# 10m02.net
KiCad netlist of a schematic drawn in EAGLE
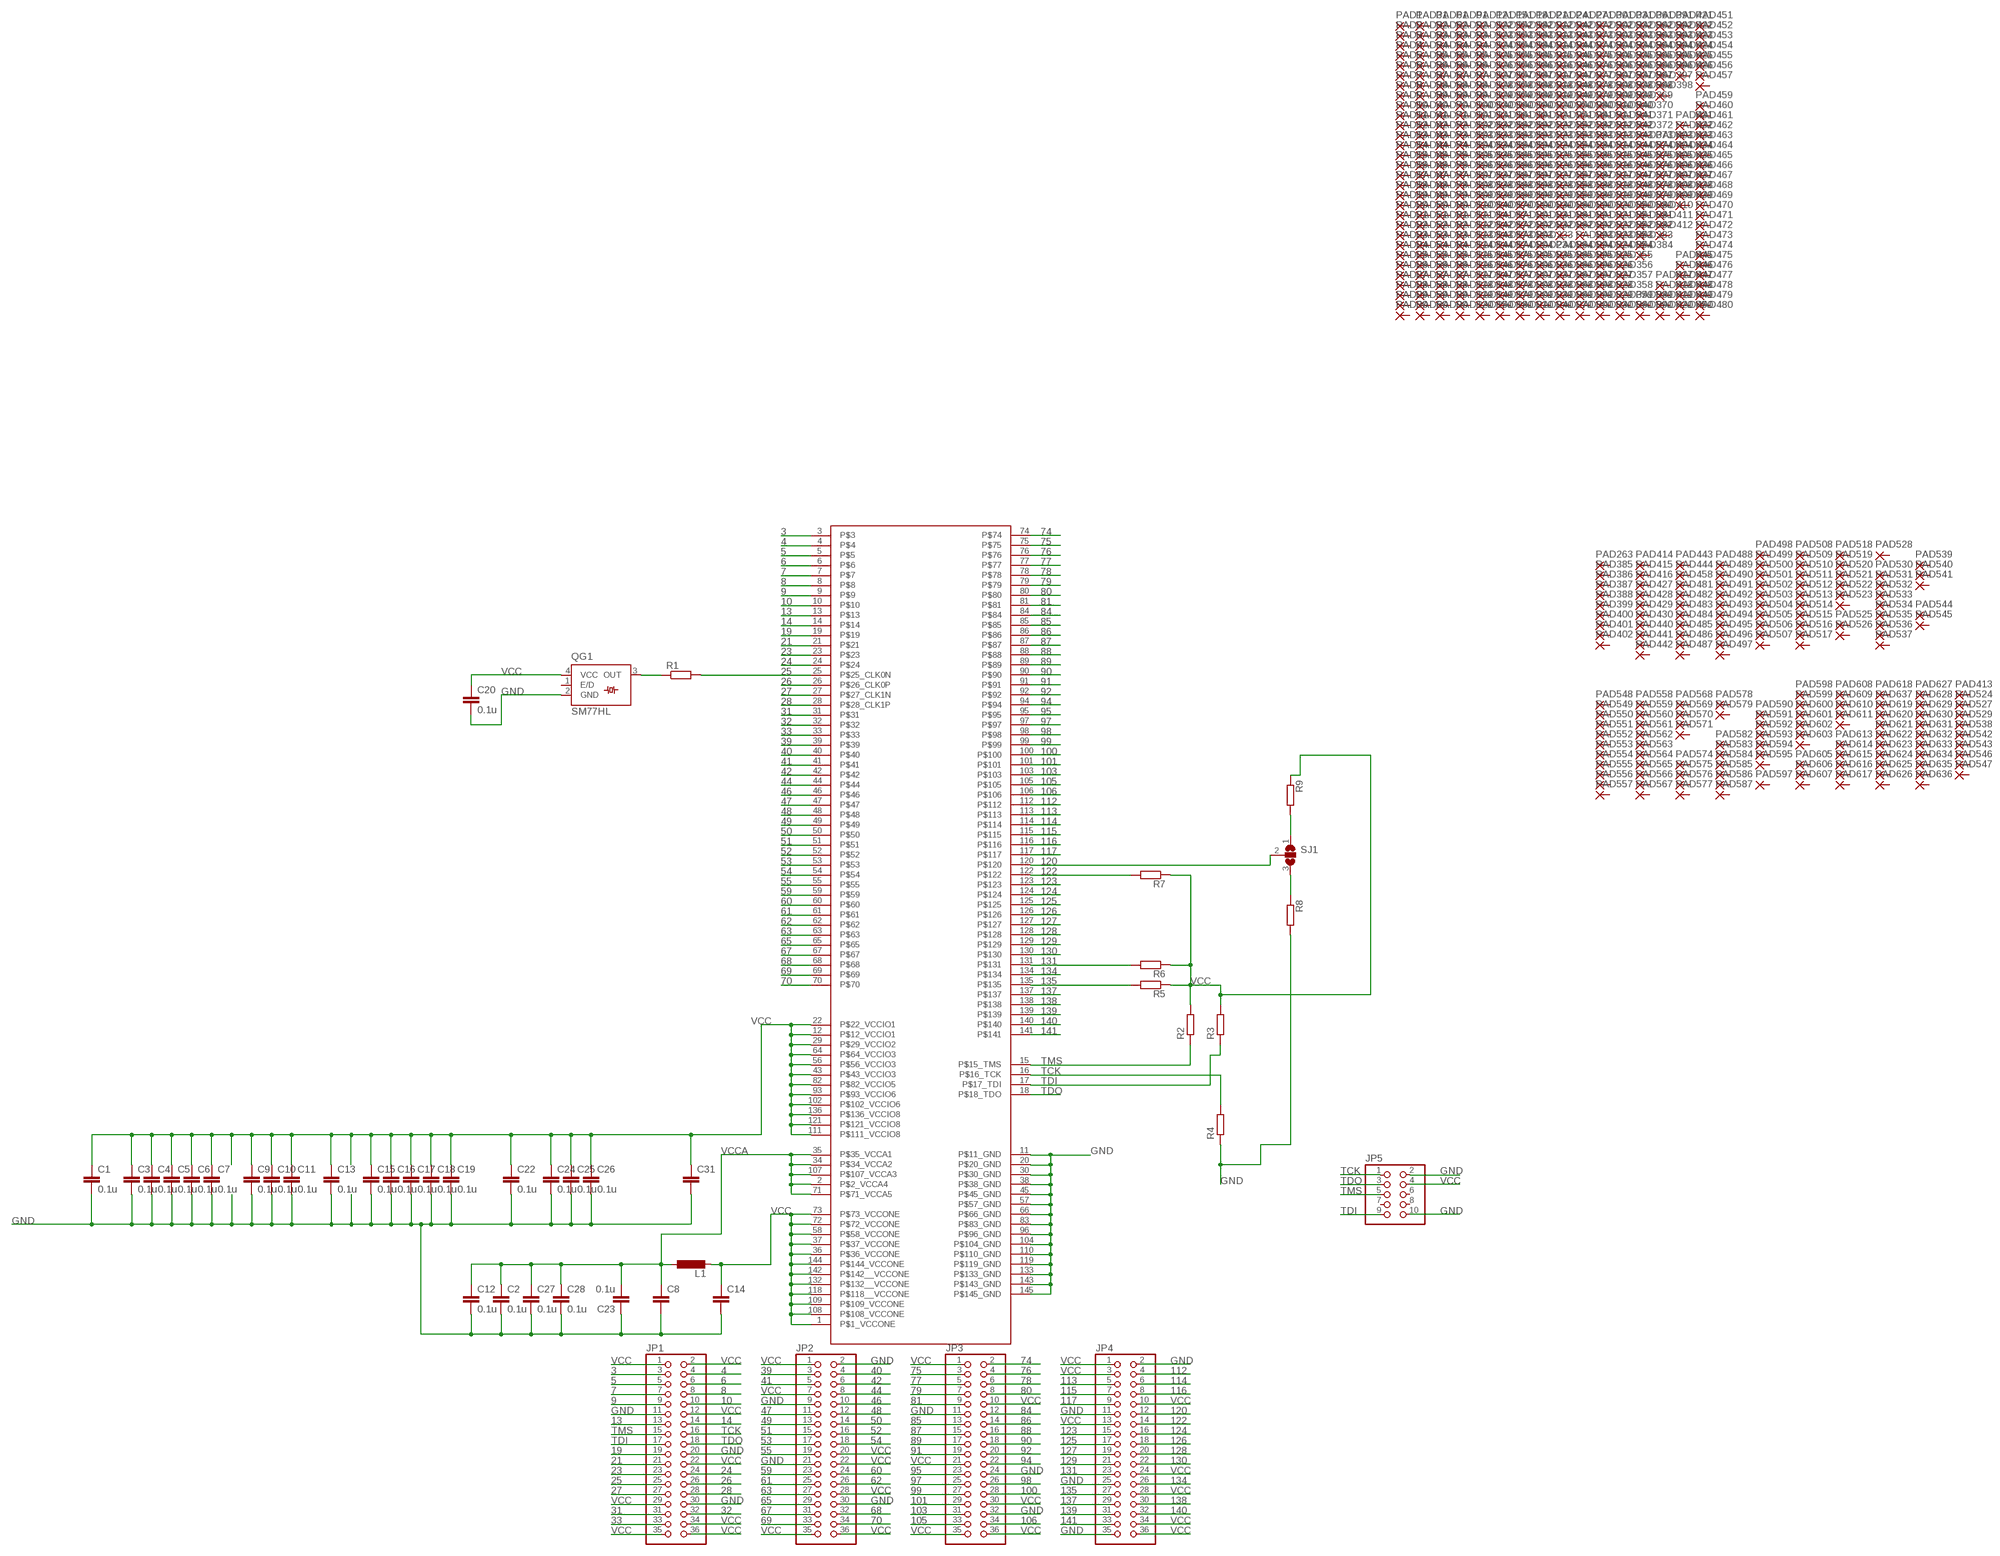
[diagram p0: schematic, sheet 1]

(export (version "E")
  (design (tool "Eeschema 10.0.6"))
  (components
    (comp (ref "C1")
      (value "0.1u")
      (footprint "eagle-import:C0603K")
      (libsource (lib "eagle-import") (part "C-EUC0603K"))
    )
    (comp (ref "C2")
      (value "0.1u")
      (footprint "eagle-import:C0603K")
      (libsource (lib "eagle-import") (part "C-EUC0603K"))
    )
    (comp (ref "C3")
      (value "0.1u")
      (footprint "eagle-import:C0603K")
      (libsource (lib "eagle-import") (part "C-EUC0603K"))
    )
    (comp (ref "C4")
      (value "0.1u")
      (footprint "eagle-import:C0603K")
      (libsource (lib "eagle-import") (part "C-EUC0603K"))
    )
    (comp (ref "C5")
      (value "0.1u")
      (footprint "eagle-import:C0603K")
      (libsource (lib "eagle-import") (part "C-EUC0603K"))
    )
    (comp (ref "C6")
      (value "0.1u")
      (footprint "eagle-import:C0603K")
      (libsource (lib "eagle-import") (part "C-EUC0603K"))
    )
    (comp (ref "C7")
      (value "0.1u")
      (footprint "eagle-import:C0603K")
      (libsource (lib "eagle-import") (part "C-EUC0603K"))
    )
    (comp (ref "C8")
      (value "C-EUC3216")
      (footprint "eagle-import:C3216")
      (libsource (lib "eagle-import") (part "C-EUC3216"))
    )
    (comp (ref "C9")
      (value "0.1u")
      (footprint "eagle-import:C0603K")
      (libsource (lib "eagle-import") (part "C-EUC0603K"))
    )
    (comp (ref "C10")
      (value "0.1u")
      (footprint "eagle-import:C0603K")
      (libsource (lib "eagle-import") (part "C-EUC0603K"))
    )
    (comp (ref "C11")
      (value "0.1u")
      (footprint "eagle-import:C0603K")
      (libsource (lib "eagle-import") (part "C-EUC0603K"))
    )
    (comp (ref "C12")
      (value "0.1u")
      (footprint "eagle-import:C0603K")
      (libsource (lib "eagle-import") (part "C-EUC0603K"))
    )
    (comp (ref "C13")
      (value "0.1u")
      (footprint "eagle-import:C0603K")
      (libsource (lib "eagle-import") (part "C-EUC0603K"))
    )
    (comp (ref "C14")
      (value "C-EUC3216")
      (footprint "eagle-import:C3216")
      (libsource (lib "eagle-import") (part "C-EUC3216"))
    )
    (comp (ref "C15")
      (value "0.1u")
      (footprint "eagle-import:C0603K")
      (libsource (lib "eagle-import") (part "C-EUC0603K"))
    )
    (comp (ref "C16")
      (value "0.1u")
      (footprint "eagle-import:C0603K")
      (libsource (lib "eagle-import") (part "C-EUC0603K"))
    )
    (comp (ref "C17")
      (value "0.1u")
      (footprint "eagle-import:C0603K")
      (libsource (lib "eagle-import") (part "C-EUC0603K"))
    )
    (comp (ref "C18")
      (value "0.1u")
      (footprint "eagle-import:C0603K")
      (libsource (lib "eagle-import") (part "C-EUC0603K"))
    )
    (comp (ref "C19")
      (value "0.1u")
      (footprint "eagle-import:C0603K")
      (libsource (lib "eagle-import") (part "C-EUC0603K"))
    )
    (comp (ref "C20")
      (value "0.1u")
      (footprint "eagle-import:C0603K")
      (libsource (lib "eagle-import") (part "C-EUC0603K"))
    )
    (comp (ref "C22")
      (value "0.1u")
      (footprint "eagle-import:C0603K")
      (libsource (lib "eagle-import") (part "C-EUC0603K"))
    )
    (comp (ref "C23")
      (value "0.1u")
      (footprint "eagle-import:C0603K")
      (libsource (lib "eagle-import") (part "C-EUC0603K"))
    )
    (comp (ref "C24")
      (value "0.1u")
      (footprint "eagle-import:C0603K")
      (libsource (lib "eagle-import") (part "C-EUC0603K"))
    )
    (comp (ref "C25")
      (value "0.1u")
      (footprint "eagle-import:C0603K")
      (libsource (lib "eagle-import") (part "C-EUC0603K"))
    )
    (comp (ref "C26")
      (value "0.1u")
      (footprint "eagle-import:C0603K")
      (libsource (lib "eagle-import") (part "C-EUC0603K"))
    )
    (comp (ref "C27")
      (value "0.1u")
      (footprint "eagle-import:C0603K")
      (libsource (lib "eagle-import") (part "C-EUC0603K"))
    )
    (comp (ref "C28")
      (value "0.1u")
      (footprint "eagle-import:C0603K")
      (libsource (lib "eagle-import") (part "C-EUC0603K"))
    )
    (comp (ref "C31")
      (value "C-EUC3225")
      (footprint "eagle-import:C3225")
      (libsource (lib "eagle-import") (part "C-EUC3225"))
    )
    (comp (ref "IC1")
      (value "10M02SC144")
      (footprint "eagle-import:TQFP144G")
      (libsource (lib "eagle-import") (part "10M02SC144"))
    )
    (comp (ref "JP1")
      (value "PINHD-2X18")
      (footprint "eagle-import:2X18")
      (libsource (lib "eagle-import") (part "PINHD-2X18"))
    )
    (comp (ref "JP2")
      (value "PINHD-2X18")
      (footprint "eagle-import:2X18")
      (libsource (lib "eagle-import") (part "PINHD-2X18"))
    )
    (comp (ref "JP3")
      (value "PINHD-2X18")
      (footprint "eagle-import:2X18")
      (libsource (lib "eagle-import") (part "PINHD-2X18"))
    )
    (comp (ref "JP4")
      (value "PINHD-2X18")
      (footprint "eagle-import:2X18")
      (libsource (lib "eagle-import") (part "PINHD-2X18"))
    )
    (comp (ref "JP5")
      (value "PINHD-2X5")
      (footprint "eagle-import:2X05")
      (libsource (lib "eagle-import") (part "PINHD-2X5"))
    )
    (comp (ref "L1")
      (value "L-EUL3216C")
      (footprint "eagle-import:L3216C")
      (libsource (lib "eagle-import") (part "L-EUL3216C"))
    )
    (comp (ref "PAD1")
      (value "1,6/0,9")
      (footprint "eagle-import:1,6_0,9")
      (libsource (lib "eagle-import") (part "1,6/0,9"))
    )
    (comp (ref "PAD2")
      (value "1,6/0,9")
      (footprint "eagle-import:1,6_0,9")
      (libsource (lib "eagle-import") (part "1,6/0,9"))
    )
    (comp (ref "PAD3")
      (value "1,6/0,9")
      (footprint "eagle-import:1,6_0,9")
      (libsource (lib "eagle-import") (part "1,6/0,9"))
    )
    (comp (ref "PAD4")
      (value "1,6/0,9")
      (footprint "eagle-import:1,6_0,9")
      (libsource (lib "eagle-import") (part "1,6/0,9"))
    )
    (comp (ref "PAD5")
      (value "1,6/0,9")
      (footprint "eagle-import:1,6_0,9")
      (libsource (lib "eagle-import") (part "1,6/0,9"))
    )
    (comp (ref "PAD6")
      (value "1,6/0,9")
      (footprint "eagle-import:1,6_0,9")
      (libsource (lib "eagle-import") (part "1,6/0,9"))
    )
    (comp (ref "PAD7")
      (value "1,6/0,9")
      (footprint "eagle-import:1,6_0,9")
      (libsource (lib "eagle-import") (part "1,6/0,9"))
    )
    (comp (ref "PAD8")
      (value "1,6/0,9")
      (footprint "eagle-import:1,6_0,9")
      (libsource (lib "eagle-import") (part "1,6/0,9"))
    )
    (comp (ref "PAD9")
      (value "1,6/0,9")
      (footprint "eagle-import:1,6_0,9")
      (libsource (lib "eagle-import") (part "1,6/0,9"))
    )
    (comp (ref "PAD10")
      (value "1,6/0,9")
      (footprint "eagle-import:1,6_0,9")
      (libsource (lib "eagle-import") (part "1,6/0,9"))
    )
    (comp (ref "PAD11")
      (value "1,6/0,9")
      (footprint "eagle-import:1,6_0,9")
      (libsource (lib "eagle-import") (part "1,6/0,9"))
    )
    (comp (ref "PAD12")
      (value "1,6/0,9")
      (footprint "eagle-import:1,6_0,9")
      (libsource (lib "eagle-import") (part "1,6/0,9"))
    )
    (comp (ref "PAD13")
      (value "1,6/0,9")
      (footprint "eagle-import:1,6_0,9")
      (libsource (lib "eagle-import") (part "1,6/0,9"))
    )
    (comp (ref "PAD14")
      (value "1,6/0,9")
      (footprint "eagle-import:1,6_0,9")
      (libsource (lib "eagle-import") (part "1,6/0,9"))
    )
    (comp (ref "PAD15")
      (value "1,6/0,9")
      (footprint "eagle-import:1,6_0,9")
      (libsource (lib "eagle-import") (part "1,6/0,9"))
    )
    (comp (ref "PAD16")
      (value "1,6/0,9")
      (footprint "eagle-import:1,6_0,9")
      (libsource (lib "eagle-import") (part "1,6/0,9"))
    )
    (comp (ref "PAD17")
      (value "1,6/0,9")
      (footprint "eagle-import:1,6_0,9")
      (libsource (lib "eagle-import") (part "1,6/0,9"))
    )
    (comp (ref "PAD18")
      (value "1,6/0,9")
      (footprint "eagle-import:1,6_0,9")
      (libsource (lib "eagle-import") (part "1,6/0,9"))
    )
    (comp (ref "PAD19")
      (value "1,6/0,9")
      (footprint "eagle-import:1,6_0,9")
      (libsource (lib "eagle-import") (part "1,6/0,9"))
    )
    (comp (ref "PAD20")
      (value "1,6/0,9")
      (footprint "eagle-import:1,6_0,9")
      (libsource (lib "eagle-import") (part "1,6/0,9"))
    )
    (comp (ref "PAD21")
      (value "1,6/0,9")
      (footprint "eagle-import:1,6_0,9")
      (libsource (lib "eagle-import") (part "1,6/0,9"))
    )
    (comp (ref "PAD22")
      (value "1,6/0,9")
      (footprint "eagle-import:1,6_0,9")
      (libsource (lib "eagle-import") (part "1,6/0,9"))
    )
    (comp (ref "PAD23")
      (value "1,6/0,9")
      (footprint "eagle-import:1,6_0,9")
      (libsource (lib "eagle-import") (part "1,6/0,9"))
    )
    (comp (ref "PAD24")
      (value "1,6/0,9")
      (footprint "eagle-import:1,6_0,9")
      (libsource (lib "eagle-import") (part "1,6/0,9"))
    )
    (comp (ref "PAD25")
      (value "1,6/0,9")
      (footprint "eagle-import:1,6_0,9")
      (libsource (lib "eagle-import") (part "1,6/0,9"))
    )
    (comp (ref "PAD26")
      (value "1,6/0,9")
      (footprint "eagle-import:1,6_0,9")
      (libsource (lib "eagle-import") (part "1,6/0,9"))
    )
    (comp (ref "PAD27")
      (value "1,6/0,9")
      (footprint "eagle-import:1,6_0,9")
      (libsource (lib "eagle-import") (part "1,6/0,9"))
    )
    (comp (ref "PAD28")
      (value "1,6/0,9")
      (footprint "eagle-import:1,6_0,9")
      (libsource (lib "eagle-import") (part "1,6/0,9"))
    )
    (comp (ref "PAD29")
      (value "1,6/0,9")
      (footprint "eagle-import:1,6_0,9")
      (libsource (lib "eagle-import") (part "1,6/0,9"))
    )
    (comp (ref "PAD30")
      (value "1,6/0,9")
      (footprint "eagle-import:1,6_0,9")
      (libsource (lib "eagle-import") (part "1,6/0,9"))
    )
    (comp (ref "PAD31")
      (value "1,6/0,9")
      (footprint "eagle-import:1,6_0,9")
      (libsource (lib "eagle-import") (part "1,6/0,9"))
    )
    (comp (ref "PAD32")
      (value "1,6/0,9")
      (footprint "eagle-import:1,6_0,9")
      (libsource (lib "eagle-import") (part "1,6/0,9"))
    )
    (comp (ref "PAD33")
      (value "1,6/0,9")
      (footprint "eagle-import:1,6_0,9")
      (libsource (lib "eagle-import") (part "1,6/0,9"))
    )
    (comp (ref "PAD34")
      (value "1,6/0,9")
      (footprint "eagle-import:1,6_0,9")
      (libsource (lib "eagle-import") (part "1,6/0,9"))
    )
    (comp (ref "PAD35")
      (value "1,6/0,9")
      (footprint "eagle-import:1,6_0,9")
      (libsource (lib "eagle-import") (part "1,6/0,9"))
    )
    (comp (ref "PAD36")
      (value "1,6/0,9")
      (footprint "eagle-import:1,6_0,9")
      (libsource (lib "eagle-import") (part "1,6/0,9"))
    )
    (comp (ref "PAD37")
      (value "1,6/0,9")
      (footprint "eagle-import:1,6_0,9")
      (libsource (lib "eagle-import") (part "1,6/0,9"))
    )
    (comp (ref "PAD38")
      (value "1,6/0,9")
      (footprint "eagle-import:1,6_0,9")
      (libsource (lib "eagle-import") (part "1,6/0,9"))
    )
    (comp (ref "PAD39")
      (value "1,6/0,9")
      (footprint "eagle-import:1,6_0,9")
      (libsource (lib "eagle-import") (part "1,6/0,9"))
    )
    (comp (ref "PAD40")
      (value "1,6/0,9")
      (footprint "eagle-import:1,6_0,9")
      (libsource (lib "eagle-import") (part "1,6/0,9"))
    )
    (comp (ref "PAD41")
      (value "1,6/0,9")
      (footprint "eagle-import:1,6_0,9")
      (libsource (lib "eagle-import") (part "1,6/0,9"))
    )
    (comp (ref "PAD42")
      (value "1,6/0,9")
      (footprint "eagle-import:1,6_0,9")
      (libsource (lib "eagle-import") (part "1,6/0,9"))
    )
    (comp (ref "PAD43")
      (value "1,6/0,9")
      (footprint "eagle-import:1,6_0,9")
      (libsource (lib "eagle-import") (part "1,6/0,9"))
    )
    (comp (ref "PAD44")
      (value "1,6/0,9")
      (footprint "eagle-import:1,6_0,9")
      (libsource (lib "eagle-import") (part "1,6/0,9"))
    )
    (comp (ref "PAD45")
      (value "1,6/0,9")
      (footprint "eagle-import:1,6_0,9")
      (libsource (lib "eagle-import") (part "1,6/0,9"))
    )
    (comp (ref "PAD46")
      (value "1,6/0,9")
      (footprint "eagle-import:1,6_0,9")
      (libsource (lib "eagle-import") (part "1,6/0,9"))
    )
    (comp (ref "PAD47")
      (value "1,6/0,9")
      (footprint "eagle-import:1,6_0,9")
      (libsource (lib "eagle-import") (part "1,6/0,9"))
    )
    (comp (ref "PAD48")
      (value "1,6/0,9")
      (footprint "eagle-import:1,6_0,9")
      (libsource (lib "eagle-import") (part "1,6/0,9"))
    )
    (comp (ref "PAD49")
      (value "1,6/0,9")
      (footprint "eagle-import:1,6_0,9")
      (libsource (lib "eagle-import") (part "1,6/0,9"))
    )
    (comp (ref "PAD50")
      (value "1,6/0,9")
      (footprint "eagle-import:1,6_0,9")
      (libsource (lib "eagle-import") (part "1,6/0,9"))
    )
    (comp (ref "PAD51")
      (value "1,6/0,9")
      (footprint "eagle-import:1,6_0,9")
      (libsource (lib "eagle-import") (part "1,6/0,9"))
    )
    (comp (ref "PAD52")
      (value "1,6/0,9")
      (footprint "eagle-import:1,6_0,9")
      (libsource (lib "eagle-import") (part "1,6/0,9"))
    )
    (comp (ref "PAD53")
      (value "1,6/0,9")
      (footprint "eagle-import:1,6_0,9")
      (libsource (lib "eagle-import") (part "1,6/0,9"))
    )
    (comp (ref "PAD54")
      (value "1,6/0,9")
      (footprint "eagle-import:1,6_0,9")
      (libsource (lib "eagle-import") (part "1,6/0,9"))
    )
    (comp (ref "PAD55")
      (value "1,6/0,9")
      (footprint "eagle-import:1,6_0,9")
      (libsource (lib "eagle-import") (part "1,6/0,9"))
    )
    (comp (ref "PAD56")
      (value "1,6/0,9")
      (footprint "eagle-import:1,6_0,9")
      (libsource (lib "eagle-import") (part "1,6/0,9"))
    )
    (comp (ref "PAD57")
      (value "1,6/0,9")
      (footprint "eagle-import:1,6_0,9")
      (libsource (lib "eagle-import") (part "1,6/0,9"))
    )
    (comp (ref "PAD58")
      (value "1,6/0,9")
      (footprint "eagle-import:1,6_0,9")
      (libsource (lib "eagle-import") (part "1,6/0,9"))
    )
    (comp (ref "PAD59")
      (value "1,6/0,9")
      (footprint "eagle-import:1,6_0,9")
      (libsource (lib "eagle-import") (part "1,6/0,9"))
    )
    (comp (ref "PAD60")
      (value "1,6/0,9")
      (footprint "eagle-import:1,6_0,9")
      (libsource (lib "eagle-import") (part "1,6/0,9"))
    )
    (comp (ref "PAD61")
      (value "1,6/0,9")
      (footprint "eagle-import:1,6_0,9")
      (libsource (lib "eagle-import") (part "1,6/0,9"))
    )
    (comp (ref "PAD62")
      (value "1,6/0,9")
      (footprint "eagle-import:1,6_0,9")
      (libsource (lib "eagle-import") (part "1,6/0,9"))
    )
    (comp (ref "PAD63")
      (value "1,6/0,9")
      (footprint "eagle-import:1,6_0,9")
      (libsource (lib "eagle-import") (part "1,6/0,9"))
    )
    (comp (ref "PAD64")
      (value "1,6/0,9")
      (footprint "eagle-import:1,6_0,9")
      (libsource (lib "eagle-import") (part "1,6/0,9"))
    )
    (comp (ref "PAD65")
      (value "1,6/0,9")
      (footprint "eagle-import:1,6_0,9")
      (libsource (lib "eagle-import") (part "1,6/0,9"))
    )
    (comp (ref "PAD66")
      (value "1,6/0,9")
      (footprint "eagle-import:1,6_0,9")
      (libsource (lib "eagle-import") (part "1,6/0,9"))
    )
    (comp (ref "PAD67")
      (value "1,6/0,9")
      (footprint "eagle-import:1,6_0,9")
      (libsource (lib "eagle-import") (part "1,6/0,9"))
    )
    (comp (ref "PAD68")
      (value "1,6/0,9")
      (footprint "eagle-import:1,6_0,9")
      (libsource (lib "eagle-import") (part "1,6/0,9"))
    )
    (comp (ref "PAD69")
      (value "1,6/0,9")
      (footprint "eagle-import:1,6_0,9")
      (libsource (lib "eagle-import") (part "1,6/0,9"))
    )
    (comp (ref "PAD70")
      (value "1,6/0,9")
      (footprint "eagle-import:1,6_0,9")
      (libsource (lib "eagle-import") (part "1,6/0,9"))
    )
    (comp (ref "PAD71")
      (value "1,6/0,9")
      (footprint "eagle-import:1,6_0,9")
      (libsource (lib "eagle-import") (part "1,6/0,9"))
    )
    (comp (ref "PAD72")
      (value "1,6/0,9")
      (footprint "eagle-import:1,6_0,9")
      (libsource (lib "eagle-import") (part "1,6/0,9"))
    )
    (comp (ref "PAD73")
      (value "1,6/0,9")
      (footprint "eagle-import:1,6_0,9")
      (libsource (lib "eagle-import") (part "1,6/0,9"))
    )
    (comp (ref "PAD74")
      (value "1,6/0,9")
      (footprint "eagle-import:1,6_0,9")
      (libsource (lib "eagle-import") (part "1,6/0,9"))
    )
    (comp (ref "PAD75")
      (value "1,6/0,9")
      (footprint "eagle-import:1,6_0,9")
      (libsource (lib "eagle-import") (part "1,6/0,9"))
    )
    (comp (ref "PAD76")
      (value "1,6/0,9")
      (footprint "eagle-import:1,6_0,9")
      (libsource (lib "eagle-import") (part "1,6/0,9"))
    )
    (comp (ref "PAD77")
      (value "1,6/0,9")
      (footprint "eagle-import:1,6_0,9")
      (libsource (lib "eagle-import") (part "1,6/0,9"))
    )
    (comp (ref "PAD78")
      (value "1,6/0,9")
      (footprint "eagle-import:1,6_0,9")
      (libsource (lib "eagle-import") (part "1,6/0,9"))
    )
    (comp (ref "PAD79")
      (value "1,6/0,9")
      (footprint "eagle-import:1,6_0,9")
      (libsource (lib "eagle-import") (part "1,6/0,9"))
    )
    (comp (ref "PAD80")
      (value "1,6/0,9")
      (footprint "eagle-import:1,6_0,9")
      (libsource (lib "eagle-import") (part "1,6/0,9"))
    )
    (comp (ref "PAD81")
      (value "1,6/0,9")
      (footprint "eagle-import:1,6_0,9")
      (libsource (lib "eagle-import") (part "1,6/0,9"))
    )
    (comp (ref "PAD82")
      (value "1,6/0,9")
      (footprint "eagle-import:1,6_0,9")
      (libsource (lib "eagle-import") (part "1,6/0,9"))
    )
    (comp (ref "PAD83")
      (value "1,6/0,9")
      (footprint "eagle-import:1,6_0,9")
      (libsource (lib "eagle-import") (part "1,6/0,9"))
    )
    (comp (ref "PAD84")
      (value "1,6/0,9")
      (footprint "eagle-import:1,6_0,9")
      (libsource (lib "eagle-import") (part "1,6/0,9"))
    )
    (comp (ref "PAD85")
      (value "1,6/0,9")
      (footprint "eagle-import:1,6_0,9")
      (libsource (lib "eagle-import") (part "1,6/0,9"))
    )
    (comp (ref "PAD86")
      (value "1,6/0,9")
      (footprint "eagle-import:1,6_0,9")
      (libsource (lib "eagle-import") (part "1,6/0,9"))
    )
    (comp (ref "PAD87")
      (value "1,6/0,9")
      (footprint "eagle-import:1,6_0,9")
      (libsource (lib "eagle-import") (part "1,6/0,9"))
    )
    (comp (ref "PAD88")
      (value "1,6/0,9")
      (footprint "eagle-import:1,6_0,9")
      (libsource (lib "eagle-import") (part "1,6/0,9"))
    )
    (comp (ref "PAD89")
      (value "1,6/0,9")
      (footprint "eagle-import:1,6_0,9")
      (libsource (lib "eagle-import") (part "1,6/0,9"))
    )
    (comp (ref "PAD90")
      (value "1,6/0,9")
      (footprint "eagle-import:1,6_0,9")
      (libsource (lib "eagle-import") (part "1,6/0,9"))
    )
    (comp (ref "PAD91")
      (value "1,6/0,9")
      (footprint "eagle-import:1,6_0,9")
      (libsource (lib "eagle-import") (part "1,6/0,9"))
    )
    (comp (ref "PAD92")
      (value "1,6/0,9")
      (footprint "eagle-import:1,6_0,9")
      (libsource (lib "eagle-import") (part "1,6/0,9"))
    )
    (comp (ref "PAD93")
      (value "1,6/0,9")
      (footprint "eagle-import:1,6_0,9")
      (libsource (lib "eagle-import") (part "1,6/0,9"))
    )
    (comp (ref "PAD94")
      (value "1,6/0,9")
      (footprint "eagle-import:1,6_0,9")
      (libsource (lib "eagle-import") (part "1,6/0,9"))
    )
    (comp (ref "PAD95")
      (value "1,6/0,9")
      (footprint "eagle-import:1,6_0,9")
      (libsource (lib "eagle-import") (part "1,6/0,9"))
    )
    (comp (ref "PAD96")
      (value "1,6/0,9")
      (footprint "eagle-import:1,6_0,9")
      (libsource (lib "eagle-import") (part "1,6/0,9"))
    )
    (comp (ref "PAD97")
      (value "1,6/0,9")
      (footprint "eagle-import:1,6_0,9")
      (libsource (lib "eagle-import") (part "1,6/0,9"))
    )
    (comp (ref "PAD98")
      (value "1,6/0,9")
      (footprint "eagle-import:1,6_0,9")
      (libsource (lib "eagle-import") (part "1,6/0,9"))
    )
    (comp (ref "PAD99")
      (value "1,6/0,9")
      (footprint "eagle-import:1,6_0,9")
      (libsource (lib "eagle-import") (part "1,6/0,9"))
    )
    (comp (ref "PAD100")
      (value "1,6/0,9")
      (footprint "eagle-import:1,6_0,9")
      (libsource (lib "eagle-import") (part "1,6/0,9"))
    )
    (comp (ref "PAD101")
      (value "1,6/0,9")
      (footprint "eagle-import:1,6_0,9")
      (libsource (lib "eagle-import") (part "1,6/0,9"))
    )
    (comp (ref "PAD102")
      (value "1,6/0,9")
      (footprint "eagle-import:1,6_0,9")
      (libsource (lib "eagle-import") (part "1,6/0,9"))
    )
    (comp (ref "PAD103")
      (value "1,6/0,9")
      (footprint "eagle-import:1,6_0,9")
      (libsource (lib "eagle-import") (part "1,6/0,9"))
    )
    (comp (ref "PAD104")
      (value "1,6/0,9")
      (footprint "eagle-import:1,6_0,9")
      (libsource (lib "eagle-import") (part "1,6/0,9"))
    )
    (comp (ref "PAD105")
      (value "1,6/0,9")
      (footprint "eagle-import:1,6_0,9")
      (libsource (lib "eagle-import") (part "1,6/0,9"))
    )
    (comp (ref "PAD106")
      (value "1,6/0,9")
      (footprint "eagle-import:1,6_0,9")
      (libsource (lib "eagle-import") (part "1,6/0,9"))
    )
    (comp (ref "PAD107")
      (value "1,6/0,9")
      (footprint "eagle-import:1,6_0,9")
      (libsource (lib "eagle-import") (part "1,6/0,9"))
    )
    (comp (ref "PAD108")
      (value "1,6/0,9")
      (footprint "eagle-import:1,6_0,9")
      (libsource (lib "eagle-import") (part "1,6/0,9"))
    )
    (comp (ref "PAD109")
      (value "1,6/0,9")
      (footprint "eagle-import:1,6_0,9")
      (libsource (lib "eagle-import") (part "1,6/0,9"))
    )
    (comp (ref "PAD110")
      (value "1,6/0,9")
      (footprint "eagle-import:1,6_0,9")
      (libsource (lib "eagle-import") (part "1,6/0,9"))
    )
    (comp (ref "PAD111")
      (value "1,6/0,9")
      (footprint "eagle-import:1,6_0,9")
      (libsource (lib "eagle-import") (part "1,6/0,9"))
    )
    (comp (ref "PAD112")
      (value "1,6/0,9")
      (footprint "eagle-import:1,6_0,9")
      (libsource (lib "eagle-import") (part "1,6/0,9"))
    )
    (comp (ref "PAD113")
      (value "1,6/0,9")
      (footprint "eagle-import:1,6_0,9")
      (libsource (lib "eagle-import") (part "1,6/0,9"))
    )
    (comp (ref "PAD114")
      (value "1,6/0,9")
      (footprint "eagle-import:1,6_0,9")
      (libsource (lib "eagle-import") (part "1,6/0,9"))
    )
    (comp (ref "PAD115")
      (value "1,6/0,9")
      (footprint "eagle-import:1,6_0,9")
      (libsource (lib "eagle-import") (part "1,6/0,9"))
    )
    (comp (ref "PAD116")
      (value "1,6/0,9")
      (footprint "eagle-import:1,6_0,9")
      (libsource (lib "eagle-import") (part "1,6/0,9"))
    )
    (comp (ref "PAD117")
      (value "1,6/0,9")
      (footprint "eagle-import:1,6_0,9")
      (libsource (lib "eagle-import") (part "1,6/0,9"))
    )
    (comp (ref "PAD118")
      (value "1,6/0,9")
      (footprint "eagle-import:1,6_0,9")
      (libsource (lib "eagle-import") (part "1,6/0,9"))
    )
    (comp (ref "PAD119")
      (value "1,6/0,9")
      (footprint "eagle-import:1,6_0,9")
      (libsource (lib "eagle-import") (part "1,6/0,9"))
    )
    (comp (ref "PAD120")
      (value "1,6/0,9")
      (footprint "eagle-import:1,6_0,9")
      (libsource (lib "eagle-import") (part "1,6/0,9"))
    )
    (comp (ref "PAD121")
      (value "1,6/0,9")
      (footprint "eagle-import:1,6_0,9")
      (libsource (lib "eagle-import") (part "1,6/0,9"))
    )
    (comp (ref "PAD122")
      (value "1,6/0,9")
      (footprint "eagle-import:1,6_0,9")
      (libsource (lib "eagle-import") (part "1,6/0,9"))
    )
    (comp (ref "PAD123")
      (value "1,6/0,9")
      (footprint "eagle-import:1,6_0,9")
      (libsource (lib "eagle-import") (part "1,6/0,9"))
    )
    (comp (ref "PAD124")
      (value "1,6/0,9")
      (footprint "eagle-import:1,6_0,9")
      (libsource (lib "eagle-import") (part "1,6/0,9"))
    )
    (comp (ref "PAD125")
      (value "1,6/0,9")
      (footprint "eagle-import:1,6_0,9")
      (libsource (lib "eagle-import") (part "1,6/0,9"))
    )
    (comp (ref "PAD126")
      (value "1,6/0,9")
      (footprint "eagle-import:1,6_0,9")
      (libsource (lib "eagle-import") (part "1,6/0,9"))
    )
    (comp (ref "PAD127")
      (value "1,6/0,9")
      (footprint "eagle-import:1,6_0,9")
      (libsource (lib "eagle-import") (part "1,6/0,9"))
    )
    (comp (ref "PAD128")
      (value "1,6/0,9")
      (footprint "eagle-import:1,6_0,9")
      (libsource (lib "eagle-import") (part "1,6/0,9"))
    )
    (comp (ref "PAD129")
      (value "1,6/0,9")
      (footprint "eagle-import:1,6_0,9")
      (libsource (lib "eagle-import") (part "1,6/0,9"))
    )
    (comp (ref "PAD130")
      (value "1,6/0,9")
      (footprint "eagle-import:1,6_0,9")
      (libsource (lib "eagle-import") (part "1,6/0,9"))
    )
    (comp (ref "PAD131")
      (value "1,6/0,9")
      (footprint "eagle-import:1,6_0,9")
      (libsource (lib "eagle-import") (part "1,6/0,9"))
    )
    (comp (ref "PAD132")
      (value "1,6/0,9")
      (footprint "eagle-import:1,6_0,9")
      (libsource (lib "eagle-import") (part "1,6/0,9"))
    )
    (comp (ref "PAD133")
      (value "1,6/0,9")
      (footprint "eagle-import:1,6_0,9")
      (libsource (lib "eagle-import") (part "1,6/0,9"))
    )
    (comp (ref "PAD134")
      (value "1,6/0,9")
      (footprint "eagle-import:1,6_0,9")
      (libsource (lib "eagle-import") (part "1,6/0,9"))
    )
    (comp (ref "PAD135")
      (value "1,6/0,9")
      (footprint "eagle-import:1,6_0,9")
      (libsource (lib "eagle-import") (part "1,6/0,9"))
    )
    (comp (ref "PAD136")
      (value "1,6/0,9")
      (footprint "eagle-import:1,6_0,9")
      (libsource (lib "eagle-import") (part "1,6/0,9"))
    )
    (comp (ref "PAD137")
      (value "1,6/0,9")
      (footprint "eagle-import:1,6_0,9")
      (libsource (lib "eagle-import") (part "1,6/0,9"))
    )
    (comp (ref "PAD138")
      (value "1,6/0,9")
      (footprint "eagle-import:1,6_0,9")
      (libsource (lib "eagle-import") (part "1,6/0,9"))
    )
    (comp (ref "PAD139")
      (value "1,6/0,9")
      (footprint "eagle-import:1,6_0,9")
      (libsource (lib "eagle-import") (part "1,6/0,9"))
    )
    (comp (ref "PAD140")
      (value "1,6/0,9")
      (footprint "eagle-import:1,6_0,9")
      (libsource (lib "eagle-import") (part "1,6/0,9"))
    )
    (comp (ref "PAD141")
      (value "1,6/0,9")
      (footprint "eagle-import:1,6_0,9")
      (libsource (lib "eagle-import") (part "1,6/0,9"))
    )
    (comp (ref "PAD142")
      (value "1,6/0,9")
      (footprint "eagle-import:1,6_0,9")
      (libsource (lib "eagle-import") (part "1,6/0,9"))
    )
    (comp (ref "PAD143")
      (value "1,6/0,9")
      (footprint "eagle-import:1,6_0,9")
      (libsource (lib "eagle-import") (part "1,6/0,9"))
    )
    (comp (ref "PAD144")
      (value "1,6/0,9")
      (footprint "eagle-import:1,6_0,9")
      (libsource (lib "eagle-import") (part "1,6/0,9"))
    )
    (comp (ref "PAD145")
      (value "1,6/0,9")
      (footprint "eagle-import:1,6_0,9")
      (libsource (lib "eagle-import") (part "1,6/0,9"))
    )
    (comp (ref "PAD146")
      (value "1,6/0,9")
      (footprint "eagle-import:1,6_0,9")
      (libsource (lib "eagle-import") (part "1,6/0,9"))
    )
    (comp (ref "PAD147")
      (value "1,6/0,9")
      (footprint "eagle-import:1,6_0,9")
      (libsource (lib "eagle-import") (part "1,6/0,9"))
    )
    (comp (ref "PAD148")
      (value "1,6/0,9")
      (footprint "eagle-import:1,6_0,9")
      (libsource (lib "eagle-import") (part "1,6/0,9"))
    )
    (comp (ref "PAD149")
      (value "1,6/0,9")
      (footprint "eagle-import:1,6_0,9")
      (libsource (lib "eagle-import") (part "1,6/0,9"))
    )
    (comp (ref "PAD150")
      (value "1,6/0,9")
      (footprint "eagle-import:1,6_0,9")
      (libsource (lib "eagle-import") (part "1,6/0,9"))
    )
    (comp (ref "PAD151")
      (value "1,6/0,9")
      (footprint "eagle-import:1,6_0,9")
      (libsource (lib "eagle-import") (part "1,6/0,9"))
    )
    (comp (ref "PAD152")
      (value "1,6/0,9")
      (footprint "eagle-import:1,6_0,9")
      (libsource (lib "eagle-import") (part "1,6/0,9"))
    )
    (comp (ref "PAD153")
      (value "1,6/0,9")
      (footprint "eagle-import:1,6_0,9")
      (libsource (lib "eagle-import") (part "1,6/0,9"))
    )
    (comp (ref "PAD154")
      (value "1,6/0,9")
      (footprint "eagle-import:1,6_0,9")
      (libsource (lib "eagle-import") (part "1,6/0,9"))
    )
    (comp (ref "PAD155")
      (value "1,6/0,9")
      (footprint "eagle-import:1,6_0,9")
      (libsource (lib "eagle-import") (part "1,6/0,9"))
    )
    (comp (ref "PAD156")
      (value "1,6/0,9")
      (footprint "eagle-import:1,6_0,9")
      (libsource (lib "eagle-import") (part "1,6/0,9"))
    )
    (comp (ref "PAD157")
      (value "1,6/0,9")
      (footprint "eagle-import:1,6_0,9")
      (libsource (lib "eagle-import") (part "1,6/0,9"))
    )
    (comp (ref "PAD158")
      (value "1,6/0,9")
      (footprint "eagle-import:1,6_0,9")
      (libsource (lib "eagle-import") (part "1,6/0,9"))
    )
    (comp (ref "PAD159")
      (value "1,6/0,9")
      (footprint "eagle-import:1,6_0,9")
      (libsource (lib "eagle-import") (part "1,6/0,9"))
    )
    (comp (ref "PAD160")
      (value "1,6/0,9")
      (footprint "eagle-import:1,6_0,9")
      (libsource (lib "eagle-import") (part "1,6/0,9"))
    )
    (comp (ref "PAD161")
      (value "1,6/0,9")
      (footprint "eagle-import:1,6_0,9")
      (libsource (lib "eagle-import") (part "1,6/0,9"))
    )
    (comp (ref "PAD162")
      (value "1,6/0,9")
      (footprint "eagle-import:1,6_0,9")
      (libsource (lib "eagle-import") (part "1,6/0,9"))
    )
    (comp (ref "PAD163")
      (value "1,6/0,9")
      (footprint "eagle-import:1,6_0,9")
      (libsource (lib "eagle-import") (part "1,6/0,9"))
    )
    (comp (ref "PAD164")
      (value "1,6/0,9")
      (footprint "eagle-import:1,6_0,9")
      (libsource (lib "eagle-import") (part "1,6/0,9"))
    )
    (comp (ref "PAD165")
      (value "1,6/0,9")
      (footprint "eagle-import:1,6_0,9")
      (libsource (lib "eagle-import") (part "1,6/0,9"))
    )
    (comp (ref "PAD166")
      (value "1,6/0,9")
      (footprint "eagle-import:1,6_0,9")
      (libsource (lib "eagle-import") (part "1,6/0,9"))
    )
    (comp (ref "PAD167")
      (value "1,6/0,9")
      (footprint "eagle-import:1,6_0,9")
      (libsource (lib "eagle-import") (part "1,6/0,9"))
    )
    (comp (ref "PAD168")
      (value "1,6/0,9")
      (footprint "eagle-import:1,6_0,9")
      (libsource (lib "eagle-import") (part "1,6/0,9"))
    )
    (comp (ref "PAD169")
      (value "1,6/0,9")
      (footprint "eagle-import:1,6_0,9")
      (libsource (lib "eagle-import") (part "1,6/0,9"))
    )
    (comp (ref "PAD170")
      (value "1,6/0,9")
      (footprint "eagle-import:1,6_0,9")
      (libsource (lib "eagle-import") (part "1,6/0,9"))
    )
    (comp (ref "PAD171")
      (value "1,6/0,9")
      (footprint "eagle-import:1,6_0,9")
      (libsource (lib "eagle-import") (part "1,6/0,9"))
    )
    (comp (ref "PAD172")
      (value "1,6/0,9")
      (footprint "eagle-import:1,6_0,9")
      (libsource (lib "eagle-import") (part "1,6/0,9"))
    )
    (comp (ref "PAD173")
      (value "1,6/0,9")
      (footprint "eagle-import:1,6_0,9")
      (libsource (lib "eagle-import") (part "1,6/0,9"))
    )
    (comp (ref "PAD174")
      (value "1,6/0,9")
      (footprint "eagle-import:1,6_0,9")
      (libsource (lib "eagle-import") (part "1,6/0,9"))
    )
    (comp (ref "PAD175")
      (value "1,6/0,9")
      (footprint "eagle-import:1,6_0,9")
      (libsource (lib "eagle-import") (part "1,6/0,9"))
    )
    (comp (ref "PAD176")
      (value "1,6/0,9")
      (footprint "eagle-import:1,6_0,9")
      (libsource (lib "eagle-import") (part "1,6/0,9"))
    )
    (comp (ref "PAD177")
      (value "1,6/0,9")
      (footprint "eagle-import:1,6_0,9")
      (libsource (lib "eagle-import") (part "1,6/0,9"))
    )
    (comp (ref "PAD178")
      (value "1,6/0,9")
      (footprint "eagle-import:1,6_0,9")
      (libsource (lib "eagle-import") (part "1,6/0,9"))
    )
    (comp (ref "PAD179")
      (value "1,6/0,9")
      (footprint "eagle-import:1,6_0,9")
      (libsource (lib "eagle-import") (part "1,6/0,9"))
    )
    (comp (ref "PAD180")
      (value "1,6/0,9")
      (footprint "eagle-import:1,6_0,9")
      (libsource (lib "eagle-import") (part "1,6/0,9"))
    )
    (comp (ref "PAD181")
      (value "1,6/0,9")
      (footprint "eagle-import:1,6_0,9")
      (libsource (lib "eagle-import") (part "1,6/0,9"))
    )
    (comp (ref "PAD182")
      (value "1,6/0,9")
      (footprint "eagle-import:1,6_0,9")
      (libsource (lib "eagle-import") (part "1,6/0,9"))
    )
    (comp (ref "PAD183")
      (value "1,6/0,9")
      (footprint "eagle-import:1,6_0,9")
      (libsource (lib "eagle-import") (part "1,6/0,9"))
    )
    (comp (ref "PAD184")
      (value "1,6/0,9")
      (footprint "eagle-import:1,6_0,9")
      (libsource (lib "eagle-import") (part "1,6/0,9"))
    )
    (comp (ref "PAD185")
      (value "1,6/0,9")
      (footprint "eagle-import:1,6_0,9")
      (libsource (lib "eagle-import") (part "1,6/0,9"))
    )
    (comp (ref "PAD186")
      (value "1,6/0,9")
      (footprint "eagle-import:1,6_0,9")
      (libsource (lib "eagle-import") (part "1,6/0,9"))
    )
    (comp (ref "PAD187")
      (value "1,6/0,9")
      (footprint "eagle-import:1,6_0,9")
      (libsource (lib "eagle-import") (part "1,6/0,9"))
    )
    (comp (ref "PAD188")
      (value "1,6/0,9")
      (footprint "eagle-import:1,6_0,9")
      (libsource (lib "eagle-import") (part "1,6/0,9"))
    )
    (comp (ref "PAD189")
      (value "1,6/0,9")
      (footprint "eagle-import:1,6_0,9")
      (libsource (lib "eagle-import") (part "1,6/0,9"))
    )
    (comp (ref "PAD190")
      (value "1,6/0,9")
      (footprint "eagle-import:1,6_0,9")
      (libsource (lib "eagle-import") (part "1,6/0,9"))
    )
    (comp (ref "PAD191")
      (value "1,6/0,9")
      (footprint "eagle-import:1,6_0,9")
      (libsource (lib "eagle-import") (part "1,6/0,9"))
    )
    (comp (ref "PAD192")
      (value "1,6/0,9")
      (footprint "eagle-import:1,6_0,9")
      (libsource (lib "eagle-import") (part "1,6/0,9"))
    )
    (comp (ref "PAD193")
      (value "1,6/0,9")
      (footprint "eagle-import:1,6_0,9")
      (libsource (lib "eagle-import") (part "1,6/0,9"))
    )
    (comp (ref "PAD194")
      (value "1,6/0,9")
      (footprint "eagle-import:1,6_0,9")
      (libsource (lib "eagle-import") (part "1,6/0,9"))
    )
    (comp (ref "PAD195")
      (value "1,6/0,9")
      (footprint "eagle-import:1,6_0,9")
      (libsource (lib "eagle-import") (part "1,6/0,9"))
    )
    (comp (ref "PAD196")
      (value "1,6/0,9")
      (footprint "eagle-import:1,6_0,9")
      (libsource (lib "eagle-import") (part "1,6/0,9"))
    )
    (comp (ref "PAD197")
      (value "1,6/0,9")
      (footprint "eagle-import:1,6_0,9")
      (libsource (lib "eagle-import") (part "1,6/0,9"))
    )
    (comp (ref "PAD198")
      (value "1,6/0,9")
      (footprint "eagle-import:1,6_0,9")
      (libsource (lib "eagle-import") (part "1,6/0,9"))
    )
    (comp (ref "PAD199")
      (value "1,6/0,9")
      (footprint "eagle-import:1,6_0,9")
      (libsource (lib "eagle-import") (part "1,6/0,9"))
    )
    (comp (ref "PAD200")
      (value "1,6/0,9")
      (footprint "eagle-import:1,6_0,9")
      (libsource (lib "eagle-import") (part "1,6/0,9"))
    )
    (comp (ref "PAD201")
      (value "1,6/0,9")
      (footprint "eagle-import:1,6_0,9")
      (libsource (lib "eagle-import") (part "1,6/0,9"))
    )
    (comp (ref "PAD202")
      (value "1,6/0,9")
      (footprint "eagle-import:1,6_0,9")
      (libsource (lib "eagle-import") (part "1,6/0,9"))
    )
    (comp (ref "PAD203")
      (value "1,6/0,9")
      (footprint "eagle-import:1,6_0,9")
      (libsource (lib "eagle-import") (part "1,6/0,9"))
    )
    (comp (ref "PAD204")
      (value "1,6/0,9")
      (footprint "eagle-import:1,6_0,9")
      (libsource (lib "eagle-import") (part "1,6/0,9"))
    )
    (comp (ref "PAD205")
      (value "1,6/0,9")
      (footprint "eagle-import:1,6_0,9")
      (libsource (lib "eagle-import") (part "1,6/0,9"))
    )
    (comp (ref "PAD206")
      (value "1,6/0,9")
      (footprint "eagle-import:1,6_0,9")
      (libsource (lib "eagle-import") (part "1,6/0,9"))
    )
    (comp (ref "PAD207")
      (value "1,6/0,9")
      (footprint "eagle-import:1,6_0,9")
      (libsource (lib "eagle-import") (part "1,6/0,9"))
    )
    (comp (ref "PAD208")
      (value "1,6/0,9")
      (footprint "eagle-import:1,6_0,9")
      (libsource (lib "eagle-import") (part "1,6/0,9"))
    )
    (comp (ref "PAD209")
      (value "1,6/0,9")
      (footprint "eagle-import:1,6_0,9")
      (libsource (lib "eagle-import") (part "1,6/0,9"))
    )
    (comp (ref "PAD210")
      (value "1,6/0,9")
      (footprint "eagle-import:1,6_0,9")
      (libsource (lib "eagle-import") (part "1,6/0,9"))
    )
    (comp (ref "PAD211")
      (value "1,6/0,9")
      (footprint "eagle-import:1,6_0,9")
      (libsource (lib "eagle-import") (part "1,6/0,9"))
    )
    (comp (ref "PAD212")
      (value "1,6/0,9")
      (footprint "eagle-import:1,6_0,9")
      (libsource (lib "eagle-import") (part "1,6/0,9"))
    )
    (comp (ref "PAD213")
      (value "1,6/0,9")
      (footprint "eagle-import:1,6_0,9")
      (libsource (lib "eagle-import") (part "1,6/0,9"))
    )
    (comp (ref "PAD214")
      (value "1,6/0,9")
      (footprint "eagle-import:1,6_0,9")
      (libsource (lib "eagle-import") (part "1,6/0,9"))
    )
    (comp (ref "PAD215")
      (value "1,6/0,9")
      (footprint "eagle-import:1,6_0,9")
      (libsource (lib "eagle-import") (part "1,6/0,9"))
    )
    (comp (ref "PAD216")
      (value "1,6/0,9")
      (footprint "eagle-import:1,6_0,9")
      (libsource (lib "eagle-import") (part "1,6/0,9"))
    )
    (comp (ref "PAD217")
      (value "1,6/0,9")
      (footprint "eagle-import:1,6_0,9")
      (libsource (lib "eagle-import") (part "1,6/0,9"))
    )
    (comp (ref "PAD218")
      (value "1,6/0,9")
      (footprint "eagle-import:1,6_0,9")
      (libsource (lib "eagle-import") (part "1,6/0,9"))
    )
    (comp (ref "PAD219")
      (value "1,6/0,9")
      (footprint "eagle-import:1,6_0,9")
      (libsource (lib "eagle-import") (part "1,6/0,9"))
    )
    (comp (ref "PAD220")
      (value "1,6/0,9")
      (footprint "eagle-import:1,6_0,9")
      (libsource (lib "eagle-import") (part "1,6/0,9"))
    )
    (comp (ref "PAD221")
      (value "1,6/0,9")
      (footprint "eagle-import:1,6_0,9")
      (libsource (lib "eagle-import") (part "1,6/0,9"))
    )
    (comp (ref "PAD222")
      (value "1,6/0,9")
      (footprint "eagle-import:1,6_0,9")
      (libsource (lib "eagle-import") (part "1,6/0,9"))
    )
    (comp (ref "PAD223")
      (value "1,6/0,9")
      (footprint "eagle-import:1,6_0,9")
      (libsource (lib "eagle-import") (part "1,6/0,9"))
    )
    (comp (ref "PAD224")
      (value "1,6/0,9")
      (footprint "eagle-import:1,6_0,9")
      (libsource (lib "eagle-import") (part "1,6/0,9"))
    )
    (comp (ref "PAD225")
      (value "1,6/0,9")
      (footprint "eagle-import:1,6_0,9")
      (libsource (lib "eagle-import") (part "1,6/0,9"))
    )
    (comp (ref "PAD226")
      (value "1,6/0,9")
      (footprint "eagle-import:1,6_0,9")
      (libsource (lib "eagle-import") (part "1,6/0,9"))
    )
    (comp (ref "PAD227")
      (value "1,6/0,9")
      (footprint "eagle-import:1,6_0,9")
      (libsource (lib "eagle-import") (part "1,6/0,9"))
    )
    (comp (ref "PAD228")
      (value "1,6/0,9")
      (footprint "eagle-import:1,6_0,9")
      (libsource (lib "eagle-import") (part "1,6/0,9"))
    )
    (comp (ref "PAD229")
      (value "1,6/0,9")
      (footprint "eagle-import:1,6_0,9")
      (libsource (lib "eagle-import") (part "1,6/0,9"))
    )
    (comp (ref "PAD230")
      (value "1,6/0,9")
      (footprint "eagle-import:1,6_0,9")
      (libsource (lib "eagle-import") (part "1,6/0,9"))
    )
    (comp (ref "PAD231")
      (value "1,6/0,9")
      (footprint "eagle-import:1,6_0,9")
      (libsource (lib "eagle-import") (part "1,6/0,9"))
    )
    (comp (ref "PAD232")
      (value "1,6/0,9")
      (footprint "eagle-import:1,6_0,9")
      (libsource (lib "eagle-import") (part "1,6/0,9"))
    )
    (comp (ref "PAD233")
      (value "1,6/0,9")
      (footprint "eagle-import:1,6_0,9")
      (libsource (lib "eagle-import") (part "1,6/0,9"))
    )
    (comp (ref "PAD234")
      (value "1,6/0,9")
      (footprint "eagle-import:1,6_0,9")
      (libsource (lib "eagle-import") (part "1,6/0,9"))
    )
    (comp (ref "PAD235")
      (value "1,6/0,9")
      (footprint "eagle-import:1,6_0,9")
      (libsource (lib "eagle-import") (part "1,6/0,9"))
    )
    (comp (ref "PAD236")
      (value "1,6/0,9")
      (footprint "eagle-import:1,6_0,9")
      (libsource (lib "eagle-import") (part "1,6/0,9"))
    )
    (comp (ref "PAD237")
      (value "1,6/0,9")
      (footprint "eagle-import:1,6_0,9")
      (libsource (lib "eagle-import") (part "1,6/0,9"))
    )
    (comp (ref "PAD238")
      (value "1,6/0,9")
      (footprint "eagle-import:1,6_0,9")
      (libsource (lib "eagle-import") (part "1,6/0,9"))
    )
    (comp (ref "PAD239")
      (value "1,6/0,9")
      (footprint "eagle-import:1,6_0,9")
      (libsource (lib "eagle-import") (part "1,6/0,9"))
    )
    (comp (ref "PAD240")
      (value "1,6/0,9")
      (footprint "eagle-import:1,6_0,9")
      (libsource (lib "eagle-import") (part "1,6/0,9"))
    )
    (comp (ref "PAD241")
      (value "1,6/0,9")
      (footprint "eagle-import:1,6_0,9")
      (libsource (lib "eagle-import") (part "1,6/0,9"))
    )
    (comp (ref "PAD242")
      (value "1,6/0,9")
      (footprint "eagle-import:1,6_0,9")
      (libsource (lib "eagle-import") (part "1,6/0,9"))
    )
    (comp (ref "PAD243")
      (value "1,6/0,9")
      (footprint "eagle-import:1,6_0,9")
      (libsource (lib "eagle-import") (part "1,6/0,9"))
    )
    (comp (ref "PAD244")
      (value "1,6/0,9")
      (footprint "eagle-import:1,6_0,9")
      (libsource (lib "eagle-import") (part "1,6/0,9"))
    )
    (comp (ref "PAD245")
      (value "1,6/0,9")
      (footprint "eagle-import:1,6_0,9")
      (libsource (lib "eagle-import") (part "1,6/0,9"))
    )
    (comp (ref "PAD246")
      (value "1,6/0,9")
      (footprint "eagle-import:1,6_0,9")
      (libsource (lib "eagle-import") (part "1,6/0,9"))
    )
    (comp (ref "PAD247")
      (value "1,6/0,9")
      (footprint "eagle-import:1,6_0,9")
      (libsource (lib "eagle-import") (part "1,6/0,9"))
    )
    (comp (ref "PAD248")
      (value "1,6/0,9")
      (footprint "eagle-import:1,6_0,9")
      (libsource (lib "eagle-import") (part "1,6/0,9"))
    )
    (comp (ref "PAD249")
      (value "1,6/0,9")
      (footprint "eagle-import:1,6_0,9")
      (libsource (lib "eagle-import") (part "1,6/0,9"))
    )
    (comp (ref "PAD250")
      (value "1,6/0,9")
      (footprint "eagle-import:1,6_0,9")
      (libsource (lib "eagle-import") (part "1,6/0,9"))
    )
    (comp (ref "PAD251")
      (value "1,6/0,9")
      (footprint "eagle-import:1,6_0,9")
      (libsource (lib "eagle-import") (part "1,6/0,9"))
    )
    (comp (ref "PAD252")
      (value "1,6/0,9")
      (footprint "eagle-import:1,6_0,9")
      (libsource (lib "eagle-import") (part "1,6/0,9"))
    )
    (comp (ref "PAD253")
      (value "1,6/0,9")
      (footprint "eagle-import:1,6_0,9")
      (libsource (lib "eagle-import") (part "1,6/0,9"))
    )
    (comp (ref "PAD254")
      (value "1,6/0,9")
      (footprint "eagle-import:1,6_0,9")
      (libsource (lib "eagle-import") (part "1,6/0,9"))
    )
    (comp (ref "PAD255")
      (value "1,6/0,9")
      (footprint "eagle-import:1,6_0,9")
      (libsource (lib "eagle-import") (part "1,6/0,9"))
    )
    (comp (ref "PAD256")
      (value "1,6/0,9")
      (footprint "eagle-import:1,6_0,9")
      (libsource (lib "eagle-import") (part "1,6/0,9"))
    )
    (comp (ref "PAD257")
      (value "1,6/0,9")
      (footprint "eagle-import:1,6_0,9")
      (libsource (lib "eagle-import") (part "1,6/0,9"))
    )
    (comp (ref "PAD258")
      (value "1,6/0,9")
      (footprint "eagle-import:1,6_0,9")
      (libsource (lib "eagle-import") (part "1,6/0,9"))
    )
    (comp (ref "PAD259")
      (value "1,6/0,9")
      (footprint "eagle-import:1,6_0,9")
      (libsource (lib "eagle-import") (part "1,6/0,9"))
    )
    (comp (ref "PAD260")
      (value "1,6/0,9")
      (footprint "eagle-import:1,6_0,9")
      (libsource (lib "eagle-import") (part "1,6/0,9"))
    )
    (comp (ref "PAD261")
      (value "1,6/0,9")
      (footprint "eagle-import:1,6_0,9")
      (libsource (lib "eagle-import") (part "1,6/0,9"))
    )
    (comp (ref "PAD262")
      (value "1,6/0,9")
      (footprint "eagle-import:1,6_0,9")
      (libsource (lib "eagle-import") (part "1,6/0,9"))
    )
    (comp (ref "PAD263")
      (value "SMD2")
      (footprint "eagle-import:SMD1,27-2,54")
      (libsource (lib "eagle-import") (part "SMD2"))
    )
    (comp (ref "PAD264")
      (value "1,6/0,9")
      (footprint "eagle-import:1,6_0,9")
      (libsource (lib "eagle-import") (part "1,6/0,9"))
    )
    (comp (ref "PAD265")
      (value "1,6/0,9")
      (footprint "eagle-import:1,6_0,9")
      (libsource (lib "eagle-import") (part "1,6/0,9"))
    )
    (comp (ref "PAD266")
      (value "1,6/0,9")
      (footprint "eagle-import:1,6_0,9")
      (libsource (lib "eagle-import") (part "1,6/0,9"))
    )
    (comp (ref "PAD267")
      (value "1,6/0,9")
      (footprint "eagle-import:1,6_0,9")
      (libsource (lib "eagle-import") (part "1,6/0,9"))
    )
    (comp (ref "PAD268")
      (value "1,6/0,9")
      (footprint "eagle-import:1,6_0,9")
      (libsource (lib "eagle-import") (part "1,6/0,9"))
    )
    (comp (ref "PAD269")
      (value "1,6/0,9")
      (footprint "eagle-import:1,6_0,9")
      (libsource (lib "eagle-import") (part "1,6/0,9"))
    )
    (comp (ref "PAD270")
      (value "1,6/0,9")
      (footprint "eagle-import:1,6_0,9")
      (libsource (lib "eagle-import") (part "1,6/0,9"))
    )
    (comp (ref "PAD271")
      (value "1,6/0,9")
      (footprint "eagle-import:1,6_0,9")
      (libsource (lib "eagle-import") (part "1,6/0,9"))
    )
    (comp (ref "PAD272")
      (value "1,6/0,9")
      (footprint "eagle-import:1,6_0,9")
      (libsource (lib "eagle-import") (part "1,6/0,9"))
    )
    (comp (ref "PAD273")
      (value "1,6/0,9")
      (footprint "eagle-import:1,6_0,9")
      (libsource (lib "eagle-import") (part "1,6/0,9"))
    )
    (comp (ref "PAD274")
      (value "1,6/0,9")
      (footprint "eagle-import:1,6_0,9")
      (libsource (lib "eagle-import") (part "1,6/0,9"))
    )
    (comp (ref "PAD275")
      (value "1,6/0,9")
      (footprint "eagle-import:1,6_0,9")
      (libsource (lib "eagle-import") (part "1,6/0,9"))
    )
    (comp (ref "PAD276")
      (value "1,6/0,9")
      (footprint "eagle-import:1,6_0,9")
      (libsource (lib "eagle-import") (part "1,6/0,9"))
    )
    (comp (ref "PAD277")
      (value "1,6/0,9")
      (footprint "eagle-import:1,6_0,9")
      (libsource (lib "eagle-import") (part "1,6/0,9"))
    )
    (comp (ref "PAD278")
      (value "1,6/0,9")
      (footprint "eagle-import:1,6_0,9")
      (libsource (lib "eagle-import") (part "1,6/0,9"))
    )
    (comp (ref "PAD279")
      (value "1,6/0,9")
      (footprint "eagle-import:1,6_0,9")
      (libsource (lib "eagle-import") (part "1,6/0,9"))
    )
    (comp (ref "PAD280")
      (value "1,6/0,9")
      (footprint "eagle-import:1,6_0,9")
      (libsource (lib "eagle-import") (part "1,6/0,9"))
    )
    (comp (ref "PAD281")
      (value "1,6/0,9")
      (footprint "eagle-import:1,6_0,9")
      (libsource (lib "eagle-import") (part "1,6/0,9"))
    )
    (comp (ref "PAD282")
      (value "1,6/0,9")
      (footprint "eagle-import:1,6_0,9")
      (libsource (lib "eagle-import") (part "1,6/0,9"))
    )
    (comp (ref "PAD283")
      (value "1,6/0,9")
      (footprint "eagle-import:1,6_0,9")
      (libsource (lib "eagle-import") (part "1,6/0,9"))
    )
    (comp (ref "PAD284")
      (value "1,6/0,9")
      (footprint "eagle-import:1,6_0,9")
      (libsource (lib "eagle-import") (part "1,6/0,9"))
    )
    (comp (ref "PAD285")
      (value "1,6/0,9")
      (footprint "eagle-import:1,6_0,9")
      (libsource (lib "eagle-import") (part "1,6/0,9"))
    )
    (comp (ref "PAD286")
      (value "1,6/0,9")
      (footprint "eagle-import:1,6_0,9")
      (libsource (lib "eagle-import") (part "1,6/0,9"))
    )
    (comp (ref "PAD287")
      (value "1,6/0,9")
      (footprint "eagle-import:1,6_0,9")
      (libsource (lib "eagle-import") (part "1,6/0,9"))
    )
    (comp (ref "PAD288")
      (value "1,6/0,9")
      (footprint "eagle-import:1,6_0,9")
      (libsource (lib "eagle-import") (part "1,6/0,9"))
    )
    (comp (ref "PAD289")
      (value "1,6/0,9")
      (footprint "eagle-import:1,6_0,9")
      (libsource (lib "eagle-import") (part "1,6/0,9"))
    )
    (comp (ref "PAD290")
      (value "1,6/0,9")
      (footprint "eagle-import:1,6_0,9")
      (libsource (lib "eagle-import") (part "1,6/0,9"))
    )
    (comp (ref "PAD291")
      (value "1,6/0,9")
      (footprint "eagle-import:1,6_0,9")
      (libsource (lib "eagle-import") (part "1,6/0,9"))
    )
    (comp (ref "PAD292")
      (value "1,6/0,9")
      (footprint "eagle-import:1,6_0,9")
      (libsource (lib "eagle-import") (part "1,6/0,9"))
    )
    (comp (ref "PAD293")
      (value "1,6/0,9")
      (footprint "eagle-import:1,6_0,9")
      (libsource (lib "eagle-import") (part "1,6/0,9"))
    )
    (comp (ref "PAD294")
      (value "1,6/0,9")
      (footprint "eagle-import:1,6_0,9")
      (libsource (lib "eagle-import") (part "1,6/0,9"))
    )
    (comp (ref "PAD295")
      (value "1,6/0,9")
      (footprint "eagle-import:1,6_0,9")
      (libsource (lib "eagle-import") (part "1,6/0,9"))
    )
    (comp (ref "PAD296")
      (value "1,6/0,9")
      (footprint "eagle-import:1,6_0,9")
      (libsource (lib "eagle-import") (part "1,6/0,9"))
    )
    (comp (ref "PAD297")
      (value "1,6/0,9")
      (footprint "eagle-import:1,6_0,9")
      (libsource (lib "eagle-import") (part "1,6/0,9"))
    )
    (comp (ref "PAD298")
      (value "1,6/0,9")
      (footprint "eagle-import:1,6_0,9")
      (libsource (lib "eagle-import") (part "1,6/0,9"))
    )
    (comp (ref "PAD299")
      (value "1,6/0,9")
      (footprint "eagle-import:1,6_0,9")
      (libsource (lib "eagle-import") (part "1,6/0,9"))
    )
    (comp (ref "PAD300")
      (value "1,6/0,9")
      (footprint "eagle-import:1,6_0,9")
      (libsource (lib "eagle-import") (part "1,6/0,9"))
    )
    (comp (ref "PAD301")
      (value "1,6/0,9")
      (footprint "eagle-import:1,6_0,9")
      (libsource (lib "eagle-import") (part "1,6/0,9"))
    )
    (comp (ref "PAD302")
      (value "1,6/0,9")
      (footprint "eagle-import:1,6_0,9")
      (libsource (lib "eagle-import") (part "1,6/0,9"))
    )
    (comp (ref "PAD303")
      (value "1,6/0,9")
      (footprint "eagle-import:1,6_0,9")
      (libsource (lib "eagle-import") (part "1,6/0,9"))
    )
    (comp (ref "PAD304")
      (value "1,6/0,9")
      (footprint "eagle-import:1,6_0,9")
      (libsource (lib "eagle-import") (part "1,6/0,9"))
    )
    (comp (ref "PAD305")
      (value "1,6/0,9")
      (footprint "eagle-import:1,6_0,9")
      (libsource (lib "eagle-import") (part "1,6/0,9"))
    )
    (comp (ref "PAD306")
      (value "1,6/0,9")
      (footprint "eagle-import:1,6_0,9")
      (libsource (lib "eagle-import") (part "1,6/0,9"))
    )
    (comp (ref "PAD307")
      (value "1,6/0,9")
      (footprint "eagle-import:1,6_0,9")
      (libsource (lib "eagle-import") (part "1,6/0,9"))
    )
    (comp (ref "PAD308")
      (value "1,6/0,9")
      (footprint "eagle-import:1,6_0,9")
      (libsource (lib "eagle-import") (part "1,6/0,9"))
    )
    (comp (ref "PAD309")
      (value "1,6/0,9")
      (footprint "eagle-import:1,6_0,9")
      (libsource (lib "eagle-import") (part "1,6/0,9"))
    )
    (comp (ref "PAD310")
      (value "1,6/0,9")
      (footprint "eagle-import:1,6_0,9")
      (libsource (lib "eagle-import") (part "1,6/0,9"))
    )
    (comp (ref "PAD311")
      (value "1,6/0,9")
      (footprint "eagle-import:1,6_0,9")
      (libsource (lib "eagle-import") (part "1,6/0,9"))
    )
    (comp (ref "PAD312")
      (value "1,6/0,9")
      (footprint "eagle-import:1,6_0,9")
      (libsource (lib "eagle-import") (part "1,6/0,9"))
    )
    (comp (ref "PAD313")
      (value "1,6/0,9")
      (footprint "eagle-import:1,6_0,9")
      (libsource (lib "eagle-import") (part "1,6/0,9"))
    )
    (comp (ref "PAD314")
      (value "1,6/0,9")
      (footprint "eagle-import:1,6_0,9")
      (libsource (lib "eagle-import") (part "1,6/0,9"))
    )
    (comp (ref "PAD315")
      (value "1,6/0,9")
      (footprint "eagle-import:1,6_0,9")
      (libsource (lib "eagle-import") (part "1,6/0,9"))
    )
    (comp (ref "PAD316")
      (value "1,6/0,9")
      (footprint "eagle-import:1,6_0,9")
      (libsource (lib "eagle-import") (part "1,6/0,9"))
    )
    (comp (ref "PAD317")
      (value "1,6/0,9")
      (footprint "eagle-import:1,6_0,9")
      (libsource (lib "eagle-import") (part "1,6/0,9"))
    )
    (comp (ref "PAD318")
      (value "1,6/0,9")
      (footprint "eagle-import:1,6_0,9")
      (libsource (lib "eagle-import") (part "1,6/0,9"))
    )
    (comp (ref "PAD319")
      (value "1,6/0,9")
      (footprint "eagle-import:1,6_0,9")
      (libsource (lib "eagle-import") (part "1,6/0,9"))
    )
    (comp (ref "PAD320")
      (value "1,6/0,9")
      (footprint "eagle-import:1,6_0,9")
      (libsource (lib "eagle-import") (part "1,6/0,9"))
    )
    (comp (ref "PAD321")
      (value "1,6/0,9")
      (footprint "eagle-import:1,6_0,9")
      (libsource (lib "eagle-import") (part "1,6/0,9"))
    )
    (comp (ref "PAD322")
      (value "1,6/0,9")
      (footprint "eagle-import:1,6_0,9")
      (libsource (lib "eagle-import") (part "1,6/0,9"))
    )
    (comp (ref "PAD323")
      (value "1,6/0,9")
      (footprint "eagle-import:1,6_0,9")
      (libsource (lib "eagle-import") (part "1,6/0,9"))
    )
    (comp (ref "PAD324")
      (value "1,6/0,9")
      (footprint "eagle-import:1,6_0,9")
      (libsource (lib "eagle-import") (part "1,6/0,9"))
    )
    (comp (ref "PAD325")
      (value "1,6/0,9")
      (footprint "eagle-import:1,6_0,9")
      (libsource (lib "eagle-import") (part "1,6/0,9"))
    )
    (comp (ref "PAD326")
      (value "1,6/0,9")
      (footprint "eagle-import:1,6_0,9")
      (libsource (lib "eagle-import") (part "1,6/0,9"))
    )
    (comp (ref "PAD327")
      (value "1,6/0,9")
      (footprint "eagle-import:1,6_0,9")
      (libsource (lib "eagle-import") (part "1,6/0,9"))
    )
    (comp (ref "PAD328")
      (value "1,6/0,9")
      (footprint "eagle-import:1,6_0,9")
      (libsource (lib "eagle-import") (part "1,6/0,9"))
    )
    (comp (ref "PAD329")
      (value "1,6/0,9")
      (footprint "eagle-import:1,6_0,9")
      (libsource (lib "eagle-import") (part "1,6/0,9"))
    )
    (comp (ref "PAD330")
      (value "1,6/0,9")
      (footprint "eagle-import:1,6_0,9")
      (libsource (lib "eagle-import") (part "1,6/0,9"))
    )
    (comp (ref "PAD331")
      (value "1,6/0,9")
      (footprint "eagle-import:1,6_0,9")
      (libsource (lib "eagle-import") (part "1,6/0,9"))
    )
    (comp (ref "PAD332")
      (value "1,6/0,9")
      (footprint "eagle-import:1,6_0,9")
      (libsource (lib "eagle-import") (part "1,6/0,9"))
    )
    (comp (ref "PAD333")
      (value "1,6/0,9")
      (footprint "eagle-import:1,6_0,9")
      (libsource (lib "eagle-import") (part "1,6/0,9"))
    )
    (comp (ref "PAD334")
      (value "1,6/0,9")
      (footprint "eagle-import:1,6_0,9")
      (libsource (lib "eagle-import") (part "1,6/0,9"))
    )
    (comp (ref "PAD335")
      (value "1,6/0,9")
      (footprint "eagle-import:1,6_0,9")
      (libsource (lib "eagle-import") (part "1,6/0,9"))
    )
    (comp (ref "PAD336")
      (value "1,6/0,9")
      (footprint "eagle-import:1,6_0,9")
      (libsource (lib "eagle-import") (part "1,6/0,9"))
    )
    (comp (ref "PAD337")
      (value "1,6/0,9")
      (footprint "eagle-import:1,6_0,9")
      (libsource (lib "eagle-import") (part "1,6/0,9"))
    )
    (comp (ref "PAD338")
      (value "1,6/0,9")
      (footprint "eagle-import:1,6_0,9")
      (libsource (lib "eagle-import") (part "1,6/0,9"))
    )
    (comp (ref "PAD339")
      (value "1,6/0,9")
      (footprint "eagle-import:1,6_0,9")
      (libsource (lib "eagle-import") (part "1,6/0,9"))
    )
    (comp (ref "PAD340")
      (value "1,6/0,9")
      (footprint "eagle-import:1,6_0,9")
      (libsource (lib "eagle-import") (part "1,6/0,9"))
    )
    (comp (ref "PAD341")
      (value "1,6/0,9")
      (footprint "eagle-import:1,6_0,9")
      (libsource (lib "eagle-import") (part "1,6/0,9"))
    )
    (comp (ref "PAD342")
      (value "1,6/0,9")
      (footprint "eagle-import:1,6_0,9")
      (libsource (lib "eagle-import") (part "1,6/0,9"))
    )
    (comp (ref "PAD343")
      (value "1,6/0,9")
      (footprint "eagle-import:1,6_0,9")
      (libsource (lib "eagle-import") (part "1,6/0,9"))
    )
    (comp (ref "PAD344")
      (value "1,6/0,9")
      (footprint "eagle-import:1,6_0,9")
      (libsource (lib "eagle-import") (part "1,6/0,9"))
    )
    (comp (ref "PAD345")
      (value "1,6/0,9")
      (footprint "eagle-import:1,6_0,9")
      (libsource (lib "eagle-import") (part "1,6/0,9"))
    )
    (comp (ref "PAD346")
      (value "1,6/0,9")
      (footprint "eagle-import:1,6_0,9")
      (libsource (lib "eagle-import") (part "1,6/0,9"))
    )
    (comp (ref "PAD347")
      (value "1,6/0,9")
      (footprint "eagle-import:1,6_0,9")
      (libsource (lib "eagle-import") (part "1,6/0,9"))
    )
    (comp (ref "PAD348")
      (value "1,6/0,9")
      (footprint "eagle-import:1,6_0,9")
      (libsource (lib "eagle-import") (part "1,6/0,9"))
    )
    (comp (ref "PAD349")
      (value "1,6/0,9")
      (footprint "eagle-import:1,6_0,9")
      (libsource (lib "eagle-import") (part "1,6/0,9"))
    )
    (comp (ref "PAD350")
      (value "1,6/0,9")
      (footprint "eagle-import:1,6_0,9")
      (libsource (lib "eagle-import") (part "1,6/0,9"))
    )
    (comp (ref "PAD351")
      (value "1,6/0,9")
      (footprint "eagle-import:1,6_0,9")
      (libsource (lib "eagle-import") (part "1,6/0,9"))
    )
    (comp (ref "PAD352")
      (value "1,6/0,9")
      (footprint "eagle-import:1,6_0,9")
      (libsource (lib "eagle-import") (part "1,6/0,9"))
    )
    (comp (ref "PAD353")
      (value "1,6/0,9")
      (footprint "eagle-import:1,6_0,9")
      (libsource (lib "eagle-import") (part "1,6/0,9"))
    )
    (comp (ref "PAD354")
      (value "1,6/0,9")
      (footprint "eagle-import:1,6_0,9")
      (libsource (lib "eagle-import") (part "1,6/0,9"))
    )
    (comp (ref "PAD355")
      (value "1,6/0,9")
      (footprint "eagle-import:1,6_0,9")
      (libsource (lib "eagle-import") (part "1,6/0,9"))
    )
    (comp (ref "PAD356")
      (value "1,6/0,9")
      (footprint "eagle-import:1,6_0,9")
      (libsource (lib "eagle-import") (part "1,6/0,9"))
    )
    (comp (ref "PAD357")
      (value "1,6/0,9")
      (footprint "eagle-import:1,6_0,9")
      (libsource (lib "eagle-import") (part "1,6/0,9"))
    )
    (comp (ref "PAD358")
      (value "1,6/0,9")
      (footprint "eagle-import:1,6_0,9")
      (libsource (lib "eagle-import") (part "1,6/0,9"))
    )
    (comp (ref "PAD359")
      (value "1,6/0,9")
      (footprint "eagle-import:1,6_0,9")
      (libsource (lib "eagle-import") (part "1,6/0,9"))
    )
    (comp (ref "PAD360")
      (value "1,6/0,9")
      (footprint "eagle-import:1,6_0,9")
      (libsource (lib "eagle-import") (part "1,6/0,9"))
    )
    (comp (ref "PAD361")
      (value "1,6/0,9")
      (footprint "eagle-import:1,6_0,9")
      (libsource (lib "eagle-import") (part "1,6/0,9"))
    )
    (comp (ref "PAD362")
      (value "1,6/0,9")
      (footprint "eagle-import:1,6_0,9")
      (libsource (lib "eagle-import") (part "1,6/0,9"))
    )
    (comp (ref "PAD363")
      (value "1,6/0,9")
      (footprint "eagle-import:1,6_0,9")
      (libsource (lib "eagle-import") (part "1,6/0,9"))
    )
    (comp (ref "PAD364")
      (value "1,6/0,9")
      (footprint "eagle-import:1,6_0,9")
      (libsource (lib "eagle-import") (part "1,6/0,9"))
    )
    (comp (ref "PAD365")
      (value "1,6/0,9")
      (footprint "eagle-import:1,6_0,9")
      (libsource (lib "eagle-import") (part "1,6/0,9"))
    )
    (comp (ref "PAD366")
      (value "1,6/0,9")
      (footprint "eagle-import:1,6_0,9")
      (libsource (lib "eagle-import") (part "1,6/0,9"))
    )
    (comp (ref "PAD367")
      (value "1,6/0,9")
      (footprint "eagle-import:1,6_0,9")
      (libsource (lib "eagle-import") (part "1,6/0,9"))
    )
    (comp (ref "PAD368")
      (value "1,6/0,9")
      (footprint "eagle-import:1,6_0,9")
      (libsource (lib "eagle-import") (part "1,6/0,9"))
    )
    (comp (ref "PAD369")
      (value "1,6/0,9")
      (footprint "eagle-import:1,6_0,9")
      (libsource (lib "eagle-import") (part "1,6/0,9"))
    )
    (comp (ref "PAD370")
      (value "1,6/0,9")
      (footprint "eagle-import:1,6_0,9")
      (libsource (lib "eagle-import") (part "1,6/0,9"))
    )
    (comp (ref "PAD371")
      (value "1,6/0,9")
      (footprint "eagle-import:1,6_0,9")
      (libsource (lib "eagle-import") (part "1,6/0,9"))
    )
    (comp (ref "PAD372")
      (value "1,6/0,9")
      (footprint "eagle-import:1,6_0,9")
      (libsource (lib "eagle-import") (part "1,6/0,9"))
    )
    (comp (ref "PAD373")
      (value "1,6/0,9")
      (footprint "eagle-import:1,6_0,9")
      (libsource (lib "eagle-import") (part "1,6/0,9"))
    )
    (comp (ref "PAD374")
      (value "1,6/0,9")
      (footprint "eagle-import:1,6_0,9")
      (libsource (lib "eagle-import") (part "1,6/0,9"))
    )
    (comp (ref "PAD375")
      (value "1,6/0,9")
      (footprint "eagle-import:1,6_0,9")
      (libsource (lib "eagle-import") (part "1,6/0,9"))
    )
    (comp (ref "PAD376")
      (value "1,6/0,9")
      (footprint "eagle-import:1,6_0,9")
      (libsource (lib "eagle-import") (part "1,6/0,9"))
    )
    (comp (ref "PAD377")
      (value "1,6/0,9")
      (footprint "eagle-import:1,6_0,9")
      (libsource (lib "eagle-import") (part "1,6/0,9"))
    )
    (comp (ref "PAD378")
      (value "1,6/0,9")
      (footprint "eagle-import:1,6_0,9")
      (libsource (lib "eagle-import") (part "1,6/0,9"))
    )
    (comp (ref "PAD379")
      (value "1,6/0,9")
      (footprint "eagle-import:1,6_0,9")
      (libsource (lib "eagle-import") (part "1,6/0,9"))
    )
    (comp (ref "PAD380")
      (value "1,6/0,9")
      (footprint "eagle-import:1,6_0,9")
      (libsource (lib "eagle-import") (part "1,6/0,9"))
    )
    (comp (ref "PAD381")
      (value "1,6/0,9")
      (footprint "eagle-import:1,6_0,9")
      (libsource (lib "eagle-import") (part "1,6/0,9"))
    )
    (comp (ref "PAD382")
      (value "1,6/0,9")
      (footprint "eagle-import:1,6_0,9")
      (libsource (lib "eagle-import") (part "1,6/0,9"))
    )
    (comp (ref "PAD383")
      (value "1,6/0,9")
      (footprint "eagle-import:1,6_0,9")
      (libsource (lib "eagle-import") (part "1,6/0,9"))
    )
    (comp (ref "PAD384")
      (value "1,6/0,9")
      (footprint "eagle-import:1,6_0,9")
      (libsource (lib "eagle-import") (part "1,6/0,9"))
    )
    (comp (ref "PAD385")
      (value "SMD2")
      (footprint "eagle-import:SMD1,27-2,54")
      (libsource (lib "eagle-import") (part "SMD2"))
    )
    (comp (ref "PAD386")
      (value "SMD2")
      (footprint "eagle-import:SMD1,27-2,54")
      (libsource (lib "eagle-import") (part "SMD2"))
    )
    (comp (ref "PAD387")
      (value "SMD2")
      (footprint "eagle-import:SMD1,27-2,54")
      (libsource (lib "eagle-import") (part "SMD2"))
    )
    (comp (ref "PAD388")
      (value "SMD2")
      (footprint "eagle-import:SMD1,27-2,54")
      (libsource (lib "eagle-import") (part "SMD2"))
    )
    (comp (ref "PAD389")
      (value "1,6/0,9")
      (footprint "eagle-import:1,6_0,9")
      (libsource (lib "eagle-import") (part "1,6/0,9"))
    )
    (comp (ref "PAD390")
      (value "1,6/0,9")
      (footprint "eagle-import:1,6_0,9")
      (libsource (lib "eagle-import") (part "1,6/0,9"))
    )
    (comp (ref "PAD391")
      (value "1,6/0,9")
      (footprint "eagle-import:1,6_0,9")
      (libsource (lib "eagle-import") (part "1,6/0,9"))
    )
    (comp (ref "PAD392")
      (value "1,6/0,9")
      (footprint "eagle-import:1,6_0,9")
      (libsource (lib "eagle-import") (part "1,6/0,9"))
    )
    (comp (ref "PAD393")
      (value "1,6/0,9")
      (footprint "eagle-import:1,6_0,9")
      (libsource (lib "eagle-import") (part "1,6/0,9"))
    )
    (comp (ref "PAD394")
      (value "1,6/0,9")
      (footprint "eagle-import:1,6_0,9")
      (libsource (lib "eagle-import") (part "1,6/0,9"))
    )
    (comp (ref "PAD395")
      (value "1,6/0,9")
      (footprint "eagle-import:1,6_0,9")
      (libsource (lib "eagle-import") (part "1,6/0,9"))
    )
    (comp (ref "PAD396")
      (value "1,6/0,9")
      (footprint "eagle-import:1,6_0,9")
      (libsource (lib "eagle-import") (part "1,6/0,9"))
    )
    (comp (ref "PAD397")
      (value "1,6/0,9")
      (footprint "eagle-import:1,6_0,9")
      (libsource (lib "eagle-import") (part "1,6/0,9"))
    )
    (comp (ref "PAD398")
      (value "1,6/0,9")
      (footprint "eagle-import:1,6_0,9")
      (libsource (lib "eagle-import") (part "1,6/0,9"))
    )
    (comp (ref "PAD399")
      (value "SMD2")
      (footprint "eagle-import:SMD1,27-2,54")
      (libsource (lib "eagle-import") (part "SMD2"))
    )
    (comp (ref "PAD400")
      (value "SMD2")
      (footprint "eagle-import:SMD1,27-2,54")
      (libsource (lib "eagle-import") (part "SMD2"))
    )
    (comp (ref "PAD401")
      (value "SMD2")
      (footprint "eagle-import:SMD1,27-2,54")
      (libsource (lib "eagle-import") (part "SMD2"))
    )
    (comp (ref "PAD402")
      (value "SMD2")
      (footprint "eagle-import:SMD1,27-2,54")
      (libsource (lib "eagle-import") (part "SMD2"))
    )
    (comp (ref "PAD403")
      (value "1,6/0,9")
      (footprint "eagle-import:1,6_0,9")
      (libsource (lib "eagle-import") (part "1,6/0,9"))
    )
    (comp (ref "PAD404")
      (value "1,6/0,9")
      (footprint "eagle-import:1,6_0,9")
      (libsource (lib "eagle-import") (part "1,6/0,9"))
    )
    (comp (ref "PAD405")
      (value "1,6/0,9")
      (footprint "eagle-import:1,6_0,9")
      (libsource (lib "eagle-import") (part "1,6/0,9"))
    )
    (comp (ref "PAD406")
      (value "1,6/0,9")
      (footprint "eagle-import:1,6_0,9")
      (libsource (lib "eagle-import") (part "1,6/0,9"))
    )
    (comp (ref "PAD407")
      (value "1,6/0,9")
      (footprint "eagle-import:1,6_0,9")
      (libsource (lib "eagle-import") (part "1,6/0,9"))
    )
    (comp (ref "PAD408")
      (value "1,6/0,9")
      (footprint "eagle-import:1,6_0,9")
      (libsource (lib "eagle-import") (part "1,6/0,9"))
    )
    (comp (ref "PAD409")
      (value "1,6/0,9")
      (footprint "eagle-import:1,6_0,9")
      (libsource (lib "eagle-import") (part "1,6/0,9"))
    )
    (comp (ref "PAD410")
      (value "1,6/0,9")
      (footprint "eagle-import:1,6_0,9")
      (libsource (lib "eagle-import") (part "1,6/0,9"))
    )
    (comp (ref "PAD411")
      (value "1,6/0,9")
      (footprint "eagle-import:1,6_0,9")
      (libsource (lib "eagle-import") (part "1,6/0,9"))
    )
    (comp (ref "PAD412")
      (value "1,6/0,9")
      (footprint "eagle-import:1,6_0,9")
      (libsource (lib "eagle-import") (part "1,6/0,9"))
    )
    (comp (ref "PAD413")
      (value "SMD2")
      (footprint "eagle-import:SMD1,27-2,54")
      (libsource (lib "eagle-import") (part "SMD2"))
    )
    (comp (ref "PAD414")
      (value "SMD2")
      (footprint "eagle-import:SMD1,27-2,54")
      (libsource (lib "eagle-import") (part "SMD2"))
    )
    (comp (ref "PAD415")
      (value "SMD2")
      (footprint "eagle-import:SMD1,27-2,54")
      (libsource (lib "eagle-import") (part "SMD2"))
    )
    (comp (ref "PAD416")
      (value "SMD2")
      (footprint "eagle-import:SMD1,27-2,54")
      (libsource (lib "eagle-import") (part "SMD2"))
    )
    (comp (ref "PAD417")
      (value "1,6/0,9")
      (footprint "eagle-import:1,6_0,9")
      (libsource (lib "eagle-import") (part "1,6/0,9"))
    )
    (comp (ref "PAD418")
      (value "1,6/0,9")
      (footprint "eagle-import:1,6_0,9")
      (libsource (lib "eagle-import") (part "1,6/0,9"))
    )
    (comp (ref "PAD419")
      (value "1,6/0,9")
      (footprint "eagle-import:1,6_0,9")
      (libsource (lib "eagle-import") (part "1,6/0,9"))
    )
    (comp (ref "PAD420")
      (value "1,6/0,9")
      (footprint "eagle-import:1,6_0,9")
      (libsource (lib "eagle-import") (part "1,6/0,9"))
    )
    (comp (ref "PAD421")
      (value "1,6/0,9")
      (footprint "eagle-import:1,6_0,9")
      (libsource (lib "eagle-import") (part "1,6/0,9"))
    )
    (comp (ref "PAD422")
      (value "1,6/0,9")
      (footprint "eagle-import:1,6_0,9")
      (libsource (lib "eagle-import") (part "1,6/0,9"))
    )
    (comp (ref "PAD423")
      (value "1,6/0,9")
      (footprint "eagle-import:1,6_0,9")
      (libsource (lib "eagle-import") (part "1,6/0,9"))
    )
    (comp (ref "PAD424")
      (value "1,6/0,9")
      (footprint "eagle-import:1,6_0,9")
      (libsource (lib "eagle-import") (part "1,6/0,9"))
    )
    (comp (ref "PAD425")
      (value "1,6/0,9")
      (footprint "eagle-import:1,6_0,9")
      (libsource (lib "eagle-import") (part "1,6/0,9"))
    )
    (comp (ref "PAD426")
      (value "1,6/0,9")
      (footprint "eagle-import:1,6_0,9")
      (libsource (lib "eagle-import") (part "1,6/0,9"))
    )
    (comp (ref "PAD427")
      (value "SMD2")
      (footprint "eagle-import:SMD1,27-2,54")
      (libsource (lib "eagle-import") (part "SMD2"))
    )
    (comp (ref "PAD428")
      (value "SMD2")
      (footprint "eagle-import:SMD1,27-2,54")
      (libsource (lib "eagle-import") (part "SMD2"))
    )
    (comp (ref "PAD429")
      (value "SMD2")
      (footprint "eagle-import:SMD1,27-2,54")
      (libsource (lib "eagle-import") (part "SMD2"))
    )
    (comp (ref "PAD430")
      (value "SMD2")
      (footprint "eagle-import:SMD1,27-2,54")
      (libsource (lib "eagle-import") (part "SMD2"))
    )
    (comp (ref "PAD431")
      (value "1,6/0,9")
      (footprint "eagle-import:1,6_0,9")
      (libsource (lib "eagle-import") (part "1,6/0,9"))
    )
    (comp (ref "PAD432")
      (value "1,6/0,9")
      (footprint "eagle-import:1,6_0,9")
      (libsource (lib "eagle-import") (part "1,6/0,9"))
    )
    (comp (ref "PAD433")
      (value "1,6/0,9")
      (footprint "eagle-import:1,6_0,9")
      (libsource (lib "eagle-import") (part "1,6/0,9"))
    )
    (comp (ref "PAD434")
      (value "1,6/0,9")
      (footprint "eagle-import:1,6_0,9")
      (libsource (lib "eagle-import") (part "1,6/0,9"))
    )
    (comp (ref "PAD435")
      (value "1,6/0,9")
      (footprint "eagle-import:1,6_0,9")
      (libsource (lib "eagle-import") (part "1,6/0,9"))
    )
    (comp (ref "PAD436")
      (value "1,6/0,9")
      (footprint "eagle-import:1,6_0,9")
      (libsource (lib "eagle-import") (part "1,6/0,9"))
    )
    (comp (ref "PAD437")
      (value "1,6/0,9")
      (footprint "eagle-import:1,6_0,9")
      (libsource (lib "eagle-import") (part "1,6/0,9"))
    )
    (comp (ref "PAD438")
      (value "1,6/0,9")
      (footprint "eagle-import:1,6_0,9")
      (libsource (lib "eagle-import") (part "1,6/0,9"))
    )
    (comp (ref "PAD439")
      (value "1,6/0,9")
      (footprint "eagle-import:1,6_0,9")
      (libsource (lib "eagle-import") (part "1,6/0,9"))
    )
    (comp (ref "PAD440")
      (value "SMD2")
      (footprint "eagle-import:SMD1,27-2,54")
      (libsource (lib "eagle-import") (part "SMD2"))
    )
    (comp (ref "PAD441")
      (value "SMD2")
      (footprint "eagle-import:SMD1,27-2,54")
      (libsource (lib "eagle-import") (part "SMD2"))
    )
    (comp (ref "PAD442")
      (value "SMD2")
      (footprint "eagle-import:SMD1,27-2,54")
      (libsource (lib "eagle-import") (part "SMD2"))
    )
    (comp (ref "PAD443")
      (value "SMD2")
      (footprint "eagle-import:SMD1,27-2,54")
      (libsource (lib "eagle-import") (part "SMD2"))
    )
    (comp (ref "PAD444")
      (value "SMD2")
      (footprint "eagle-import:SMD1,27-2,54")
      (libsource (lib "eagle-import") (part "SMD2"))
    )
    (comp (ref "PAD445")
      (value "1,6/0,9")
      (footprint "eagle-import:1,6_0,9")
      (libsource (lib "eagle-import") (part "1,6/0,9"))
    )
    (comp (ref "PAD446")
      (value "1,6/0,9")
      (footprint "eagle-import:1,6_0,9")
      (libsource (lib "eagle-import") (part "1,6/0,9"))
    )
    (comp (ref "PAD447")
      (value "1,6/0,9")
      (footprint "eagle-import:1,6_0,9")
      (libsource (lib "eagle-import") (part "1,6/0,9"))
    )
    (comp (ref "PAD448")
      (value "1,6/0,9")
      (footprint "eagle-import:1,6_0,9")
      (libsource (lib "eagle-import") (part "1,6/0,9"))
    )
    (comp (ref "PAD449")
      (value "1,6/0,9")
      (footprint "eagle-import:1,6_0,9")
      (libsource (lib "eagle-import") (part "1,6/0,9"))
    )
    (comp (ref "PAD450")
      (value "1,6/0,9")
      (footprint "eagle-import:1,6_0,9")
      (libsource (lib "eagle-import") (part "1,6/0,9"))
    )
    (comp (ref "PAD451")
      (value "1,6/0,9")
      (footprint "eagle-import:1,6_0,9")
      (libsource (lib "eagle-import") (part "1,6/0,9"))
    )
    (comp (ref "PAD452")
      (value "1,6/0,9")
      (footprint "eagle-import:1,6_0,9")
      (libsource (lib "eagle-import") (part "1,6/0,9"))
    )
    (comp (ref "PAD453")
      (value "1,6/0,9")
      (footprint "eagle-import:1,6_0,9")
      (libsource (lib "eagle-import") (part "1,6/0,9"))
    )
    (comp (ref "PAD454")
      (value "1,6/0,9")
      (footprint "eagle-import:1,6_0,9")
      (libsource (lib "eagle-import") (part "1,6/0,9"))
    )
    (comp (ref "PAD455")
      (value "1,6/0,9")
      (footprint "eagle-import:1,6_0,9")
      (libsource (lib "eagle-import") (part "1,6/0,9"))
    )
    (comp (ref "PAD456")
      (value "1,6/0,9")
      (footprint "eagle-import:1,6_0,9")
      (libsource (lib "eagle-import") (part "1,6/0,9"))
    )
    (comp (ref "PAD457")
      (value "1,6/0,9")
      (footprint "eagle-import:1,6_0,9")
      (libsource (lib "eagle-import") (part "1,6/0,9"))
    )
    (comp (ref "PAD458")
      (value "SMD2")
      (footprint "eagle-import:SMD1,27-2,54")
      (libsource (lib "eagle-import") (part "SMD2"))
    )
    (comp (ref "PAD459")
      (value "1,6/0,9")
      (footprint "eagle-import:1,6_0,9")
      (libsource (lib "eagle-import") (part "1,6/0,9"))
    )
    (comp (ref "PAD460")
      (value "1,6/0,9")
      (footprint "eagle-import:1,6_0,9")
      (libsource (lib "eagle-import") (part "1,6/0,9"))
    )
    (comp (ref "PAD461")
      (value "1,6/0,9")
      (footprint "eagle-import:1,6_0,9")
      (libsource (lib "eagle-import") (part "1,6/0,9"))
    )
    (comp (ref "PAD462")
      (value "1,6/0,9")
      (footprint "eagle-import:1,6_0,9")
      (libsource (lib "eagle-import") (part "1,6/0,9"))
    )
    (comp (ref "PAD463")
      (value "1,6/0,9")
      (footprint "eagle-import:1,6_0,9")
      (libsource (lib "eagle-import") (part "1,6/0,9"))
    )
    (comp (ref "PAD464")
      (value "1,6/0,9")
      (footprint "eagle-import:1,6_0,9")
      (libsource (lib "eagle-import") (part "1,6/0,9"))
    )
    (comp (ref "PAD465")
      (value "1,6/0,9")
      (footprint "eagle-import:1,6_0,9")
      (libsource (lib "eagle-import") (part "1,6/0,9"))
    )
    (comp (ref "PAD466")
      (value "1,6/0,9")
      (footprint "eagle-import:1,6_0,9")
      (libsource (lib "eagle-import") (part "1,6/0,9"))
    )
    (comp (ref "PAD467")
      (value "1,6/0,9")
      (footprint "eagle-import:1,6_0,9")
      (libsource (lib "eagle-import") (part "1,6/0,9"))
    )
    (comp (ref "PAD468")
      (value "1,6/0,9")
      (footprint "eagle-import:1,6_0,9")
      (libsource (lib "eagle-import") (part "1,6/0,9"))
    )
    (comp (ref "PAD469")
      (value "1,6/0,9")
      (footprint "eagle-import:1,6_0,9")
      (libsource (lib "eagle-import") (part "1,6/0,9"))
    )
    (comp (ref "PAD470")
      (value "1,6/0,9")
      (footprint "eagle-import:1,6_0,9")
      (libsource (lib "eagle-import") (part "1,6/0,9"))
    )
    (comp (ref "PAD471")
      (value "1,6/0,9")
      (footprint "eagle-import:1,6_0,9")
      (libsource (lib "eagle-import") (part "1,6/0,9"))
    )
    (comp (ref "PAD472")
      (value "1,6/0,9")
      (footprint "eagle-import:1,6_0,9")
      (libsource (lib "eagle-import") (part "1,6/0,9"))
    )
    (comp (ref "PAD473")
      (value "1,6/0,9")
      (footprint "eagle-import:1,6_0,9")
      (libsource (lib "eagle-import") (part "1,6/0,9"))
    )
    (comp (ref "PAD474")
      (value "1,6/0,9")
      (footprint "eagle-import:1,6_0,9")
      (libsource (lib "eagle-import") (part "1,6/0,9"))
    )
    (comp (ref "PAD475")
      (value "1,6/0,9")
      (footprint "eagle-import:1,6_0,9")
      (libsource (lib "eagle-import") (part "1,6/0,9"))
    )
    (comp (ref "PAD476")
      (value "1,6/0,9")
      (footprint "eagle-import:1,6_0,9")
      (libsource (lib "eagle-import") (part "1,6/0,9"))
    )
    (comp (ref "PAD477")
      (value "1,6/0,9")
      (footprint "eagle-import:1,6_0,9")
      (libsource (lib "eagle-import") (part "1,6/0,9"))
    )
    (comp (ref "PAD478")
      (value "1,6/0,9")
      (footprint "eagle-import:1,6_0,9")
      (libsource (lib "eagle-import") (part "1,6/0,9"))
    )
    (comp (ref "PAD479")
      (value "1,6/0,9")
      (footprint "eagle-import:1,6_0,9")
      (libsource (lib "eagle-import") (part "1,6/0,9"))
    )
    (comp (ref "PAD480")
      (value "1,6/0,9")
      (footprint "eagle-import:1,6_0,9")
      (libsource (lib "eagle-import") (part "1,6/0,9"))
    )
    (comp (ref "PAD481")
      (value "SMD2")
      (footprint "eagle-import:SMD1,27-2,54")
      (libsource (lib "eagle-import") (part "SMD2"))
    )
    (comp (ref "PAD482")
      (value "SMD2")
      (footprint "eagle-import:SMD1,27-2,54")
      (libsource (lib "eagle-import") (part "SMD2"))
    )
    (comp (ref "PAD483")
      (value "SMD2")
      (footprint "eagle-import:SMD1,27-2,54")
      (libsource (lib "eagle-import") (part "SMD2"))
    )
    (comp (ref "PAD484")
      (value "SMD2")
      (footprint "eagle-import:SMD1,27-2,54")
      (libsource (lib "eagle-import") (part "SMD2"))
    )
    (comp (ref "PAD485")
      (value "SMD2")
      (footprint "eagle-import:SMD1,27-2,54")
      (libsource (lib "eagle-import") (part "SMD2"))
    )
    (comp (ref "PAD486")
      (value "SMD2")
      (footprint "eagle-import:SMD1,27-2,54")
      (libsource (lib "eagle-import") (part "SMD2"))
    )
    (comp (ref "PAD487")
      (value "SMD2")
      (footprint "eagle-import:SMD1,27-2,54")
      (libsource (lib "eagle-import") (part "SMD2"))
    )
    (comp (ref "PAD488")
      (value "SMD2")
      (footprint "eagle-import:SMD1,27-2,54")
      (libsource (lib "eagle-import") (part "SMD2"))
    )
    (comp (ref "PAD489")
      (value "SMD2")
      (footprint "eagle-import:SMD1,27-2,54")
      (libsource (lib "eagle-import") (part "SMD2"))
    )
    (comp (ref "PAD490")
      (value "SMD2")
      (footprint "eagle-import:SMD1,27-2,54")
      (libsource (lib "eagle-import") (part "SMD2"))
    )
    (comp (ref "PAD491")
      (value "SMD2")
      (footprint "eagle-import:SMD1,27-2,54")
      (libsource (lib "eagle-import") (part "SMD2"))
    )
    (comp (ref "PAD492")
      (value "SMD2")
      (footprint "eagle-import:SMD1,27-2,54")
      (libsource (lib "eagle-import") (part "SMD2"))
    )
    (comp (ref "PAD493")
      (value "SMD2")
      (footprint "eagle-import:SMD1,27-2,54")
      (libsource (lib "eagle-import") (part "SMD2"))
    )
    (comp (ref "PAD494")
      (value "SMD2")
      (footprint "eagle-import:SMD1,27-2,54")
      (libsource (lib "eagle-import") (part "SMD2"))
    )
    (comp (ref "PAD495")
      (value "SMD2")
      (footprint "eagle-import:SMD1,27-2,54")
      (libsource (lib "eagle-import") (part "SMD2"))
    )
    (comp (ref "PAD496")
      (value "SMD2")
      (footprint "eagle-import:SMD1,27-2,54")
      (libsource (lib "eagle-import") (part "SMD2"))
    )
    (comp (ref "PAD497")
      (value "SMD2")
      (footprint "eagle-import:SMD1,27-2,54")
      (libsource (lib "eagle-import") (part "SMD2"))
    )
    (comp (ref "PAD498")
      (value "SMD2")
      (footprint "eagle-import:SMD1,27-2,54")
      (libsource (lib "eagle-import") (part "SMD2"))
    )
    (comp (ref "PAD499")
      (value "SMD2")
      (footprint "eagle-import:SMD1,27-2,54")
      (libsource (lib "eagle-import") (part "SMD2"))
    )
    (comp (ref "PAD500")
      (value "SMD2")
      (footprint "eagle-import:SMD1,27-2,54")
      (libsource (lib "eagle-import") (part "SMD2"))
    )
    (comp (ref "PAD501")
      (value "SMD2")
      (footprint "eagle-import:SMD1,27-2,54")
      (libsource (lib "eagle-import") (part "SMD2"))
    )
    (comp (ref "PAD502")
      (value "SMD2")
      (footprint "eagle-import:SMD1,27-2,54")
      (libsource (lib "eagle-import") (part "SMD2"))
    )
    (comp (ref "PAD503")
      (value "SMD2")
      (footprint "eagle-import:SMD1,27-2,54")
      (libsource (lib "eagle-import") (part "SMD2"))
    )
    (comp (ref "PAD504")
      (value "SMD2")
      (footprint "eagle-import:SMD1,27-2,54")
      (libsource (lib "eagle-import") (part "SMD2"))
    )
    (comp (ref "PAD505")
      (value "SMD2")
      (footprint "eagle-import:SMD1,27-2,54")
      (libsource (lib "eagle-import") (part "SMD2"))
    )
    (comp (ref "PAD506")
      (value "SMD2")
      (footprint "eagle-import:SMD1,27-2,54")
      (libsource (lib "eagle-import") (part "SMD2"))
    )
    (comp (ref "PAD507")
      (value "SMD2")
      (footprint "eagle-import:SMD1,27-2,54")
      (libsource (lib "eagle-import") (part "SMD2"))
    )
    (comp (ref "PAD508")
      (value "SMD2")
      (footprint "eagle-import:SMD1,27-2,54")
      (libsource (lib "eagle-import") (part "SMD2"))
    )
    (comp (ref "PAD509")
      (value "SMD2")
      (footprint "eagle-import:SMD1,27-2,54")
      (libsource (lib "eagle-import") (part "SMD2"))
    )
    (comp (ref "PAD510")
      (value "SMD2")
      (footprint "eagle-import:SMD1,27-2,54")
      (libsource (lib "eagle-import") (part "SMD2"))
    )
    (comp (ref "PAD511")
      (value "SMD2")
      (footprint "eagle-import:SMD1,27-2,54")
      (libsource (lib "eagle-import") (part "SMD2"))
    )
    (comp (ref "PAD512")
      (value "SMD2")
      (footprint "eagle-import:SMD1,27-2,54")
      (libsource (lib "eagle-import") (part "SMD2"))
    )
    (comp (ref "PAD513")
      (value "SMD2")
      (footprint "eagle-import:SMD1,27-2,54")
      (libsource (lib "eagle-import") (part "SMD2"))
    )
    (comp (ref "PAD514")
      (value "SMD2")
      (footprint "eagle-import:SMD1,27-2,54")
      (libsource (lib "eagle-import") (part "SMD2"))
    )
    (comp (ref "PAD515")
      (value "SMD2")
      (footprint "eagle-import:SMD1,27-2,54")
      (libsource (lib "eagle-import") (part "SMD2"))
    )
    (comp (ref "PAD516")
      (value "SMD2")
      (footprint "eagle-import:SMD1,27-2,54")
      (libsource (lib "eagle-import") (part "SMD2"))
    )
    (comp (ref "PAD517")
      (value "SMD2")
      (footprint "eagle-import:SMD1,27-2,54")
      (libsource (lib "eagle-import") (part "SMD2"))
    )
    (comp (ref "PAD518")
      (value "SMD2")
      (footprint "eagle-import:SMD1,27-2,54")
      (libsource (lib "eagle-import") (part "SMD2"))
    )
    (comp (ref "PAD519")
      (value "SMD2")
      (footprint "eagle-import:SMD1,27-2,54")
      (libsource (lib "eagle-import") (part "SMD2"))
    )
    (comp (ref "PAD520")
      (value "SMD2")
      (footprint "eagle-import:SMD1,27-2,54")
      (libsource (lib "eagle-import") (part "SMD2"))
    )
    (comp (ref "PAD521")
      (value "SMD2")
      (footprint "eagle-import:SMD1,27-2,54")
      (libsource (lib "eagle-import") (part "SMD2"))
    )
    (comp (ref "PAD522")
      (value "SMD2")
      (footprint "eagle-import:SMD1,27-2,54")
      (libsource (lib "eagle-import") (part "SMD2"))
    )
    (comp (ref "PAD523")
      (value "SMD2")
      (footprint "eagle-import:SMD1,27-2,54")
      (libsource (lib "eagle-import") (part "SMD2"))
    )
    (comp (ref "PAD524")
      (value "SMD2")
      (footprint "eagle-import:SMD1,27-2,54")
      (libsource (lib "eagle-import") (part "SMD2"))
    )
    (comp (ref "PAD525")
      (value "SMD2")
      (footprint "eagle-import:SMD1,27-2,54")
      (libsource (lib "eagle-import") (part "SMD2"))
    )
    (comp (ref "PAD526")
      (value "SMD2")
      (footprint "eagle-import:SMD1,27-2,54")
      (libsource (lib "eagle-import") (part "SMD2"))
    )
    (comp (ref "PAD527")
      (value "SMD2")
      (footprint "eagle-import:SMD1,27-2,54")
      (libsource (lib "eagle-import") (part "SMD2"))
    )
    (comp (ref "PAD528")
      (value "SMD2")
      (footprint "eagle-import:SMD1,27-2,54")
      (libsource (lib "eagle-import") (part "SMD2"))
    )
    (comp (ref "PAD529")
      (value "SMD2")
      (footprint "eagle-import:SMD1,27-2,54")
      (libsource (lib "eagle-import") (part "SMD2"))
    )
    (comp (ref "PAD530")
      (value "SMD2")
      (footprint "eagle-import:SMD1,27-2,54")
      (libsource (lib "eagle-import") (part "SMD2"))
    )
    (comp (ref "PAD531")
      (value "SMD2")
      (footprint "eagle-import:SMD1,27-2,54")
      (libsource (lib "eagle-import") (part "SMD2"))
    )
    (comp (ref "PAD532")
      (value "SMD2")
      (footprint "eagle-import:SMD1,27-2,54")
      (libsource (lib "eagle-import") (part "SMD2"))
    )
    (comp (ref "PAD533")
      (value "SMD2")
      (footprint "eagle-import:SMD1,27-2,54")
      (libsource (lib "eagle-import") (part "SMD2"))
    )
    (comp (ref "PAD534")
      (value "SMD2")
      (footprint "eagle-import:SMD1,27-2,54")
      (libsource (lib "eagle-import") (part "SMD2"))
    )
    (comp (ref "PAD535")
      (value "SMD2")
      (footprint "eagle-import:SMD1,27-2,54")
      (libsource (lib "eagle-import") (part "SMD2"))
    )
    (comp (ref "PAD536")
      (value "SMD2")
      (footprint "eagle-import:SMD1,27-2,54")
      (libsource (lib "eagle-import") (part "SMD2"))
    )
    (comp (ref "PAD537")
      (value "SMD2")
      (footprint "eagle-import:SMD1,27-2,54")
      (libsource (lib "eagle-import") (part "SMD2"))
    )
    (comp (ref "PAD538")
      (value "SMD2")
      (footprint "eagle-import:SMD1,27-2,54")
      (libsource (lib "eagle-import") (part "SMD2"))
    )
    (comp (ref "PAD539")
      (value "SMD2")
      (footprint "eagle-import:SMD1,27-2,54")
      (libsource (lib "eagle-import") (part "SMD2"))
    )
    (comp (ref "PAD540")
      (value "SMD2")
      (footprint "eagle-import:SMD1,27-2,54")
      (libsource (lib "eagle-import") (part "SMD2"))
    )
    (comp (ref "PAD541")
      (value "SMD2")
      (footprint "eagle-import:SMD1,27-2,54")
      (libsource (lib "eagle-import") (part "SMD2"))
    )
    (comp (ref "PAD542")
      (value "SMD2")
      (footprint "eagle-import:SMD1,27-2,54")
      (libsource (lib "eagle-import") (part "SMD2"))
    )
    (comp (ref "PAD543")
      (value "SMD2")
      (footprint "eagle-import:SMD1,27-2,54")
      (libsource (lib "eagle-import") (part "SMD2"))
    )
    (comp (ref "PAD544")
      (value "SMD2")
      (footprint "eagle-import:SMD1,27-2,54")
      (libsource (lib "eagle-import") (part "SMD2"))
    )
    (comp (ref "PAD545")
      (value "SMD2")
      (footprint "eagle-import:SMD1,27-2,54")
      (libsource (lib "eagle-import") (part "SMD2"))
    )
    (comp (ref "PAD546")
      (value "SMD2")
      (footprint "eagle-import:SMD1,27-2,54")
      (libsource (lib "eagle-import") (part "SMD2"))
    )
    (comp (ref "PAD547")
      (value "SMD2")
      (footprint "eagle-import:SMD1,27-2,54")
      (libsource (lib "eagle-import") (part "SMD2"))
    )
    (comp (ref "PAD548")
      (value "SMD2")
      (footprint "eagle-import:SMD1,27-2,54")
      (libsource (lib "eagle-import") (part "SMD2"))
    )
    (comp (ref "PAD549")
      (value "SMD2")
      (footprint "eagle-import:SMD1,27-2,54")
      (libsource (lib "eagle-import") (part "SMD2"))
    )
    (comp (ref "PAD550")
      (value "SMD2")
      (footprint "eagle-import:SMD1,27-2,54")
      (libsource (lib "eagle-import") (part "SMD2"))
    )
    (comp (ref "PAD551")
      (value "SMD2")
      (footprint "eagle-import:SMD1,27-2,54")
      (libsource (lib "eagle-import") (part "SMD2"))
    )
    (comp (ref "PAD552")
      (value "SMD2")
      (footprint "eagle-import:SMD1,27-2,54")
      (libsource (lib "eagle-import") (part "SMD2"))
    )
    (comp (ref "PAD553")
      (value "SMD2")
      (footprint "eagle-import:SMD1,27-2,54")
      (libsource (lib "eagle-import") (part "SMD2"))
    )
    (comp (ref "PAD554")
      (value "SMD2")
      (footprint "eagle-import:SMD1,27-2,54")
      (libsource (lib "eagle-import") (part "SMD2"))
    )
    (comp (ref "PAD555")
      (value "SMD2")
      (footprint "eagle-import:SMD1,27-2,54")
      (libsource (lib "eagle-import") (part "SMD2"))
    )
    (comp (ref "PAD556")
      (value "SMD2")
      (footprint "eagle-import:SMD1,27-2,54")
      (libsource (lib "eagle-import") (part "SMD2"))
    )
    (comp (ref "PAD557")
      (value "SMD2")
      (footprint "eagle-import:SMD1,27-2,54")
      (libsource (lib "eagle-import") (part "SMD2"))
    )
    (comp (ref "PAD558")
      (value "SMD2")
      (footprint "eagle-import:SMD1,27-2,54")
      (libsource (lib "eagle-import") (part "SMD2"))
    )
    (comp (ref "PAD559")
      (value "SMD2")
      (footprint "eagle-import:SMD1,27-2,54")
      (libsource (lib "eagle-import") (part "SMD2"))
    )
    (comp (ref "PAD560")
      (value "SMD2")
      (footprint "eagle-import:SMD1,27-2,54")
      (libsource (lib "eagle-import") (part "SMD2"))
    )
    (comp (ref "PAD561")
      (value "SMD2")
      (footprint "eagle-import:SMD1,27-2,54")
      (libsource (lib "eagle-import") (part "SMD2"))
    )
    (comp (ref "PAD562")
      (value "SMD2")
      (footprint "eagle-import:SMD1,27-2,54")
      (libsource (lib "eagle-import") (part "SMD2"))
    )
    (comp (ref "PAD563")
      (value "SMD2")
      (footprint "eagle-import:SMD1,27-2,54")
      (libsource (lib "eagle-import") (part "SMD2"))
    )
    (comp (ref "PAD564")
      (value "SMD2")
      (footprint "eagle-import:SMD1,27-2,54")
      (libsource (lib "eagle-import") (part "SMD2"))
    )
    (comp (ref "PAD565")
      (value "SMD2")
      (footprint "eagle-import:SMD1,27-2,54")
      (libsource (lib "eagle-import") (part "SMD2"))
    )
    (comp (ref "PAD566")
      (value "SMD2")
      (footprint "eagle-import:SMD1,27-2,54")
      (libsource (lib "eagle-import") (part "SMD2"))
    )
    (comp (ref "PAD567")
      (value "SMD2")
      (footprint "eagle-import:SMD1,27-2,54")
      (libsource (lib "eagle-import") (part "SMD2"))
    )
    (comp (ref "PAD568")
      (value "SMD2")
      (footprint "eagle-import:SMD1,27-2,54")
      (libsource (lib "eagle-import") (part "SMD2"))
    )
    (comp (ref "PAD569")
      (value "SMD2")
      (footprint "eagle-import:SMD1,27-2,54")
      (libsource (lib "eagle-import") (part "SMD2"))
    )
    (comp (ref "PAD570")
      (value "SMD2")
      (footprint "eagle-import:SMD1,27-2,54")
      (libsource (lib "eagle-import") (part "SMD2"))
    )
    (comp (ref "PAD571")
      (value "SMD2")
      (footprint "eagle-import:SMD1,27-2,54")
      (libsource (lib "eagle-import") (part "SMD2"))
    )
    (comp (ref "PAD574")
      (value "SMD2")
      (footprint "eagle-import:SMD1,27-2,54")
      (libsource (lib "eagle-import") (part "SMD2"))
    )
    (comp (ref "PAD575")
      (value "SMD2")
      (footprint "eagle-import:SMD1,27-2,54")
      (libsource (lib "eagle-import") (part "SMD2"))
    )
    (comp (ref "PAD576")
      (value "SMD2")
      (footprint "eagle-import:SMD1,27-2,54")
      (libsource (lib "eagle-import") (part "SMD2"))
    )
    (comp (ref "PAD577")
      (value "SMD2")
      (footprint "eagle-import:SMD1,27-2,54")
      (libsource (lib "eagle-import") (part "SMD2"))
    )
    (comp (ref "PAD578")
      (value "SMD2")
      (footprint "eagle-import:SMD1,27-2,54")
      (libsource (lib "eagle-import") (part "SMD2"))
    )
    (comp (ref "PAD579")
      (value "SMD2")
      (footprint "eagle-import:SMD1,27-2,54")
      (libsource (lib "eagle-import") (part "SMD2"))
    )
    (comp (ref "PAD582")
      (value "SMD2")
      (footprint "eagle-import:SMD1,27-2,54")
      (libsource (lib "eagle-import") (part "SMD2"))
    )
    (comp (ref "PAD583")
      (value "SMD2")
      (footprint "eagle-import:SMD1,27-2,54")
      (libsource (lib "eagle-import") (part "SMD2"))
    )
    (comp (ref "PAD584")
      (value "SMD2")
      (footprint "eagle-import:SMD1,27-2,54")
      (libsource (lib "eagle-import") (part "SMD2"))
    )
    (comp (ref "PAD585")
      (value "SMD2")
      (footprint "eagle-import:SMD1,27-2,54")
      (libsource (lib "eagle-import") (part "SMD2"))
    )
    (comp (ref "PAD586")
      (value "SMD2")
      (footprint "eagle-import:SMD1,27-2,54")
      (libsource (lib "eagle-import") (part "SMD2"))
    )
    (comp (ref "PAD587")
      (value "SMD2")
      (footprint "eagle-import:SMD1,27-2,54")
      (libsource (lib "eagle-import") (part "SMD2"))
    )
    (comp (ref "PAD590")
      (value "SMD2")
      (footprint "eagle-import:SMD1,27-2,54")
      (libsource (lib "eagle-import") (part "SMD2"))
    )
    (comp (ref "PAD591")
      (value "SMD2")
      (footprint "eagle-import:SMD1,27-2,54")
      (libsource (lib "eagle-import") (part "SMD2"))
    )
    (comp (ref "PAD592")
      (value "SMD2")
      (footprint "eagle-import:SMD1,27-2,54")
      (libsource (lib "eagle-import") (part "SMD2"))
    )
    (comp (ref "PAD593")
      (value "SMD2")
      (footprint "eagle-import:SMD1,27-2,54")
      (libsource (lib "eagle-import") (part "SMD2"))
    )
    (comp (ref "PAD594")
      (value "SMD2")
      (footprint "eagle-import:SMD1,27-2,54")
      (libsource (lib "eagle-import") (part "SMD2"))
    )
    (comp (ref "PAD595")
      (value "SMD2")
      (footprint "eagle-import:SMD1,27-2,54")
      (libsource (lib "eagle-import") (part "SMD2"))
    )
    (comp (ref "PAD597")
      (value "SMD2")
      (footprint "eagle-import:SMD1,27-2,54")
      (libsource (lib "eagle-import") (part "SMD2"))
    )
    (comp (ref "PAD598")
      (value "SMD2")
      (footprint "eagle-import:SMD1,27-2,54")
      (libsource (lib "eagle-import") (part "SMD2"))
    )
    (comp (ref "PAD599")
      (value "SMD2")
      (footprint "eagle-import:SMD1,27-2,54")
      (libsource (lib "eagle-import") (part "SMD2"))
    )
    (comp (ref "PAD600")
      (value "SMD2")
      (footprint "eagle-import:SMD1,27-2,54")
      (libsource (lib "eagle-import") (part "SMD2"))
    )
    (comp (ref "PAD601")
      (value "SMD2")
      (footprint "eagle-import:SMD1,27-2,54")
      (libsource (lib "eagle-import") (part "SMD2"))
    )
    (comp (ref "PAD602")
      (value "SMD2")
      (footprint "eagle-import:SMD1,27-2,54")
      (libsource (lib "eagle-import") (part "SMD2"))
    )
    (comp (ref "PAD603")
      (value "SMD2")
      (footprint "eagle-import:SMD1,27-2,54")
      (libsource (lib "eagle-import") (part "SMD2"))
    )
    (comp (ref "PAD605")
      (value "SMD2")
      (footprint "eagle-import:SMD1,27-2,54")
      (libsource (lib "eagle-import") (part "SMD2"))
    )
    (comp (ref "PAD606")
      (value "SMD2")
      (footprint "eagle-import:SMD1,27-2,54")
      (libsource (lib "eagle-import") (part "SMD2"))
    )
    (comp (ref "PAD607")
      (value "SMD2")
      (footprint "eagle-import:SMD1,27-2,54")
      (libsource (lib "eagle-import") (part "SMD2"))
    )
    (comp (ref "PAD608")
      (value "SMD2")
      (footprint "eagle-import:SMD1,27-2,54")
      (libsource (lib "eagle-import") (part "SMD2"))
    )
    (comp (ref "PAD609")
      (value "SMD2")
      (footprint "eagle-import:SMD1,27-2,54")
      (libsource (lib "eagle-import") (part "SMD2"))
    )
    (comp (ref "PAD610")
      (value "SMD2")
      (footprint "eagle-import:SMD1,27-2,54")
      (libsource (lib "eagle-import") (part "SMD2"))
    )
    (comp (ref "PAD611")
      (value "SMD2")
      (footprint "eagle-import:SMD1,27-2,54")
      (libsource (lib "eagle-import") (part "SMD2"))
    )
    (comp (ref "PAD613")
      (value "SMD2")
      (footprint "eagle-import:SMD1,27-2,54")
      (libsource (lib "eagle-import") (part "SMD2"))
    )
    (comp (ref "PAD614")
      (value "SMD2")
      (footprint "eagle-import:SMD1,27-2,54")
      (libsource (lib "eagle-import") (part "SMD2"))
    )
    (comp (ref "PAD615")
      (value "SMD2")
      (footprint "eagle-import:SMD1,27-2,54")
      (libsource (lib "eagle-import") (part "SMD2"))
    )
    (comp (ref "PAD616")
      (value "SMD2")
      (footprint "eagle-import:SMD1,27-2,54")
      (libsource (lib "eagle-import") (part "SMD2"))
    )
    (comp (ref "PAD617")
      (value "SMD2")
      (footprint "eagle-import:SMD1,27-2,54")
      (libsource (lib "eagle-import") (part "SMD2"))
    )
    (comp (ref "PAD618")
      (value "SMD2")
      (footprint "eagle-import:SMD1,27-2,54")
      (libsource (lib "eagle-import") (part "SMD2"))
    )
    (comp (ref "PAD619")
      (value "SMD2")
      (footprint "eagle-import:SMD1,27-2,54")
      (libsource (lib "eagle-import") (part "SMD2"))
    )
    (comp (ref "PAD620")
      (value "SMD2")
      (footprint "eagle-import:SMD1,27-2,54")
      (libsource (lib "eagle-import") (part "SMD2"))
    )
    (comp (ref "PAD621")
      (value "SMD2")
      (footprint "eagle-import:SMD1,27-2,54")
      (libsource (lib "eagle-import") (part "SMD2"))
    )
    (comp (ref "PAD622")
      (value "SMD2")
      (footprint "eagle-import:SMD1,27-2,54")
      (libsource (lib "eagle-import") (part "SMD2"))
    )
    (comp (ref "PAD623")
      (value "SMD2")
      (footprint "eagle-import:SMD1,27-2,54")
      (libsource (lib "eagle-import") (part "SMD2"))
    )
    (comp (ref "PAD624")
      (value "SMD2")
      (footprint "eagle-import:SMD1,27-2,54")
      (libsource (lib "eagle-import") (part "SMD2"))
    )
    (comp (ref "PAD625")
      (value "SMD2")
      (footprint "eagle-import:SMD1,27-2,54")
      (libsource (lib "eagle-import") (part "SMD2"))
    )
    (comp (ref "PAD626")
      (value "SMD2")
      (footprint "eagle-import:SMD1,27-2,54")
      (libsource (lib "eagle-import") (part "SMD2"))
    )
    (comp (ref "PAD627")
      (value "SMD2")
      (footprint "eagle-import:SMD1,27-2,54")
      (libsource (lib "eagle-import") (part "SMD2"))
    )
    (comp (ref "PAD628")
      (value "SMD2")
      (footprint "eagle-import:SMD1,27-2,54")
      (libsource (lib "eagle-import") (part "SMD2"))
    )
    (comp (ref "PAD629")
      (value "SMD2")
      (footprint "eagle-import:SMD1,27-2,54")
      (libsource (lib "eagle-import") (part "SMD2"))
    )
    (comp (ref "PAD630")
      (value "SMD2")
      (footprint "eagle-import:SMD1,27-2,54")
      (libsource (lib "eagle-import") (part "SMD2"))
    )
    (comp (ref "PAD631")
      (value "SMD2")
      (footprint "eagle-import:SMD1,27-2,54")
      (libsource (lib "eagle-import") (part "SMD2"))
    )
    (comp (ref "PAD632")
      (value "SMD2")
      (footprint "eagle-import:SMD1,27-2,54")
      (libsource (lib "eagle-import") (part "SMD2"))
    )
    (comp (ref "PAD633")
      (value "SMD2")
      (footprint "eagle-import:SMD1,27-2,54")
      (libsource (lib "eagle-import") (part "SMD2"))
    )
    (comp (ref "PAD634")
      (value "SMD2")
      (footprint "eagle-import:SMD1,27-2,54")
      (libsource (lib "eagle-import") (part "SMD2"))
    )
    (comp (ref "PAD635")
      (value "SMD2")
      (footprint "eagle-import:SMD1,27-2,54")
      (libsource (lib "eagle-import") (part "SMD2"))
    )
    (comp (ref "PAD636")
      (value "SMD2")
      (footprint "eagle-import:SMD1,27-2,54")
      (libsource (lib "eagle-import") (part "SMD2"))
    )
    (comp (ref "PAD637")
      (value "SMD2")
      (footprint "eagle-import:SMD1,27-2,54")
      (libsource (lib "eagle-import") (part "SMD2"))
    )
    (comp (ref "QG1")
      (value "SM77HL")
      (footprint "eagle-import:SM77HL")
      (libsource (lib "eagle-import") (part "SM77HL"))
    )
    (comp (ref "R1")
      (value "R-EU_R2012W")
      (footprint "eagle-import:R2012W")
      (libsource (lib "eagle-import") (part "R-EU_R2012W"))
    )
    (comp (ref "R2")
      (value "R-EU_R2012")
      (footprint "eagle-import:R2012")
      (libsource (lib "eagle-import") (part "R-EU_R2012"))
    )
    (comp (ref "R3")
      (value "R-EU_R2012")
      (footprint "eagle-import:R2012")
      (libsource (lib "eagle-import") (part "R-EU_R2012"))
    )
    (comp (ref "R4")
      (value "R-EU_R2012")
      (footprint "eagle-import:R2012")
      (libsource (lib "eagle-import") (part "R-EU_R2012"))
    )
    (comp (ref "R5")
      (value "R-EU_R2012")
      (footprint "eagle-import:R2012")
      (libsource (lib "eagle-import") (part "R-EU_R2012"))
    )
    (comp (ref "R6")
      (value "R-EU_R2012")
      (footprint "eagle-import:R2012")
      (libsource (lib "eagle-import") (part "R-EU_R2012"))
    )
    (comp (ref "R7")
      (value "R-EU_R2012")
      (footprint "eagle-import:R2012")
      (libsource (lib "eagle-import") (part "R-EU_R2012"))
    )
    (comp (ref "R8")
      (value "R-EU_R2012")
      (footprint "eagle-import:R2012")
      (libsource (lib "eagle-import") (part "R-EU_R2012"))
    )
    (comp (ref "R9")
      (value "R-EU_R2012")
      (footprint "eagle-import:R2012")
      (libsource (lib "eagle-import") (part "R-EU_R2012"))
    )
    (comp (ref "SJ1")
      (value "SJ2W")
      (footprint "eagle-import:SJ_2")
      (libsource (lib "eagle-import") (part "SJ2W"))
    )
  )
  (nets
    (net (code "1") (name "/3") (class "Default")
      (node (ref "IC1") (pin "3") (pinfunction "P$3_3") (pintype "bidirectional"))
      (node (ref "JP1") (pin "3") (pinfunction "3_3") (pintype "passive"))
    )
    (net (code "2") (name "/4") (class "Default")
      (node (ref "IC1") (pin "4") (pinfunction "P$4_4") (pintype "bidirectional"))
      (node (ref "JP1") (pin "4") (pinfunction "4_4") (pintype "passive"))
    )
    (net (code "3") (name "/5") (class "Default")
      (node (ref "IC1") (pin "5") (pinfunction "P$5_5") (pintype "bidirectional"))
      (node (ref "JP1") (pin "5") (pinfunction "5_5") (pintype "passive"))
    )
    (net (code "4") (name "/6") (class "Default")
      (node (ref "IC1") (pin "6") (pinfunction "P$6_6") (pintype "bidirectional"))
      (node (ref "JP1") (pin "6") (pinfunction "6_6") (pintype "passive"))
    )
    (net (code "5") (name "/7") (class "Default")
      (node (ref "IC1") (pin "7") (pinfunction "P$7_7") (pintype "bidirectional"))
      (node (ref "JP1") (pin "7") (pinfunction "7_7") (pintype "passive"))
    )
    (net (code "6") (name "/8") (class "Default")
      (node (ref "IC1") (pin "8") (pinfunction "P$8_8") (pintype "bidirectional"))
      (node (ref "JP1") (pin "8") (pinfunction "8_8") (pintype "passive"))
    )
    (net (code "7") (name "/9") (class "Default")
      (node (ref "IC1") (pin "9") (pinfunction "P$9_9") (pintype "bidirectional"))
      (node (ref "JP1") (pin "9") (pinfunction "9_9") (pintype "passive"))
    )
    (net (code "8") (name "/10") (class "Default")
      (node (ref "IC1") (pin "10") (pinfunction "P$10_10") (pintype "bidirectional"))
      (node (ref "JP1") (pin "10") (pinfunction "10_10") (pintype "passive"))
    )
    (net (code "9") (name "/13") (class "Default")
      (node (ref "IC1") (pin "13") (pinfunction "P$13_13") (pintype "bidirectional"))
      (node (ref "JP1") (pin "13") (pinfunction "13_13") (pintype "passive"))
    )
    (net (code "10") (name "/14") (class "Default")
      (node (ref "IC1") (pin "14") (pinfunction "P$14_14") (pintype "bidirectional"))
      (node (ref "JP1") (pin "14") (pinfunction "14_14") (pintype "passive"))
    )
    (net (code "11") (name "/19") (class "Default")
      (node (ref "IC1") (pin "19") (pinfunction "P$19_19") (pintype "bidirectional"))
      (node (ref "JP1") (pin "19") (pinfunction "19_19") (pintype "passive"))
    )
    (net (code "12") (name "/21") (class "Default")
      (node (ref "IC1") (pin "21") (pinfunction "P$21_21") (pintype "bidirectional"))
      (node (ref "JP1") (pin "21") (pinfunction "21_21") (pintype "passive"))
    )
    (net (code "13") (name "/23") (class "Default")
      (node (ref "IC1") (pin "23") (pinfunction "P$23_23") (pintype "bidirectional"))
      (node (ref "JP1") (pin "23") (pinfunction "23_23") (pintype "passive"))
    )
    (net (code "14") (name "/24") (class "Default")
      (node (ref "IC1") (pin "24") (pinfunction "P$24_24") (pintype "bidirectional"))
      (node (ref "JP1") (pin "24") (pinfunction "24_24") (pintype "passive"))
    )
    (net (code "15") (name "/25") (class "Default")
      (node (ref "IC1") (pin "25") (pinfunction "P$25_CLK0N_25") (pintype "bidirectional"))
      (node (ref "JP1") (pin "25") (pinfunction "25_25") (pintype "passive"))
      (node (ref "R1") (pin "2") (pinfunction "2_2") (pintype "passive"))
    )
    (net (code "16") (name "/26") (class "Default")
      (node (ref "IC1") (pin "26") (pinfunction "P$26_CLK0P_26") (pintype "bidirectional"))
      (node (ref "JP1") (pin "26") (pinfunction "26_26") (pintype "passive"))
    )
    (net (code "17") (name "/27") (class "Default")
      (node (ref "IC1") (pin "27") (pinfunction "P$27_CLK1N_27") (pintype "bidirectional"))
      (node (ref "JP1") (pin "27") (pinfunction "27_27") (pintype "passive"))
    )
    (net (code "18") (name "/28") (class "Default")
      (node (ref "IC1") (pin "28") (pinfunction "P$28_CLK1P_28") (pintype "bidirectional"))
      (node (ref "JP1") (pin "28") (pinfunction "28_28") (pintype "passive"))
    )
    (net (code "19") (name "/31") (class "Default")
      (node (ref "IC1") (pin "31") (pinfunction "P$31_31") (pintype "bidirectional"))
      (node (ref "JP1") (pin "31") (pinfunction "31_31") (pintype "passive"))
    )
    (net (code "20") (name "/32") (class "Default")
      (node (ref "IC1") (pin "32") (pinfunction "P$32_32") (pintype "bidirectional"))
      (node (ref "JP1") (pin "32") (pinfunction "32_32") (pintype "passive"))
    )
    (net (code "21") (name "/33") (class "Default")
      (node (ref "IC1") (pin "33") (pinfunction "P$33_33") (pintype "bidirectional"))
      (node (ref "JP1") (pin "33") (pinfunction "33_33") (pintype "passive"))
    )
    (net (code "22") (name "/39") (class "Default")
      (node (ref "IC1") (pin "39") (pinfunction "P$39_39") (pintype "bidirectional"))
      (node (ref "JP2") (pin "3") (pinfunction "3_3") (pintype "passive"))
    )
    (net (code "23") (name "/40") (class "Default")
      (node (ref "IC1") (pin "40") (pinfunction "P$40_40") (pintype "bidirectional"))
      (node (ref "JP2") (pin "4") (pinfunction "4_4") (pintype "passive"))
    )
    (net (code "24") (name "/41") (class "Default")
      (node (ref "IC1") (pin "41") (pinfunction "P$41_41") (pintype "bidirectional"))
      (node (ref "JP2") (pin "5") (pinfunction "5_5") (pintype "passive"))
    )
    (net (code "25") (name "/42") (class "Default")
      (node (ref "IC1") (pin "42") (pinfunction "P$42_42") (pintype "bidirectional"))
      (node (ref "JP2") (pin "6") (pinfunction "6_6") (pintype "passive"))
    )
    (net (code "26") (name "/44") (class "Default")
      (node (ref "IC1") (pin "44") (pinfunction "P$44_44") (pintype "bidirectional"))
      (node (ref "JP2") (pin "8") (pinfunction "8_8") (pintype "passive"))
    )
    (net (code "27") (name "/46") (class "Default")
      (node (ref "IC1") (pin "46") (pinfunction "P$46_46") (pintype "bidirectional"))
      (node (ref "JP2") (pin "10") (pinfunction "10_10") (pintype "passive"))
    )
    (net (code "28") (name "/47") (class "Default")
      (node (ref "IC1") (pin "47") (pinfunction "P$47_47") (pintype "bidirectional"))
      (node (ref "JP2") (pin "11") (pinfunction "11_11") (pintype "passive"))
    )
    (net (code "29") (name "/48") (class "Default")
      (node (ref "IC1") (pin "48") (pinfunction "P$48_48") (pintype "bidirectional"))
      (node (ref "JP2") (pin "12") (pinfunction "12_12") (pintype "passive"))
    )
    (net (code "30") (name "/49") (class "Default")
      (node (ref "IC1") (pin "49") (pinfunction "P$49_49") (pintype "bidirectional"))
      (node (ref "JP2") (pin "13") (pinfunction "13_13") (pintype "passive"))
    )
    (net (code "31") (name "/50") (class "Default")
      (node (ref "IC1") (pin "50") (pinfunction "P$50_50") (pintype "bidirectional"))
      (node (ref "JP2") (pin "14") (pinfunction "14_14") (pintype "passive"))
    )
    (net (code "32") (name "/51") (class "Default")
      (node (ref "IC1") (pin "51") (pinfunction "P$51_51") (pintype "bidirectional"))
      (node (ref "JP2") (pin "15") (pinfunction "15_15") (pintype "passive"))
    )
    (net (code "33") (name "/52") (class "Default")
      (node (ref "IC1") (pin "52") (pinfunction "P$52_52") (pintype "bidirectional"))
      (node (ref "JP2") (pin "16") (pinfunction "16_16") (pintype "passive"))
    )
    (net (code "34") (name "/53") (class "Default")
      (node (ref "IC1") (pin "53") (pinfunction "P$53_53") (pintype "bidirectional"))
      (node (ref "JP2") (pin "17") (pinfunction "17_17") (pintype "passive"))
    )
    (net (code "35") (name "/54") (class "Default")
      (node (ref "IC1") (pin "54") (pinfunction "P$54_54") (pintype "bidirectional"))
      (node (ref "JP2") (pin "18") (pinfunction "18_18") (pintype "passive"))
    )
    (net (code "36") (name "/55") (class "Default")
      (node (ref "IC1") (pin "55") (pinfunction "P$55_55") (pintype "bidirectional"))
      (node (ref "JP2") (pin "19") (pinfunction "19_19") (pintype "passive"))
    )
    (net (code "37") (name "/59") (class "Default")
      (node (ref "IC1") (pin "59") (pinfunction "P$59_59") (pintype "bidirectional"))
      (node (ref "JP2") (pin "23") (pinfunction "23_23") (pintype "passive"))
    )
    (net (code "38") (name "/60") (class "Default")
      (node (ref "IC1") (pin "60") (pinfunction "P$60_60") (pintype "bidirectional"))
      (node (ref "JP2") (pin "24") (pinfunction "24_24") (pintype "passive"))
    )
    (net (code "39") (name "/61") (class "Default")
      (node (ref "IC1") (pin "61") (pinfunction "P$61_61") (pintype "bidirectional"))
      (node (ref "JP2") (pin "25") (pinfunction "25_25") (pintype "passive"))
    )
    (net (code "40") (name "/62") (class "Default")
      (node (ref "IC1") (pin "62") (pinfunction "P$62_62") (pintype "bidirectional"))
      (node (ref "JP2") (pin "26") (pinfunction "26_26") (pintype "passive"))
    )
    (net (code "41") (name "/63") (class "Default")
      (node (ref "IC1") (pin "63") (pinfunction "P$63_63") (pintype "bidirectional"))
      (node (ref "JP2") (pin "27") (pinfunction "27_27") (pintype "passive"))
    )
    (net (code "42") (name "/65") (class "Default")
      (node (ref "IC1") (pin "65") (pinfunction "P$65_65") (pintype "bidirectional"))
      (node (ref "JP2") (pin "29") (pinfunction "29_29") (pintype "passive"))
    )
    (net (code "43") (name "/67") (class "Default")
      (node (ref "IC1") (pin "67") (pinfunction "P$67_67") (pintype "bidirectional"))
      (node (ref "JP2") (pin "31") (pinfunction "31_31") (pintype "passive"))
    )
    (net (code "44") (name "/68") (class "Default")
      (node (ref "IC1") (pin "68") (pinfunction "P$68_68") (pintype "bidirectional"))
      (node (ref "JP2") (pin "32") (pinfunction "32_32") (pintype "passive"))
    )
    (net (code "45") (name "/69") (class "Default")
      (node (ref "IC1") (pin "69") (pinfunction "P$69_69") (pintype "bidirectional"))
      (node (ref "JP2") (pin "33") (pinfunction "33_33") (pintype "passive"))
    )
    (net (code "46") (name "/70") (class "Default")
      (node (ref "IC1") (pin "70") (pinfunction "P$70_70") (pintype "bidirectional"))
      (node (ref "JP2") (pin "34") (pinfunction "34_34") (pintype "passive"))
    )
    (net (code "47") (name "/74") (class "Default")
      (node (ref "IC1") (pin "74") (pinfunction "P$74_74") (pintype "bidirectional"))
      (node (ref "JP3") (pin "2") (pinfunction "2_2") (pintype "passive"))
    )
    (net (code "48") (name "/75") (class "Default")
      (node (ref "IC1") (pin "75") (pinfunction "P$75_75") (pintype "bidirectional"))
      (node (ref "JP3") (pin "3") (pinfunction "3_3") (pintype "passive"))
    )
    (net (code "49") (name "/76") (class "Default")
      (node (ref "IC1") (pin "76") (pinfunction "P$76_76") (pintype "bidirectional"))
      (node (ref "JP3") (pin "4") (pinfunction "4_4") (pintype "passive"))
    )
    (net (code "50") (name "/77") (class "Default")
      (node (ref "IC1") (pin "77") (pinfunction "P$77_77") (pintype "bidirectional"))
      (node (ref "JP3") (pin "5") (pinfunction "5_5") (pintype "passive"))
    )
    (net (code "51") (name "/78") (class "Default")
      (node (ref "IC1") (pin "78") (pinfunction "P$78_78") (pintype "bidirectional"))
      (node (ref "JP3") (pin "6") (pinfunction "6_6") (pintype "passive"))
    )
    (net (code "52") (name "/79") (class "Default")
      (node (ref "IC1") (pin "79") (pinfunction "P$79_79") (pintype "bidirectional"))
      (node (ref "JP3") (pin "7") (pinfunction "7_7") (pintype "passive"))
    )
    (net (code "53") (name "/80") (class "Default")
      (node (ref "IC1") (pin "80") (pinfunction "P$80_80") (pintype "bidirectional"))
      (node (ref "JP3") (pin "8") (pinfunction "8_8") (pintype "passive"))
    )
    (net (code "54") (name "/81") (class "Default")
      (node (ref "IC1") (pin "81") (pinfunction "P$81_81") (pintype "bidirectional"))
      (node (ref "JP3") (pin "9") (pinfunction "9_9") (pintype "passive"))
    )
    (net (code "55") (name "/84") (class "Default")
      (node (ref "IC1") (pin "84") (pinfunction "P$84_84") (pintype "bidirectional"))
      (node (ref "JP3") (pin "12") (pinfunction "12_12") (pintype "passive"))
    )
    (net (code "56") (name "/85") (class "Default")
      (node (ref "IC1") (pin "85") (pinfunction "P$85_85") (pintype "bidirectional"))
      (node (ref "JP3") (pin "13") (pinfunction "13_13") (pintype "passive"))
    )
    (net (code "57") (name "/86") (class "Default")
      (node (ref "IC1") (pin "86") (pinfunction "P$86_86") (pintype "bidirectional"))
      (node (ref "JP3") (pin "14") (pinfunction "14_14") (pintype "passive"))
    )
    (net (code "58") (name "/87") (class "Default")
      (node (ref "IC1") (pin "87") (pinfunction "P$87_87") (pintype "bidirectional"))
      (node (ref "JP3") (pin "15") (pinfunction "15_15") (pintype "passive"))
    )
    (net (code "59") (name "/88") (class "Default")
      (node (ref "IC1") (pin "88") (pinfunction "P$88_88") (pintype "bidirectional"))
      (node (ref "JP3") (pin "16") (pinfunction "16_16") (pintype "passive"))
    )
    (net (code "60") (name "/89") (class "Default")
      (node (ref "IC1") (pin "89") (pinfunction "P$89_89") (pintype "bidirectional"))
      (node (ref "JP3") (pin "17") (pinfunction "17_17") (pintype "passive"))
    )
    (net (code "61") (name "/90") (class "Default")
      (node (ref "IC1") (pin "90") (pinfunction "P$90_90") (pintype "bidirectional"))
      (node (ref "JP3") (pin "18") (pinfunction "18_18") (pintype "passive"))
    )
    (net (code "62") (name "/91") (class "Default")
      (node (ref "IC1") (pin "91") (pinfunction "P$91_91") (pintype "bidirectional"))
      (node (ref "JP3") (pin "19") (pinfunction "19_19") (pintype "passive"))
    )
    (net (code "63") (name "/92") (class "Default")
      (node (ref "IC1") (pin "92") (pinfunction "P$92_92") (pintype "bidirectional"))
      (node (ref "JP3") (pin "20") (pinfunction "20_20") (pintype "passive"))
    )
    (net (code "64") (name "/94") (class "Default")
      (node (ref "IC1") (pin "94") (pinfunction "P$94_94") (pintype "bidirectional"))
      (node (ref "JP3") (pin "22") (pinfunction "22_22") (pintype "passive"))
    )
    (net (code "65") (name "/95") (class "Default")
      (node (ref "IC1") (pin "95") (pinfunction "P$95_95") (pintype "bidirectional"))
      (node (ref "JP3") (pin "23") (pinfunction "23_23") (pintype "passive"))
    )
    (net (code "66") (name "/97") (class "Default")
      (node (ref "IC1") (pin "97") (pinfunction "P$97_97") (pintype "bidirectional"))
      (node (ref "JP3") (pin "25") (pinfunction "25_25") (pintype "passive"))
    )
    (net (code "67") (name "/98") (class "Default")
      (node (ref "IC1") (pin "98") (pinfunction "P$98_98") (pintype "bidirectional"))
      (node (ref "JP3") (pin "26") (pinfunction "26_26") (pintype "passive"))
    )
    (net (code "68") (name "/99") (class "Default")
      (node (ref "IC1") (pin "99") (pinfunction "P$99_99") (pintype "bidirectional"))
      (node (ref "JP3") (pin "27") (pinfunction "27_27") (pintype "passive"))
    )
    (net (code "69") (name "/100") (class "Default")
      (node (ref "IC1") (pin "100") (pinfunction "P$100_100") (pintype "bidirectional"))
      (node (ref "JP3") (pin "28") (pinfunction "28_28") (pintype "passive"))
    )
    (net (code "70") (name "/101") (class "Default")
      (node (ref "IC1") (pin "101") (pinfunction "P$101_101") (pintype "bidirectional"))
      (node (ref "JP3") (pin "29") (pinfunction "29_29") (pintype "passive"))
    )
    (net (code "71") (name "/103") (class "Default")
      (node (ref "IC1") (pin "103") (pinfunction "P$103_103") (pintype "bidirectional"))
      (node (ref "JP3") (pin "31") (pinfunction "31_31") (pintype "passive"))
    )
    (net (code "72") (name "/105") (class "Default")
      (node (ref "IC1") (pin "105") (pinfunction "P$105_105") (pintype "bidirectional"))
      (node (ref "JP3") (pin "33") (pinfunction "33_33") (pintype "passive"))
    )
    (net (code "73") (name "/106") (class "Default")
      (node (ref "IC1") (pin "106") (pinfunction "P$106_106") (pintype "bidirectional"))
      (node (ref "JP3") (pin "34") (pinfunction "34_34") (pintype "passive"))
    )
    (net (code "74") (name "/112") (class "Default")
      (node (ref "IC1") (pin "112") (pinfunction "P$112_112") (pintype "bidirectional"))
      (node (ref "JP4") (pin "4") (pinfunction "4_4") (pintype "passive"))
    )
    (net (code "75") (name "/113") (class "Default")
      (node (ref "IC1") (pin "113") (pinfunction "P$113_113") (pintype "bidirectional"))
      (node (ref "JP4") (pin "5") (pinfunction "5_5") (pintype "passive"))
    )
    (net (code "76") (name "/114") (class "Default")
      (node (ref "IC1") (pin "114") (pinfunction "P$114_114") (pintype "bidirectional"))
      (node (ref "JP4") (pin "6") (pinfunction "6_6") (pintype "passive"))
    )
    (net (code "77") (name "/115") (class "Default")
      (node (ref "IC1") (pin "115") (pinfunction "P$115_115") (pintype "bidirectional"))
      (node (ref "JP4") (pin "7") (pinfunction "7_7") (pintype "passive"))
    )
    (net (code "78") (name "/116") (class "Default")
      (node (ref "IC1") (pin "116") (pinfunction "P$116_116") (pintype "bidirectional"))
      (node (ref "JP4") (pin "8") (pinfunction "8_8") (pintype "passive"))
    )
    (net (code "79") (name "/117") (class "Default")
      (node (ref "IC1") (pin "117") (pinfunction "P$117_117") (pintype "bidirectional"))
      (node (ref "JP4") (pin "9") (pinfunction "9_9") (pintype "passive"))
    )
    (net (code "80") (name "/120") (class "Default")
      (node (ref "IC1") (pin "120") (pinfunction "P$120_120") (pintype "bidirectional"))
      (node (ref "JP4") (pin "12") (pinfunction "12_12") (pintype "passive"))
      (node (ref "SJ1") (pin "2") (pinfunction "2_2") (pintype "passive"))
    )
    (net (code "81") (name "/122") (class "Default")
      (node (ref "IC1") (pin "122") (pinfunction "P$122_122") (pintype "bidirectional"))
      (node (ref "JP4") (pin "14") (pinfunction "14_14") (pintype "passive"))
      (node (ref "R7") (pin "2") (pinfunction "2_2") (pintype "passive"))
    )
    (net (code "82") (name "/123") (class "Default")
      (node (ref "IC1") (pin "123") (pinfunction "P$123_123") (pintype "bidirectional"))
      (node (ref "JP4") (pin "15") (pinfunction "15_15") (pintype "passive"))
    )
    (net (code "83") (name "/124") (class "Default")
      (node (ref "IC1") (pin "124") (pinfunction "P$124_124") (pintype "bidirectional"))
      (node (ref "JP4") (pin "16") (pinfunction "16_16") (pintype "passive"))
    )
    (net (code "84") (name "/125") (class "Default")
      (node (ref "IC1") (pin "125") (pinfunction "P$125_125") (pintype "bidirectional"))
      (node (ref "JP4") (pin "17") (pinfunction "17_17") (pintype "passive"))
    )
    (net (code "85") (name "/126") (class "Default")
      (node (ref "IC1") (pin "126") (pinfunction "P$126_126") (pintype "bidirectional"))
      (node (ref "JP4") (pin "18") (pinfunction "18_18") (pintype "passive"))
    )
    (net (code "86") (name "/127") (class "Default")
      (node (ref "IC1") (pin "127") (pinfunction "P$127_127") (pintype "bidirectional"))
      (node (ref "JP4") (pin "19") (pinfunction "19_19") (pintype "passive"))
    )
    (net (code "87") (name "/128") (class "Default")
      (node (ref "IC1") (pin "128") (pinfunction "P$128_128") (pintype "bidirectional"))
      (node (ref "JP4") (pin "20") (pinfunction "20_20") (pintype "passive"))
    )
    (net (code "88") (name "/129") (class "Default")
      (node (ref "IC1") (pin "129") (pinfunction "P$129_129") (pintype "bidirectional"))
      (node (ref "JP4") (pin "21") (pinfunction "21_21") (pintype "passive"))
    )
    (net (code "89") (name "/130") (class "Default")
      (node (ref "IC1") (pin "130") (pinfunction "P$130_130") (pintype "bidirectional"))
      (node (ref "JP4") (pin "22") (pinfunction "22_22") (pintype "passive"))
    )
    (net (code "90") (name "/131") (class "Default")
      (node (ref "IC1") (pin "131") (pinfunction "P$131_131") (pintype "bidirectional"))
      (node (ref "JP4") (pin "23") (pinfunction "23_23") (pintype "passive"))
      (node (ref "R6") (pin "2") (pinfunction "2_2") (pintype "passive"))
    )
    (net (code "91") (name "/134") (class "Default")
      (node (ref "IC1") (pin "134") (pinfunction "P$134_134") (pintype "bidirectional"))
      (node (ref "JP4") (pin "26") (pinfunction "26_26") (pintype "passive"))
    )
    (net (code "92") (name "/135") (class "Default")
      (node (ref "IC1") (pin "135") (pinfunction "P$135_135") (pintype "bidirectional"))
      (node (ref "JP4") (pin "27") (pinfunction "27_27") (pintype "passive"))
      (node (ref "R5") (pin "2") (pinfunction "2_2") (pintype "passive"))
    )
    (net (code "93") (name "/137") (class "Default")
      (node (ref "IC1") (pin "137") (pinfunction "P$137_137") (pintype "bidirectional"))
      (node (ref "JP4") (pin "29") (pinfunction "29_29") (pintype "passive"))
    )
    (net (code "94") (name "/138") (class "Default")
      (node (ref "IC1") (pin "138") (pinfunction "P$138_138") (pintype "bidirectional"))
      (node (ref "JP4") (pin "30") (pinfunction "30_30") (pintype "passive"))
    )
    (net (code "95") (name "/139") (class "Default")
      (node (ref "IC1") (pin "139") (pinfunction "P$139_139") (pintype "bidirectional"))
      (node (ref "JP4") (pin "31") (pinfunction "31_31") (pintype "passive"))
    )
    (net (code "96") (name "/140") (class "Default")
      (node (ref "IC1") (pin "140") (pinfunction "P$140_140") (pintype "bidirectional"))
      (node (ref "JP4") (pin "32") (pinfunction "32_32") (pintype "passive"))
    )
    (net (code "97") (name "/141") (class "Default")
      (node (ref "IC1") (pin "141") (pinfunction "P$141_141") (pintype "bidirectional"))
      (node (ref "JP4") (pin "33") (pinfunction "33_33") (pintype "passive"))
    )
    (net (code "98") (name "/GND") (class "Default")
      (node (ref "C1") (pin "2") (pinfunction "2_2") (pintype "passive"))
      (node (ref "C10") (pin "2") (pinfunction "2_2") (pintype "passive"))
      (node (ref "C11") (pin "2") (pinfunction "2_2") (pintype "passive"))
      (node (ref "C12") (pin "2") (pinfunction "2_2") (pintype "passive"))
      (node (ref "C13") (pin "2") (pinfunction "2_2") (pintype "passive"))
      (node (ref "C14") (pin "2") (pinfunction "2_2") (pintype "passive"))
      (node (ref "C15") (pin "2") (pinfunction "2_2") (pintype "passive"))
      (node (ref "C16") (pin "2") (pinfunction "2_2") (pintype "passive"))
      (node (ref "C17") (pin "2") (pinfunction "2_2") (pintype "passive"))
      (node (ref "C18") (pin "2") (pinfunction "2_2") (pintype "passive"))
      (node (ref "C19") (pin "2") (pinfunction "2_2") (pintype "passive"))
      (node (ref "C2") (pin "2") (pinfunction "2_2") (pintype "passive"))
      (node (ref "C20") (pin "2") (pinfunction "2_2") (pintype "passive"))
      (node (ref "C22") (pin "2") (pinfunction "2_2") (pintype "passive"))
      (node (ref "C23") (pin "1") (pinfunction "1_1") (pintype "passive"))
      (node (ref "C24") (pin "2") (pinfunction "2_2") (pintype "passive"))
      (node (ref "C25") (pin "2") (pinfunction "2_2") (pintype "passive"))
      (node (ref "C26") (pin "2") (pinfunction "2_2") (pintype "passive"))
      (node (ref "C27") (pin "2") (pinfunction "2_2") (pintype "passive"))
      (node (ref "C28") (pin "2") (pinfunction "2_2") (pintype "passive"))
      (node (ref "C3") (pin "2") (pinfunction "2_2") (pintype "passive"))
      (node (ref "C31") (pin "2") (pinfunction "2_2") (pintype "passive"))
      (node (ref "C4") (pin "2") (pinfunction "2_2") (pintype "passive"))
      (node (ref "C5") (pin "2") (pinfunction "2_2") (pintype "passive"))
      (node (ref "C6") (pin "2") (pinfunction "2_2") (pintype "passive"))
      (node (ref "C7") (pin "2") (pinfunction "2_2") (pintype "passive"))
      (node (ref "C8") (pin "2") (pinfunction "2_2") (pintype "passive"))
      (node (ref "C9") (pin "2") (pinfunction "2_2") (pintype "passive"))
      (node (ref "IC1") (pin "104") (pinfunction "P$104_GND_104") (pintype "power_in"))
      (node (ref "IC1") (pin "11") (pinfunction "P$11_GND_11") (pintype "power_in"))
      (node (ref "IC1") (pin "110") (pinfunction "P$110_GND_110") (pintype "power_in"))
      (node (ref "IC1") (pin "119") (pinfunction "P$119_GND_119") (pintype "power_in"))
      (node (ref "IC1") (pin "133") (pinfunction "P$133_GND_133") (pintype "power_in"))
      (node (ref "IC1") (pin "143") (pinfunction "P$143_GND_143") (pintype "power_in"))
      (node (ref "IC1") (pin "145") (pinfunction "P$145_GND_145") (pintype "bidirectional"))
      (node (ref "IC1") (pin "20") (pinfunction "P$20_GND_20") (pintype "power_in"))
      (node (ref "IC1") (pin "30") (pinfunction "P$30_GND_30") (pintype "power_in"))
      (node (ref "IC1") (pin "38") (pinfunction "P$38_GND_38") (pintype "power_in"))
      (node (ref "IC1") (pin "45") (pinfunction "P$45_GND_45") (pintype "power_in"))
      (node (ref "IC1") (pin "57") (pinfunction "P$57_GND_57") (pintype "power_in"))
      (node (ref "IC1") (pin "66") (pinfunction "P$66_GND_66") (pintype "power_in"))
      (node (ref "IC1") (pin "83") (pinfunction "P$83_GND_83") (pintype "power_in"))
      (node (ref "IC1") (pin "96") (pinfunction "P$96_GND_96") (pintype "power_in"))
      (node (ref "JP1") (pin "11") (pinfunction "11_11") (pintype "passive"))
      (node (ref "JP1") (pin "20") (pinfunction "20_20") (pintype "passive"))
      (node (ref "JP1") (pin "30") (pinfunction "30_30") (pintype "passive"))
      (node (ref "JP2") (pin "2") (pinfunction "2_2") (pintype "passive"))
      (node (ref "JP2") (pin "21") (pinfunction "21_21") (pintype "passive"))
      (node (ref "JP2") (pin "30") (pinfunction "30_30") (pintype "passive"))
      (node (ref "JP2") (pin "9") (pinfunction "9_9") (pintype "passive"))
      (node (ref "JP3") (pin "11") (pinfunction "11_11") (pintype "passive"))
      (node (ref "JP3") (pin "24") (pinfunction "24_24") (pintype "passive"))
      (node (ref "JP3") (pin "32") (pinfunction "32_32") (pintype "passive"))
      (node (ref "JP4") (pin "11") (pinfunction "11_11") (pintype "passive"))
      (node (ref "JP4") (pin "2") (pinfunction "2_2") (pintype "passive"))
      (node (ref "JP4") (pin "25") (pinfunction "25_25") (pintype "passive"))
      (node (ref "JP4") (pin "35") (pinfunction "35_35") (pintype "passive"))
      (node (ref "JP5") (pin "10") (pinfunction "10_10") (pintype "passive"))
      (node (ref "JP5") (pin "2") (pinfunction "2_2") (pintype "passive"))
      (node (ref "QG1") (pin "2") (pinfunction "GND_2") (pintype "power_in"))
      (node (ref "R4") (pin "1") (pinfunction "1_1") (pintype "passive"))
      (node (ref "R8") (pin "2") (pinfunction "2_2") (pintype "passive"))
    )
    (net (code "99") (name "/TCK") (class "Default")
      (node (ref "IC1") (pin "16") (pinfunction "P$16_TCK_16") (pintype "bidirectional"))
      (node (ref "JP1") (pin "16") (pinfunction "16_16") (pintype "passive"))
      (node (ref "JP5") (pin "1") (pinfunction "1_1") (pintype "passive"))
      (node (ref "R4") (pin "2") (pinfunction "2_2") (pintype "passive"))
    )
    (net (code "100") (name "/TDI") (class "Default")
      (node (ref "IC1") (pin "17") (pinfunction "P$17_TDI_17") (pintype "bidirectional"))
      (node (ref "JP1") (pin "17") (pinfunction "17_17") (pintype "passive"))
      (node (ref "JP5") (pin "9") (pinfunction "9_9") (pintype "passive"))
      (node (ref "R3") (pin "1") (pinfunction "1_1") (pintype "passive"))
    )
    (net (code "101") (name "/TDO") (class "Default")
      (node (ref "IC1") (pin "18") (pinfunction "P$18_TDO_18") (pintype "bidirectional"))
      (node (ref "JP1") (pin "18") (pinfunction "18_18") (pintype "passive"))
      (node (ref "JP5") (pin "3") (pinfunction "3_3") (pintype "passive"))
    )
    (net (code "102") (name "/TMS") (class "Default")
      (node (ref "IC1") (pin "15") (pinfunction "P$15_TMS_15") (pintype "bidirectional"))
      (node (ref "JP1") (pin "15") (pinfunction "15_15") (pintype "passive"))
      (node (ref "JP5") (pin "5") (pinfunction "5_5") (pintype "passive"))
      (node (ref "R2") (pin "1") (pinfunction "1_1") (pintype "passive"))
    )
    (net (code "103") (name "/VCC") (class "Default")
      (node (ref "C1") (pin "1") (pinfunction "1_1") (pintype "passive"))
      (node (ref "C10") (pin "1") (pinfunction "1_1") (pintype "passive"))
      (node (ref "C11") (pin "1") (pinfunction "1_1") (pintype "passive"))
      (node (ref "C13") (pin "1") (pinfunction "1_1") (pintype "passive"))
      (node (ref "C14") (pin "1") (pinfunction "1_1") (pintype "passive"))
      (node (ref "C15") (pin "1") (pinfunction "1_1") (pintype "passive"))
      (node (ref "C16") (pin "1") (pinfunction "1_1") (pintype "passive"))
      (node (ref "C17") (pin "1") (pinfunction "1_1") (pintype "passive"))
      (node (ref "C18") (pin "1") (pinfunction "1_1") (pintype "passive"))
      (node (ref "C19") (pin "1") (pinfunction "1_1") (pintype "passive"))
      (node (ref "C20") (pin "1") (pinfunction "1_1") (pintype "passive"))
      (node (ref "C22") (pin "1") (pinfunction "1_1") (pintype "passive"))
      (node (ref "C24") (pin "1") (pinfunction "1_1") (pintype "passive"))
      (node (ref "C25") (pin "1") (pinfunction "1_1") (pintype "passive"))
      (node (ref "C26") (pin "1") (pinfunction "1_1") (pintype "passive"))
      (node (ref "C3") (pin "1") (pinfunction "1_1") (pintype "passive"))
      (node (ref "C31") (pin "1") (pinfunction "1_1") (pintype "passive"))
      (node (ref "C4") (pin "1") (pinfunction "1_1") (pintype "passive"))
      (node (ref "C5") (pin "1") (pinfunction "1_1") (pintype "passive"))
      (node (ref "C6") (pin "1") (pinfunction "1_1") (pintype "passive"))
      (node (ref "C7") (pin "1") (pinfunction "1_1") (pintype "passive"))
      (node (ref "C9") (pin "1") (pinfunction "1_1") (pintype "passive"))
      (node (ref "IC1") (pin "1") (pinfunction "P$1_VCCONE_1") (pintype "power_in"))
      (node (ref "IC1") (pin "102") (pinfunction "P$102_VCCIO6_102") (pintype "power_in"))
      (node (ref "IC1") (pin "108") (pinfunction "P$108_VCCONE_108") (pintype "power_in"))
      (node (ref "IC1") (pin "109") (pinfunction "P$109_VCCONE_109") (pintype "power_in"))
      (node (ref "IC1") (pin "111") (pinfunction "P$111_VCCIO8_111") (pintype "power_in"))
      (node (ref "IC1") (pin "118") (pinfunction "P$118__VCCONE_118") (pintype "power_in"))
      (node (ref "IC1") (pin "12") (pinfunction "P$12_VCCIO1_12") (pintype "power_in"))
      (node (ref "IC1") (pin "121") (pinfunction "P$121_VCCIO8_121") (pintype "power_in"))
      (node (ref "IC1") (pin "132") (pinfunction "P$132__VCCONE_132") (pintype "power_in"))
      (node (ref "IC1") (pin "136") (pinfunction "P$136_VCCIO8_136") (pintype "power_in"))
      (node (ref "IC1") (pin "142") (pinfunction "P$142__VCCONE_142") (pintype "power_in"))
      (node (ref "IC1") (pin "144") (pinfunction "P$144_VCCONE_144") (pintype "power_in"))
      (node (ref "IC1") (pin "22") (pinfunction "P$22_VCCIO1_22") (pintype "power_in"))
      (node (ref "IC1") (pin "29") (pinfunction "P$29_VCCIO2_29") (pintype "power_in"))
      (node (ref "IC1") (pin "36") (pinfunction "P$36_VCCONE_36") (pintype "power_in"))
      (node (ref "IC1") (pin "37") (pinfunction "P$37_VCCONE_37") (pintype "power_in"))
      (node (ref "IC1") (pin "43") (pinfunction "P$43_VCCIO3_43") (pintype "power_in"))
      (node (ref "IC1") (pin "56") (pinfunction "P$56_VCCIO3_56") (pintype "power_in"))
      (node (ref "IC1") (pin "58") (pinfunction "P$58_VCCONE_58") (pintype "power_in"))
      (node (ref "IC1") (pin "64") (pinfunction "P$64_VCCIO3_64") (pintype "power_in"))
      (node (ref "IC1") (pin "72") (pinfunction "P$72_VCCONE_72") (pintype "power_in"))
      (node (ref "IC1") (pin "73") (pinfunction "P$73_VCCONE_73") (pintype "power_in"))
      (node (ref "IC1") (pin "82") (pinfunction "P$82_VCCIO5_82") (pintype "power_in"))
      (node (ref "IC1") (pin "93") (pinfunction "P$93_VCCIO6_93") (pintype "power_in"))
      (node (ref "JP1") (pin "1") (pinfunction "1_1") (pintype "passive"))
      (node (ref "JP1") (pin "12") (pinfunction "12_12") (pintype "passive"))
      (node (ref "JP1") (pin "2") (pinfunction "2_2") (pintype "passive"))
      (node (ref "JP1") (pin "22") (pinfunction "22_22") (pintype "passive"))
      (node (ref "JP1") (pin "29") (pinfunction "29_29") (pintype "passive"))
      (node (ref "JP1") (pin "34") (pinfunction "34_34") (pintype "passive"))
      (node (ref "JP1") (pin "35") (pinfunction "35_35") (pintype "passive"))
      (node (ref "JP1") (pin "36") (pinfunction "36_36") (pintype "passive"))
      (node (ref "JP2") (pin "1") (pinfunction "1_1") (pintype "passive"))
      (node (ref "JP2") (pin "20") (pinfunction "20_20") (pintype "passive"))
      (node (ref "JP2") (pin "22") (pinfunction "22_22") (pintype "passive"))
      (node (ref "JP2") (pin "28") (pinfunction "28_28") (pintype "passive"))
      (node (ref "JP2") (pin "35") (pinfunction "35_35") (pintype "passive"))
      (node (ref "JP2") (pin "36") (pinfunction "36_36") (pintype "passive"))
      (node (ref "JP2") (pin "7") (pinfunction "7_7") (pintype "passive"))
      (node (ref "JP3") (pin "1") (pinfunction "1_1") (pintype "passive"))
      (node (ref "JP3") (pin "10") (pinfunction "10_10") (pintype "passive"))
      (node (ref "JP3") (pin "21") (pinfunction "21_21") (pintype "passive"))
      (node (ref "JP3") (pin "30") (pinfunction "30_30") (pintype "passive"))
      (node (ref "JP3") (pin "35") (pinfunction "35_35") (pintype "passive"))
      (node (ref "JP3") (pin "36") (pinfunction "36_36") (pintype "passive"))
      (node (ref "JP4") (pin "1") (pinfunction "1_1") (pintype "passive"))
      (node (ref "JP4") (pin "10") (pinfunction "10_10") (pintype "passive"))
      (node (ref "JP4") (pin "13") (pinfunction "13_13") (pintype "passive"))
      (node (ref "JP4") (pin "24") (pinfunction "24_24") (pintype "passive"))
      (node (ref "JP4") (pin "28") (pinfunction "28_28") (pintype "passive"))
      (node (ref "JP4") (pin "3") (pinfunction "3_3") (pintype "passive"))
      (node (ref "JP4") (pin "34") (pinfunction "34_34") (pintype "passive"))
      (node (ref "JP4") (pin "36") (pinfunction "36_36") (pintype "passive"))
      (node (ref "JP5") (pin "4") (pinfunction "4_4") (pintype "passive"))
      (node (ref "L1") (pin "2") (pinfunction "2_2") (pintype "passive"))
      (node (ref "QG1") (pin "4") (pinfunction "VCC_4") (pintype "power_in"))
      (node (ref "R2") (pin "2") (pinfunction "2_2") (pintype "passive"))
      (node (ref "R3") (pin "2") (pinfunction "2_2") (pintype "passive"))
      (node (ref "R5") (pin "1") (pinfunction "1_1") (pintype "passive"))
      (node (ref "R6") (pin "1") (pinfunction "1_1") (pintype "passive"))
      (node (ref "R7") (pin "1") (pinfunction "1_1") (pintype "passive"))
      (node (ref "R9") (pin "1") (pinfunction "1_1") (pintype "passive"))
    )
    (net (code "104") (name "/VCCA") (class "Default")
      (node (ref "C12") (pin "1") (pinfunction "1_1") (pintype "passive"))
      (node (ref "C2") (pin "1") (pinfunction "1_1") (pintype "passive"))
      (node (ref "C23") (pin "2") (pinfunction "2_2") (pintype "passive"))
      (node (ref "C27") (pin "1") (pinfunction "1_1") (pintype "passive"))
      (node (ref "C28") (pin "1") (pinfunction "1_1") (pintype "passive"))
      (node (ref "C8") (pin "1") (pinfunction "1_1") (pintype "passive"))
      (node (ref "IC1") (pin "107") (pinfunction "P$107_VCCA3_107") (pintype "power_in"))
      (node (ref "IC1") (pin "2") (pinfunction "P$2_VCCA4_2") (pintype "power_in"))
      (node (ref "IC1") (pin "34") (pinfunction "P$34_VCCA2_34") (pintype "power_in"))
      (node (ref "IC1") (pin "35") (pinfunction "P$35_VCCA1_35") (pintype "power_in"))
      (node (ref "IC1") (pin "71") (pinfunction "P$71_VCCA5_71") (pintype "power_in"))
      (node (ref "L1") (pin "1") (pinfunction "1_1") (pintype "passive"))
    )
    (net (code "105") (name "Net-(QG1-OUT)") (class "Default")
      (node (ref "QG1") (pin "3") (pinfunction "OUT_3") (pintype "output"))
      (node (ref "R1") (pin "1") (pinfunction "1_1") (pintype "passive"))
    )
    (net (code "106") (name "Net-(R8-Pad1)") (class "Default")
      (node (ref "R8") (pin "1") (pinfunction "1_1") (pintype "passive"))
      (node (ref "SJ1") (pin "3") (pinfunction "3_3") (pintype "passive"))
    )
    (net (code "107") (name "Net-(R9-Pad2)") (class "Default")
      (node (ref "R9") (pin "2") (pinfunction "2_2") (pintype "passive"))
      (node (ref "SJ1") (pin "1") (pinfunction "1_1") (pintype "passive"))
    )
    (net (code "108") (name "unconnected-(JP5-Pad6)") (class "Default")
      (node (ref "JP5") (pin "6") (pinfunction "6_6") (pintype "passive"))
    )
    (net (code "109") (name "unconnected-(JP5-Pad7)") (class "Default")
      (node (ref "JP5") (pin "7") (pinfunction "7_7") (pintype "passive"))
    )
    (net (code "110") (name "unconnected-(JP5-Pad8)") (class "Default")
      (node (ref "JP5") (pin "8") (pinfunction "8_8") (pintype "passive"))
    )
    (net (code "111") (name "unconnected-(PAD1-P-Pad1)") (class "Default")
      (node (ref "PAD1") (pin "1") (pinfunction "P_1") (pintype "passive"))
    )
    (net (code "112") (name "unconnected-(PAD2-P-Pad1)") (class "Default")
      (node (ref "PAD2") (pin "1") (pinfunction "P_1") (pintype "passive"))
    )
    (net (code "113") (name "unconnected-(PAD3-P-Pad1)") (class "Default")
      (node (ref "PAD3") (pin "1") (pinfunction "P_1") (pintype "passive"))
    )
    (net (code "114") (name "unconnected-(PAD4-P-Pad1)") (class "Default")
      (node (ref "PAD4") (pin "1") (pinfunction "P_1") (pintype "passive"))
    )
    (net (code "115") (name "unconnected-(PAD5-P-Pad1)") (class "Default")
      (node (ref "PAD5") (pin "1") (pinfunction "P_1") (pintype "passive"))
    )
    (net (code "116") (name "unconnected-(PAD6-P-Pad1)") (class "Default")
      (node (ref "PAD6") (pin "1") (pinfunction "P_1") (pintype "passive"))
    )
    (net (code "117") (name "unconnected-(PAD7-P-Pad1)") (class "Default")
      (node (ref "PAD7") (pin "1") (pinfunction "P_1") (pintype "passive"))
    )
    (net (code "118") (name "unconnected-(PAD8-P-Pad1)") (class "Default")
      (node (ref "PAD8") (pin "1") (pinfunction "P_1") (pintype "passive"))
    )
    (net (code "119") (name "unconnected-(PAD9-P-Pad1)") (class "Default")
      (node (ref "PAD9") (pin "1") (pinfunction "P_1") (pintype "passive"))
    )
    (net (code "120") (name "unconnected-(PAD10-P-Pad1)") (class "Default")
      (node (ref "PAD10") (pin "1") (pinfunction "P_1") (pintype "passive"))
    )
    (net (code "121") (name "unconnected-(PAD11-P-Pad1)") (class "Default")
      (node (ref "PAD11") (pin "1") (pinfunction "P_1") (pintype "passive"))
    )
    (net (code "122") (name "unconnected-(PAD12-P-Pad1)") (class "Default")
      (node (ref "PAD12") (pin "1") (pinfunction "P_1") (pintype "passive"))
    )
    (net (code "123") (name "unconnected-(PAD13-P-Pad1)") (class "Default")
      (node (ref "PAD13") (pin "1") (pinfunction "P_1") (pintype "passive"))
    )
    (net (code "124") (name "unconnected-(PAD14-P-Pad1)") (class "Default")
      (node (ref "PAD14") (pin "1") (pinfunction "P_1") (pintype "passive"))
    )
    (net (code "125") (name "unconnected-(PAD15-P-Pad1)") (class "Default")
      (node (ref "PAD15") (pin "1") (pinfunction "P_1") (pintype "passive"))
    )
    (net (code "126") (name "unconnected-(PAD16-P-Pad1)") (class "Default")
      (node (ref "PAD16") (pin "1") (pinfunction "P_1") (pintype "passive"))
    )
    (net (code "127") (name "unconnected-(PAD17-P-Pad1)") (class "Default")
      (node (ref "PAD17") (pin "1") (pinfunction "P_1") (pintype "passive"))
    )
    (net (code "128") (name "unconnected-(PAD18-P-Pad1)") (class "Default")
      (node (ref "PAD18") (pin "1") (pinfunction "P_1") (pintype "passive"))
    )
    (net (code "129") (name "unconnected-(PAD19-P-Pad1)") (class "Default")
      (node (ref "PAD19") (pin "1") (pinfunction "P_1") (pintype "passive"))
    )
    (net (code "130") (name "unconnected-(PAD20-P-Pad1)") (class "Default")
      (node (ref "PAD20") (pin "1") (pinfunction "P_1") (pintype "passive"))
    )
    (net (code "131") (name "unconnected-(PAD21-P-Pad1)") (class "Default")
      (node (ref "PAD21") (pin "1") (pinfunction "P_1") (pintype "passive"))
    )
    (net (code "132") (name "unconnected-(PAD22-P-Pad1)") (class "Default")
      (node (ref "PAD22") (pin "1") (pinfunction "P_1") (pintype "passive"))
    )
    (net (code "133") (name "unconnected-(PAD23-P-Pad1)") (class "Default")
      (node (ref "PAD23") (pin "1") (pinfunction "P_1") (pintype "passive"))
    )
    (net (code "134") (name "unconnected-(PAD24-P-Pad1)") (class "Default")
      (node (ref "PAD24") (pin "1") (pinfunction "P_1") (pintype "passive"))
    )
    (net (code "135") (name "unconnected-(PAD25-P-Pad1)") (class "Default")
      (node (ref "PAD25") (pin "1") (pinfunction "P_1") (pintype "passive"))
    )
    (net (code "136") (name "unconnected-(PAD26-P-Pad1)") (class "Default")
      (node (ref "PAD26") (pin "1") (pinfunction "P_1") (pintype "passive"))
    )
    (net (code "137") (name "unconnected-(PAD27-P-Pad1)") (class "Default")
      (node (ref "PAD27") (pin "1") (pinfunction "P_1") (pintype "passive"))
    )
    (net (code "138") (name "unconnected-(PAD28-P-Pad1)") (class "Default")
      (node (ref "PAD28") (pin "1") (pinfunction "P_1") (pintype "passive"))
    )
    (net (code "139") (name "unconnected-(PAD29-P-Pad1)") (class "Default")
      (node (ref "PAD29") (pin "1") (pinfunction "P_1") (pintype "passive"))
    )
    (net (code "140") (name "unconnected-(PAD30-P-Pad1)") (class "Default")
      (node (ref "PAD30") (pin "1") (pinfunction "P_1") (pintype "passive"))
    )
    (net (code "141") (name "unconnected-(PAD31-P-Pad1)") (class "Default")
      (node (ref "PAD31") (pin "1") (pinfunction "P_1") (pintype "passive"))
    )
    (net (code "142") (name "unconnected-(PAD32-P-Pad1)") (class "Default")
      (node (ref "PAD32") (pin "1") (pinfunction "P_1") (pintype "passive"))
    )
    (net (code "143") (name "unconnected-(PAD33-P-Pad1)") (class "Default")
      (node (ref "PAD33") (pin "1") (pinfunction "P_1") (pintype "passive"))
    )
    (net (code "144") (name "unconnected-(PAD34-P-Pad1)") (class "Default")
      (node (ref "PAD34") (pin "1") (pinfunction "P_1") (pintype "passive"))
    )
    (net (code "145") (name "unconnected-(PAD35-P-Pad1)") (class "Default")
      (node (ref "PAD35") (pin "1") (pinfunction "P_1") (pintype "passive"))
    )
    (net (code "146") (name "unconnected-(PAD36-P-Pad1)") (class "Default")
      (node (ref "PAD36") (pin "1") (pinfunction "P_1") (pintype "passive"))
    )
    (net (code "147") (name "unconnected-(PAD37-P-Pad1)") (class "Default")
      (node (ref "PAD37") (pin "1") (pinfunction "P_1") (pintype "passive"))
    )
    (net (code "148") (name "unconnected-(PAD38-P-Pad1)") (class "Default")
      (node (ref "PAD38") (pin "1") (pinfunction "P_1") (pintype "passive"))
    )
    (net (code "149") (name "unconnected-(PAD39-P-Pad1)") (class "Default")
      (node (ref "PAD39") (pin "1") (pinfunction "P_1") (pintype "passive"))
    )
    (net (code "150") (name "unconnected-(PAD40-P-Pad1)") (class "Default")
      (node (ref "PAD40") (pin "1") (pinfunction "P_1") (pintype "passive"))
    )
    (net (code "151") (name "unconnected-(PAD41-P-Pad1)") (class "Default")
      (node (ref "PAD41") (pin "1") (pinfunction "P_1") (pintype "passive"))
    )
    (net (code "152") (name "unconnected-(PAD42-P-Pad1)") (class "Default")
      (node (ref "PAD42") (pin "1") (pinfunction "P_1") (pintype "passive"))
    )
    (net (code "153") (name "unconnected-(PAD43-P-Pad1)") (class "Default")
      (node (ref "PAD43") (pin "1") (pinfunction "P_1") (pintype "passive"))
    )
    (net (code "154") (name "unconnected-(PAD44-P-Pad1)") (class "Default")
      (node (ref "PAD44") (pin "1") (pinfunction "P_1") (pintype "passive"))
    )
    (net (code "155") (name "unconnected-(PAD45-P-Pad1)") (class "Default")
      (node (ref "PAD45") (pin "1") (pinfunction "P_1") (pintype "passive"))
    )
    (net (code "156") (name "unconnected-(PAD46-P-Pad1)") (class "Default")
      (node (ref "PAD46") (pin "1") (pinfunction "P_1") (pintype "passive"))
    )
    (net (code "157") (name "unconnected-(PAD47-P-Pad1)") (class "Default")
      (node (ref "PAD47") (pin "1") (pinfunction "P_1") (pintype "passive"))
    )
    (net (code "158") (name "unconnected-(PAD48-P-Pad1)") (class "Default")
      (node (ref "PAD48") (pin "1") (pinfunction "P_1") (pintype "passive"))
    )
    (net (code "159") (name "unconnected-(PAD49-P-Pad1)") (class "Default")
      (node (ref "PAD49") (pin "1") (pinfunction "P_1") (pintype "passive"))
    )
    (net (code "160") (name "unconnected-(PAD50-P-Pad1)") (class "Default")
      (node (ref "PAD50") (pin "1") (pinfunction "P_1") (pintype "passive"))
    )
    (net (code "161") (name "unconnected-(PAD51-P-Pad1)") (class "Default")
      (node (ref "PAD51") (pin "1") (pinfunction "P_1") (pintype "passive"))
    )
    (net (code "162") (name "unconnected-(PAD52-P-Pad1)") (class "Default")
      (node (ref "PAD52") (pin "1") (pinfunction "P_1") (pintype "passive"))
    )
    (net (code "163") (name "unconnected-(PAD53-P-Pad1)") (class "Default")
      (node (ref "PAD53") (pin "1") (pinfunction "P_1") (pintype "passive"))
    )
    (net (code "164") (name "unconnected-(PAD54-P-Pad1)") (class "Default")
      (node (ref "PAD54") (pin "1") (pinfunction "P_1") (pintype "passive"))
    )
    (net (code "165") (name "unconnected-(PAD55-P-Pad1)") (class "Default")
      (node (ref "PAD55") (pin "1") (pinfunction "P_1") (pintype "passive"))
    )
    (net (code "166") (name "unconnected-(PAD56-P-Pad1)") (class "Default")
      (node (ref "PAD56") (pin "1") (pinfunction "P_1") (pintype "passive"))
    )
    (net (code "167") (name "unconnected-(PAD57-P-Pad1)") (class "Default")
      (node (ref "PAD57") (pin "1") (pinfunction "P_1") (pintype "passive"))
    )
    (net (code "168") (name "unconnected-(PAD58-P-Pad1)") (class "Default")
      (node (ref "PAD58") (pin "1") (pinfunction "P_1") (pintype "passive"))
    )
    (net (code "169") (name "unconnected-(PAD59-P-Pad1)") (class "Default")
      (node (ref "PAD59") (pin "1") (pinfunction "P_1") (pintype "passive"))
    )
    (net (code "170") (name "unconnected-(PAD60-P-Pad1)") (class "Default")
      (node (ref "PAD60") (pin "1") (pinfunction "P_1") (pintype "passive"))
    )
    (net (code "171") (name "unconnected-(PAD61-P-Pad1)") (class "Default")
      (node (ref "PAD61") (pin "1") (pinfunction "P_1") (pintype "passive"))
    )
    (net (code "172") (name "unconnected-(PAD62-P-Pad1)") (class "Default")
      (node (ref "PAD62") (pin "1") (pinfunction "P_1") (pintype "passive"))
    )
    (net (code "173") (name "unconnected-(PAD63-P-Pad1)") (class "Default")
      (node (ref "PAD63") (pin "1") (pinfunction "P_1") (pintype "passive"))
    )
    (net (code "174") (name "unconnected-(PAD64-P-Pad1)") (class "Default")
      (node (ref "PAD64") (pin "1") (pinfunction "P_1") (pintype "passive"))
    )
    (net (code "175") (name "unconnected-(PAD65-P-Pad1)") (class "Default")
      (node (ref "PAD65") (pin "1") (pinfunction "P_1") (pintype "passive"))
    )
    (net (code "176") (name "unconnected-(PAD66-P-Pad1)") (class "Default")
      (node (ref "PAD66") (pin "1") (pinfunction "P_1") (pintype "passive"))
    )
    (net (code "177") (name "unconnected-(PAD67-P-Pad1)") (class "Default")
      (node (ref "PAD67") (pin "1") (pinfunction "P_1") (pintype "passive"))
    )
    (net (code "178") (name "unconnected-(PAD68-P-Pad1)") (class "Default")
      (node (ref "PAD68") (pin "1") (pinfunction "P_1") (pintype "passive"))
    )
    (net (code "179") (name "unconnected-(PAD69-P-Pad1)") (class "Default")
      (node (ref "PAD69") (pin "1") (pinfunction "P_1") (pintype "passive"))
    )
    (net (code "180") (name "unconnected-(PAD70-P-Pad1)") (class "Default")
      (node (ref "PAD70") (pin "1") (pinfunction "P_1") (pintype "passive"))
    )
    (net (code "181") (name "unconnected-(PAD71-P-Pad1)") (class "Default")
      (node (ref "PAD71") (pin "1") (pinfunction "P_1") (pintype "passive"))
    )
    (net (code "182") (name "unconnected-(PAD72-P-Pad1)") (class "Default")
      (node (ref "PAD72") (pin "1") (pinfunction "P_1") (pintype "passive"))
    )
    (net (code "183") (name "unconnected-(PAD73-P-Pad1)") (class "Default")
      (node (ref "PAD73") (pin "1") (pinfunction "P_1") (pintype "passive"))
    )
    (net (code "184") (name "unconnected-(PAD74-P-Pad1)") (class "Default")
      (node (ref "PAD74") (pin "1") (pinfunction "P_1") (pintype "passive"))
    )
    (net (code "185") (name "unconnected-(PAD75-P-Pad1)") (class "Default")
      (node (ref "PAD75") (pin "1") (pinfunction "P_1") (pintype "passive"))
    )
    (net (code "186") (name "unconnected-(PAD76-P-Pad1)") (class "Default")
      (node (ref "PAD76") (pin "1") (pinfunction "P_1") (pintype "passive"))
    )
    (net (code "187") (name "unconnected-(PAD77-P-Pad1)") (class "Default")
      (node (ref "PAD77") (pin "1") (pinfunction "P_1") (pintype "passive"))
    )
    (net (code "188") (name "unconnected-(PAD78-P-Pad1)") (class "Default")
      (node (ref "PAD78") (pin "1") (pinfunction "P_1") (pintype "passive"))
    )
    (net (code "189") (name "unconnected-(PAD79-P-Pad1)") (class "Default")
      (node (ref "PAD79") (pin "1") (pinfunction "P_1") (pintype "passive"))
    )
    (net (code "190") (name "unconnected-(PAD80-P-Pad1)") (class "Default")
      (node (ref "PAD80") (pin "1") (pinfunction "P_1") (pintype "passive"))
    )
    (net (code "191") (name "unconnected-(PAD81-P-Pad1)") (class "Default")
      (node (ref "PAD81") (pin "1") (pinfunction "P_1") (pintype "passive"))
    )
    (net (code "192") (name "unconnected-(PAD82-P-Pad1)") (class "Default")
      (node (ref "PAD82") (pin "1") (pinfunction "P_1") (pintype "passive"))
    )
    (net (code "193") (name "unconnected-(PAD83-P-Pad1)") (class "Default")
      (node (ref "PAD83") (pin "1") (pinfunction "P_1") (pintype "passive"))
    )
    (net (code "194") (name "unconnected-(PAD84-P-Pad1)") (class "Default")
      (node (ref "PAD84") (pin "1") (pinfunction "P_1") (pintype "passive"))
    )
    (net (code "195") (name "unconnected-(PAD85-P-Pad1)") (class "Default")
      (node (ref "PAD85") (pin "1") (pinfunction "P_1") (pintype "passive"))
    )
    (net (code "196") (name "unconnected-(PAD86-P-Pad1)") (class "Default")
      (node (ref "PAD86") (pin "1") (pinfunction "P_1") (pintype "passive"))
    )
    (net (code "197") (name "unconnected-(PAD87-P-Pad1)") (class "Default")
      (node (ref "PAD87") (pin "1") (pinfunction "P_1") (pintype "passive"))
    )
    (net (code "198") (name "unconnected-(PAD88-P-Pad1)") (class "Default")
      (node (ref "PAD88") (pin "1") (pinfunction "P_1") (pintype "passive"))
    )
    (net (code "199") (name "unconnected-(PAD89-P-Pad1)") (class "Default")
      (node (ref "PAD89") (pin "1") (pinfunction "P_1") (pintype "passive"))
    )
    (net (code "200") (name "unconnected-(PAD90-P-Pad1)") (class "Default")
      (node (ref "PAD90") (pin "1") (pinfunction "P_1") (pintype "passive"))
    )
    (net (code "201") (name "unconnected-(PAD91-P-Pad1)") (class "Default")
      (node (ref "PAD91") (pin "1") (pinfunction "P_1") (pintype "passive"))
    )
    (net (code "202") (name "unconnected-(PAD92-P-Pad1)") (class "Default")
      (node (ref "PAD92") (pin "1") (pinfunction "P_1") (pintype "passive"))
    )
    (net (code "203") (name "unconnected-(PAD93-P-Pad1)") (class "Default")
      (node (ref "PAD93") (pin "1") (pinfunction "P_1") (pintype "passive"))
    )
    (net (code "204") (name "unconnected-(PAD94-P-Pad1)") (class "Default")
      (node (ref "PAD94") (pin "1") (pinfunction "P_1") (pintype "passive"))
    )
    (net (code "205") (name "unconnected-(PAD95-P-Pad1)") (class "Default")
      (node (ref "PAD95") (pin "1") (pinfunction "P_1") (pintype "passive"))
    )
    (net (code "206") (name "unconnected-(PAD96-P-Pad1)") (class "Default")
      (node (ref "PAD96") (pin "1") (pinfunction "P_1") (pintype "passive"))
    )
    (net (code "207") (name "unconnected-(PAD97-P-Pad1)") (class "Default")
      (node (ref "PAD97") (pin "1") (pinfunction "P_1") (pintype "passive"))
    )
    (net (code "208") (name "unconnected-(PAD98-P-Pad1)") (class "Default")
      (node (ref "PAD98") (pin "1") (pinfunction "P_1") (pintype "passive"))
    )
    (net (code "209") (name "unconnected-(PAD99-P-Pad1)") (class "Default")
      (node (ref "PAD99") (pin "1") (pinfunction "P_1") (pintype "passive"))
    )
    (net (code "210") (name "unconnected-(PAD100-P-Pad1)") (class "Default")
      (node (ref "PAD100") (pin "1") (pinfunction "P_1") (pintype "passive"))
    )
    (net (code "211") (name "unconnected-(PAD101-P-Pad1)") (class "Default")
      (node (ref "PAD101") (pin "1") (pinfunction "P_1") (pintype "passive"))
    )
    (net (code "212") (name "unconnected-(PAD102-P-Pad1)") (class "Default")
      (node (ref "PAD102") (pin "1") (pinfunction "P_1") (pintype "passive"))
    )
    (net (code "213") (name "unconnected-(PAD103-P-Pad1)") (class "Default")
      (node (ref "PAD103") (pin "1") (pinfunction "P_1") (pintype "passive"))
    )
    (net (code "214") (name "unconnected-(PAD104-P-Pad1)") (class "Default")
      (node (ref "PAD104") (pin "1") (pinfunction "P_1") (pintype "passive"))
    )
    (net (code "215") (name "unconnected-(PAD105-P-Pad1)") (class "Default")
      (node (ref "PAD105") (pin "1") (pinfunction "P_1") (pintype "passive"))
    )
    (net (code "216") (name "unconnected-(PAD106-P-Pad1)") (class "Default")
      (node (ref "PAD106") (pin "1") (pinfunction "P_1") (pintype "passive"))
    )
    (net (code "217") (name "unconnected-(PAD107-P-Pad1)") (class "Default")
      (node (ref "PAD107") (pin "1") (pinfunction "P_1") (pintype "passive"))
    )
    (net (code "218") (name "unconnected-(PAD108-P-Pad1)") (class "Default")
      (node (ref "PAD108") (pin "1") (pinfunction "P_1") (pintype "passive"))
    )
    (net (code "219") (name "unconnected-(PAD109-P-Pad1)") (class "Default")
      (node (ref "PAD109") (pin "1") (pinfunction "P_1") (pintype "passive"))
    )
    (net (code "220") (name "unconnected-(PAD110-P-Pad1)") (class "Default")
      (node (ref "PAD110") (pin "1") (pinfunction "P_1") (pintype "passive"))
    )
    (net (code "221") (name "unconnected-(PAD111-P-Pad1)") (class "Default")
      (node (ref "PAD111") (pin "1") (pinfunction "P_1") (pintype "passive"))
    )
    (net (code "222") (name "unconnected-(PAD112-P-Pad1)") (class "Default")
      (node (ref "PAD112") (pin "1") (pinfunction "P_1") (pintype "passive"))
    )
    (net (code "223") (name "unconnected-(PAD113-P-Pad1)") (class "Default")
      (node (ref "PAD113") (pin "1") (pinfunction "P_1") (pintype "passive"))
    )
    (net (code "224") (name "unconnected-(PAD114-P-Pad1)") (class "Default")
      (node (ref "PAD114") (pin "1") (pinfunction "P_1") (pintype "passive"))
    )
    (net (code "225") (name "unconnected-(PAD115-P-Pad1)") (class "Default")
      (node (ref "PAD115") (pin "1") (pinfunction "P_1") (pintype "passive"))
    )
    (net (code "226") (name "unconnected-(PAD116-P-Pad1)") (class "Default")
      (node (ref "PAD116") (pin "1") (pinfunction "P_1") (pintype "passive"))
    )
    (net (code "227") (name "unconnected-(PAD117-P-Pad1)") (class "Default")
      (node (ref "PAD117") (pin "1") (pinfunction "P_1") (pintype "passive"))
    )
    (net (code "228") (name "unconnected-(PAD118-P-Pad1)") (class "Default")
      (node (ref "PAD118") (pin "1") (pinfunction "P_1") (pintype "passive"))
    )
    (net (code "229") (name "unconnected-(PAD119-P-Pad1)") (class "Default")
      (node (ref "PAD119") (pin "1") (pinfunction "P_1") (pintype "passive"))
    )
    (net (code "230") (name "unconnected-(PAD120-P-Pad1)") (class "Default")
      (node (ref "PAD120") (pin "1") (pinfunction "P_1") (pintype "passive"))
    )
    (net (code "231") (name "unconnected-(PAD121-P-Pad1)") (class "Default")
      (node (ref "PAD121") (pin "1") (pinfunction "P_1") (pintype "passive"))
    )
    (net (code "232") (name "unconnected-(PAD122-P-Pad1)") (class "Default")
      (node (ref "PAD122") (pin "1") (pinfunction "P_1") (pintype "passive"))
    )
    (net (code "233") (name "unconnected-(PAD123-P-Pad1)") (class "Default")
      (node (ref "PAD123") (pin "1") (pinfunction "P_1") (pintype "passive"))
    )
    (net (code "234") (name "unconnected-(PAD124-P-Pad1)") (class "Default")
      (node (ref "PAD124") (pin "1") (pinfunction "P_1") (pintype "passive"))
    )
    (net (code "235") (name "unconnected-(PAD125-P-Pad1)") (class "Default")
      (node (ref "PAD125") (pin "1") (pinfunction "P_1") (pintype "passive"))
    )
    (net (code "236") (name "unconnected-(PAD126-P-Pad1)") (class "Default")
      (node (ref "PAD126") (pin "1") (pinfunction "P_1") (pintype "passive"))
    )
    (net (code "237") (name "unconnected-(PAD127-P-Pad1)") (class "Default")
      (node (ref "PAD127") (pin "1") (pinfunction "P_1") (pintype "passive"))
    )
    (net (code "238") (name "unconnected-(PAD128-P-Pad1)") (class "Default")
      (node (ref "PAD128") (pin "1") (pinfunction "P_1") (pintype "passive"))
    )
    (net (code "239") (name "unconnected-(PAD129-P-Pad1)") (class "Default")
      (node (ref "PAD129") (pin "1") (pinfunction "P_1") (pintype "passive"))
    )
    (net (code "240") (name "unconnected-(PAD130-P-Pad1)") (class "Default")
      (node (ref "PAD130") (pin "1") (pinfunction "P_1") (pintype "passive"))
    )
    (net (code "241") (name "unconnected-(PAD131-P-Pad1)") (class "Default")
      (node (ref "PAD131") (pin "1") (pinfunction "P_1") (pintype "passive"))
    )
    (net (code "242") (name "unconnected-(PAD132-P-Pad1)") (class "Default")
      (node (ref "PAD132") (pin "1") (pinfunction "P_1") (pintype "passive"))
    )
    (net (code "243") (name "unconnected-(PAD133-P-Pad1)") (class "Default")
      (node (ref "PAD133") (pin "1") (pinfunction "P_1") (pintype "passive"))
    )
    (net (code "244") (name "unconnected-(PAD134-P-Pad1)") (class "Default")
      (node (ref "PAD134") (pin "1") (pinfunction "P_1") (pintype "passive"))
    )
    (net (code "245") (name "unconnected-(PAD135-P-Pad1)") (class "Default")
      (node (ref "PAD135") (pin "1") (pinfunction "P_1") (pintype "passive"))
    )
    (net (code "246") (name "unconnected-(PAD136-P-Pad1)") (class "Default")
      (node (ref "PAD136") (pin "1") (pinfunction "P_1") (pintype "passive"))
    )
    (net (code "247") (name "unconnected-(PAD137-P-Pad1)") (class "Default")
      (node (ref "PAD137") (pin "1") (pinfunction "P_1") (pintype "passive"))
    )
    (net (code "248") (name "unconnected-(PAD138-P-Pad1)") (class "Default")
      (node (ref "PAD138") (pin "1") (pinfunction "P_1") (pintype "passive"))
    )
    (net (code "249") (name "unconnected-(PAD139-P-Pad1)") (class "Default")
      (node (ref "PAD139") (pin "1") (pinfunction "P_1") (pintype "passive"))
    )
    (net (code "250") (name "unconnected-(PAD140-P-Pad1)") (class "Default")
      (node (ref "PAD140") (pin "1") (pinfunction "P_1") (pintype "passive"))
    )
    (net (code "251") (name "unconnected-(PAD141-P-Pad1)") (class "Default")
      (node (ref "PAD141") (pin "1") (pinfunction "P_1") (pintype "passive"))
    )
    (net (code "252") (name "unconnected-(PAD142-P-Pad1)") (class "Default")
      (node (ref "PAD142") (pin "1") (pinfunction "P_1") (pintype "passive"))
    )
    (net (code "253") (name "unconnected-(PAD143-P-Pad1)") (class "Default")
      (node (ref "PAD143") (pin "1") (pinfunction "P_1") (pintype "passive"))
    )
    (net (code "254") (name "unconnected-(PAD144-P-Pad1)") (class "Default")
      (node (ref "PAD144") (pin "1") (pinfunction "P_1") (pintype "passive"))
    )
    (net (code "255") (name "unconnected-(PAD145-P-Pad1)") (class "Default")
      (node (ref "PAD145") (pin "1") (pinfunction "P_1") (pintype "passive"))
    )
    (net (code "256") (name "unconnected-(PAD146-P-Pad1)") (class "Default")
      (node (ref "PAD146") (pin "1") (pinfunction "P_1") (pintype "passive"))
    )
    (net (code "257") (name "unconnected-(PAD147-P-Pad1)") (class "Default")
      (node (ref "PAD147") (pin "1") (pinfunction "P_1") (pintype "passive"))
    )
    (net (code "258") (name "unconnected-(PAD148-P-Pad1)") (class "Default")
      (node (ref "PAD148") (pin "1") (pinfunction "P_1") (pintype "passive"))
    )
    (net (code "259") (name "unconnected-(PAD149-P-Pad1)") (class "Default")
      (node (ref "PAD149") (pin "1") (pinfunction "P_1") (pintype "passive"))
    )
    (net (code "260") (name "unconnected-(PAD150-P-Pad1)") (class "Default")
      (node (ref "PAD150") (pin "1") (pinfunction "P_1") (pintype "passive"))
    )
    (net (code "261") (name "unconnected-(PAD151-P-Pad1)") (class "Default")
      (node (ref "PAD151") (pin "1") (pinfunction "P_1") (pintype "passive"))
    )
    (net (code "262") (name "unconnected-(PAD152-P-Pad1)") (class "Default")
      (node (ref "PAD152") (pin "1") (pinfunction "P_1") (pintype "passive"))
    )
    (net (code "263") (name "unconnected-(PAD153-P-Pad1)") (class "Default")
      (node (ref "PAD153") (pin "1") (pinfunction "P_1") (pintype "passive"))
    )
    (net (code "264") (name "unconnected-(PAD154-P-Pad1)") (class "Default")
      (node (ref "PAD154") (pin "1") (pinfunction "P_1") (pintype "passive"))
    )
    (net (code "265") (name "unconnected-(PAD155-P-Pad1)") (class "Default")
      (node (ref "PAD155") (pin "1") (pinfunction "P_1") (pintype "passive"))
    )
    (net (code "266") (name "unconnected-(PAD156-P-Pad1)") (class "Default")
      (node (ref "PAD156") (pin "1") (pinfunction "P_1") (pintype "passive"))
    )
    (net (code "267") (name "unconnected-(PAD157-P-Pad1)") (class "Default")
      (node (ref "PAD157") (pin "1") (pinfunction "P_1") (pintype "passive"))
    )
    (net (code "268") (name "unconnected-(PAD158-P-Pad1)") (class "Default")
      (node (ref "PAD158") (pin "1") (pinfunction "P_1") (pintype "passive"))
    )
    (net (code "269") (name "unconnected-(PAD159-P-Pad1)") (class "Default")
      (node (ref "PAD159") (pin "1") (pinfunction "P_1") (pintype "passive"))
    )
    (net (code "270") (name "unconnected-(PAD160-P-Pad1)") (class "Default")
      (node (ref "PAD160") (pin "1") (pinfunction "P_1") (pintype "passive"))
    )
    (net (code "271") (name "unconnected-(PAD161-P-Pad1)") (class "Default")
      (node (ref "PAD161") (pin "1") (pinfunction "P_1") (pintype "passive"))
    )
    (net (code "272") (name "unconnected-(PAD162-P-Pad1)") (class "Default")
      (node (ref "PAD162") (pin "1") (pinfunction "P_1") (pintype "passive"))
    )
    (net (code "273") (name "unconnected-(PAD163-P-Pad1)") (class "Default")
      (node (ref "PAD163") (pin "1") (pinfunction "P_1") (pintype "passive"))
    )
    (net (code "274") (name "unconnected-(PAD164-P-Pad1)") (class "Default")
      (node (ref "PAD164") (pin "1") (pinfunction "P_1") (pintype "passive"))
    )
    (net (code "275") (name "unconnected-(PAD165-P-Pad1)") (class "Default")
      (node (ref "PAD165") (pin "1") (pinfunction "P_1") (pintype "passive"))
    )
    (net (code "276") (name "unconnected-(PAD166-P-Pad1)") (class "Default")
      (node (ref "PAD166") (pin "1") (pinfunction "P_1") (pintype "passive"))
    )
    (net (code "277") (name "unconnected-(PAD167-P-Pad1)") (class "Default")
      (node (ref "PAD167") (pin "1") (pinfunction "P_1") (pintype "passive"))
    )
    (net (code "278") (name "unconnected-(PAD168-P-Pad1)") (class "Default")
      (node (ref "PAD168") (pin "1") (pinfunction "P_1") (pintype "passive"))
    )
    (net (code "279") (name "unconnected-(PAD169-P-Pad1)") (class "Default")
      (node (ref "PAD169") (pin "1") (pinfunction "P_1") (pintype "passive"))
    )
    (net (code "280") (name "unconnected-(PAD170-P-Pad1)") (class "Default")
      (node (ref "PAD170") (pin "1") (pinfunction "P_1") (pintype "passive"))
    )
    (net (code "281") (name "unconnected-(PAD171-P-Pad1)") (class "Default")
      (node (ref "PAD171") (pin "1") (pinfunction "P_1") (pintype "passive"))
    )
    (net (code "282") (name "unconnected-(PAD172-P-Pad1)") (class "Default")
      (node (ref "PAD172") (pin "1") (pinfunction "P_1") (pintype "passive"))
    )
    (net (code "283") (name "unconnected-(PAD173-P-Pad1)") (class "Default")
      (node (ref "PAD173") (pin "1") (pinfunction "P_1") (pintype "passive"))
    )
    (net (code "284") (name "unconnected-(PAD174-P-Pad1)") (class "Default")
      (node (ref "PAD174") (pin "1") (pinfunction "P_1") (pintype "passive"))
    )
    (net (code "285") (name "unconnected-(PAD175-P-Pad1)") (class "Default")
      (node (ref "PAD175") (pin "1") (pinfunction "P_1") (pintype "passive"))
    )
    (net (code "286") (name "unconnected-(PAD176-P-Pad1)") (class "Default")
      (node (ref "PAD176") (pin "1") (pinfunction "P_1") (pintype "passive"))
    )
    (net (code "287") (name "unconnected-(PAD177-P-Pad1)") (class "Default")
      (node (ref "PAD177") (pin "1") (pinfunction "P_1") (pintype "passive"))
    )
    (net (code "288") (name "unconnected-(PAD178-P-Pad1)") (class "Default")
      (node (ref "PAD178") (pin "1") (pinfunction "P_1") (pintype "passive"))
    )
    (net (code "289") (name "unconnected-(PAD179-P-Pad1)") (class "Default")
      (node (ref "PAD179") (pin "1") (pinfunction "P_1") (pintype "passive"))
    )
    (net (code "290") (name "unconnected-(PAD180-P-Pad1)") (class "Default")
      (node (ref "PAD180") (pin "1") (pinfunction "P_1") (pintype "passive"))
    )
    (net (code "291") (name "unconnected-(PAD181-P-Pad1)") (class "Default")
      (node (ref "PAD181") (pin "1") (pinfunction "P_1") (pintype "passive"))
    )
    (net (code "292") (name "unconnected-(PAD182-P-Pad1)") (class "Default")
      (node (ref "PAD182") (pin "1") (pinfunction "P_1") (pintype "passive"))
    )
    (net (code "293") (name "unconnected-(PAD183-P-Pad1)") (class "Default")
      (node (ref "PAD183") (pin "1") (pinfunction "P_1") (pintype "passive"))
    )
    (net (code "294") (name "unconnected-(PAD184-P-Pad1)") (class "Default")
      (node (ref "PAD184") (pin "1") (pinfunction "P_1") (pintype "passive"))
    )
    (net (code "295") (name "unconnected-(PAD185-P-Pad1)") (class "Default")
      (node (ref "PAD185") (pin "1") (pinfunction "P_1") (pintype "passive"))
    )
    (net (code "296") (name "unconnected-(PAD186-P-Pad1)") (class "Default")
      (node (ref "PAD186") (pin "1") (pinfunction "P_1") (pintype "passive"))
    )
    (net (code "297") (name "unconnected-(PAD187-P-Pad1)") (class "Default")
      (node (ref "PAD187") (pin "1") (pinfunction "P_1") (pintype "passive"))
    )
    (net (code "298") (name "unconnected-(PAD188-P-Pad1)") (class "Default")
      (node (ref "PAD188") (pin "1") (pinfunction "P_1") (pintype "passive"))
    )
    (net (code "299") (name "unconnected-(PAD189-P-Pad1)") (class "Default")
      (node (ref "PAD189") (pin "1") (pinfunction "P_1") (pintype "passive"))
    )
    (net (code "300") (name "unconnected-(PAD190-P-Pad1)") (class "Default")
      (node (ref "PAD190") (pin "1") (pinfunction "P_1") (pintype "passive"))
    )
    (net (code "301") (name "unconnected-(PAD191-P-Pad1)") (class "Default")
      (node (ref "PAD191") (pin "1") (pinfunction "P_1") (pintype "passive"))
    )
    (net (code "302") (name "unconnected-(PAD192-P-Pad1)") (class "Default")
      (node (ref "PAD192") (pin "1") (pinfunction "P_1") (pintype "passive"))
    )
    (net (code "303") (name "unconnected-(PAD193-P-Pad1)") (class "Default")
      (node (ref "PAD193") (pin "1") (pinfunction "P_1") (pintype "passive"))
    )
    (net (code "304") (name "unconnected-(PAD194-P-Pad1)") (class "Default")
      (node (ref "PAD194") (pin "1") (pinfunction "P_1") (pintype "passive"))
    )
    (net (code "305") (name "unconnected-(PAD195-P-Pad1)") (class "Default")
      (node (ref "PAD195") (pin "1") (pinfunction "P_1") (pintype "passive"))
    )
    (net (code "306") (name "unconnected-(PAD196-P-Pad1)") (class "Default")
      (node (ref "PAD196") (pin "1") (pinfunction "P_1") (pintype "passive"))
    )
    (net (code "307") (name "unconnected-(PAD197-P-Pad1)") (class "Default")
      (node (ref "PAD197") (pin "1") (pinfunction "P_1") (pintype "passive"))
    )
    (net (code "308") (name "unconnected-(PAD198-P-Pad1)") (class "Default")
      (node (ref "PAD198") (pin "1") (pinfunction "P_1") (pintype "passive"))
    )
    (net (code "309") (name "unconnected-(PAD199-P-Pad1)") (class "Default")
      (node (ref "PAD199") (pin "1") (pinfunction "P_1") (pintype "passive"))
    )
    (net (code "310") (name "unconnected-(PAD200-P-Pad1)") (class "Default")
      (node (ref "PAD200") (pin "1") (pinfunction "P_1") (pintype "passive"))
    )
    (net (code "311") (name "unconnected-(PAD201-P-Pad1)") (class "Default")
      (node (ref "PAD201") (pin "1") (pinfunction "P_1") (pintype "passive"))
    )
    (net (code "312") (name "unconnected-(PAD202-P-Pad1)") (class "Default")
      (node (ref "PAD202") (pin "1") (pinfunction "P_1") (pintype "passive"))
    )
    (net (code "313") (name "unconnected-(PAD203-P-Pad1)") (class "Default")
      (node (ref "PAD203") (pin "1") (pinfunction "P_1") (pintype "passive"))
    )
    (net (code "314") (name "unconnected-(PAD204-P-Pad1)") (class "Default")
      (node (ref "PAD204") (pin "1") (pinfunction "P_1") (pintype "passive"))
    )
    (net (code "315") (name "unconnected-(PAD205-P-Pad1)") (class "Default")
      (node (ref "PAD205") (pin "1") (pinfunction "P_1") (pintype "passive"))
    )
    (net (code "316") (name "unconnected-(PAD206-P-Pad1)") (class "Default")
      (node (ref "PAD206") (pin "1") (pinfunction "P_1") (pintype "passive"))
    )
    (net (code "317") (name "unconnected-(PAD207-P-Pad1)") (class "Default")
      (node (ref "PAD207") (pin "1") (pinfunction "P_1") (pintype "passive"))
    )
    (net (code "318") (name "unconnected-(PAD208-P-Pad1)") (class "Default")
      (node (ref "PAD208") (pin "1") (pinfunction "P_1") (pintype "passive"))
    )
    (net (code "319") (name "unconnected-(PAD209-P-Pad1)") (class "Default")
      (node (ref "PAD209") (pin "1") (pinfunction "P_1") (pintype "passive"))
    )
    (net (code "320") (name "unconnected-(PAD210-P-Pad1)") (class "Default")
      (node (ref "PAD210") (pin "1") (pinfunction "P_1") (pintype "passive"))
    )
    (net (code "321") (name "unconnected-(PAD211-P-Pad1)") (class "Default")
      (node (ref "PAD211") (pin "1") (pinfunction "P_1") (pintype "passive"))
    )
    (net (code "322") (name "unconnected-(PAD212-P-Pad1)") (class "Default")
      (node (ref "PAD212") (pin "1") (pinfunction "P_1") (pintype "passive"))
    )
    (net (code "323") (name "unconnected-(PAD213-P-Pad1)") (class "Default")
      (node (ref "PAD213") (pin "1") (pinfunction "P_1") (pintype "passive"))
    )
    (net (code "324") (name "unconnected-(PAD214-P-Pad1)") (class "Default")
      (node (ref "PAD214") (pin "1") (pinfunction "P_1") (pintype "passive"))
    )
    (net (code "325") (name "unconnected-(PAD215-P-Pad1)") (class "Default")
      (node (ref "PAD215") (pin "1") (pinfunction "P_1") (pintype "passive"))
    )
    (net (code "326") (name "unconnected-(PAD216-P-Pad1)") (class "Default")
      (node (ref "PAD216") (pin "1") (pinfunction "P_1") (pintype "passive"))
    )
    (net (code "327") (name "unconnected-(PAD217-P-Pad1)") (class "Default")
      (node (ref "PAD217") (pin "1") (pinfunction "P_1") (pintype "passive"))
    )
    (net (code "328") (name "unconnected-(PAD218-P-Pad1)") (class "Default")
      (node (ref "PAD218") (pin "1") (pinfunction "P_1") (pintype "passive"))
    )
    (net (code "329") (name "unconnected-(PAD219-P-Pad1)") (class "Default")
      (node (ref "PAD219") (pin "1") (pinfunction "P_1") (pintype "passive"))
    )
    (net (code "330") (name "unconnected-(PAD220-P-Pad1)") (class "Default")
      (node (ref "PAD220") (pin "1") (pinfunction "P_1") (pintype "passive"))
    )
    (net (code "331") (name "unconnected-(PAD221-P-Pad1)") (class "Default")
      (node (ref "PAD221") (pin "1") (pinfunction "P_1") (pintype "passive"))
    )
    (net (code "332") (name "unconnected-(PAD222-P-Pad1)") (class "Default")
      (node (ref "PAD222") (pin "1") (pinfunction "P_1") (pintype "passive"))
    )
    (net (code "333") (name "unconnected-(PAD223-P-Pad1)") (class "Default")
      (node (ref "PAD223") (pin "1") (pinfunction "P_1") (pintype "passive"))
    )
    (net (code "334") (name "unconnected-(PAD224-P-Pad1)") (class "Default")
      (node (ref "PAD224") (pin "1") (pinfunction "P_1") (pintype "passive"))
    )
    (net (code "335") (name "unconnected-(PAD225-P-Pad1)") (class "Default")
      (node (ref "PAD225") (pin "1") (pinfunction "P_1") (pintype "passive"))
    )
    (net (code "336") (name "unconnected-(PAD226-P-Pad1)") (class "Default")
      (node (ref "PAD226") (pin "1") (pinfunction "P_1") (pintype "passive"))
    )
    (net (code "337") (name "unconnected-(PAD227-P-Pad1)") (class "Default")
      (node (ref "PAD227") (pin "1") (pinfunction "P_1") (pintype "passive"))
    )
    (net (code "338") (name "unconnected-(PAD228-P-Pad1)") (class "Default")
      (node (ref "PAD228") (pin "1") (pinfunction "P_1") (pintype "passive"))
    )
    (net (code "339") (name "unconnected-(PAD229-P-Pad1)") (class "Default")
      (node (ref "PAD229") (pin "1") (pinfunction "P_1") (pintype "passive"))
    )
    (net (code "340") (name "unconnected-(PAD230-P-Pad1)") (class "Default")
      (node (ref "PAD230") (pin "1") (pinfunction "P_1") (pintype "passive"))
    )
    (net (code "341") (name "unconnected-(PAD231-P-Pad1)") (class "Default")
      (node (ref "PAD231") (pin "1") (pinfunction "P_1") (pintype "passive"))
    )
    (net (code "342") (name "unconnected-(PAD232-P-Pad1)") (class "Default")
      (node (ref "PAD232") (pin "1") (pinfunction "P_1") (pintype "passive"))
    )
    (net (code "343") (name "unconnected-(PAD233-P-Pad1)") (class "Default")
      (node (ref "PAD233") (pin "1") (pinfunction "P_1") (pintype "passive"))
    )
    (net (code "344") (name "unconnected-(PAD234-P-Pad1)") (class "Default")
      (node (ref "PAD234") (pin "1") (pinfunction "P_1") (pintype "passive"))
    )
    (net (code "345") (name "unconnected-(PAD235-P-Pad1)") (class "Default")
      (node (ref "PAD235") (pin "1") (pinfunction "P_1") (pintype "passive"))
    )
    (net (code "346") (name "unconnected-(PAD236-P-Pad1)") (class "Default")
      (node (ref "PAD236") (pin "1") (pinfunction "P_1") (pintype "passive"))
    )
    (net (code "347") (name "unconnected-(PAD237-P-Pad1)") (class "Default")
      (node (ref "PAD237") (pin "1") (pinfunction "P_1") (pintype "passive"))
    )
    (net (code "348") (name "unconnected-(PAD238-P-Pad1)") (class "Default")
      (node (ref "PAD238") (pin "1") (pinfunction "P_1") (pintype "passive"))
    )
    (net (code "349") (name "unconnected-(PAD239-P-Pad1)") (class "Default")
      (node (ref "PAD239") (pin "1") (pinfunction "P_1") (pintype "passive"))
    )
    (net (code "350") (name "unconnected-(PAD240-P-Pad1)") (class "Default")
      (node (ref "PAD240") (pin "1") (pinfunction "P_1") (pintype "passive"))
    )
    (net (code "351") (name "unconnected-(PAD241-P-Pad1)") (class "Default")
      (node (ref "PAD241") (pin "1") (pinfunction "P_1") (pintype "passive"))
    )
    (net (code "352") (name "unconnected-(PAD242-P-Pad1)") (class "Default")
      (node (ref "PAD242") (pin "1") (pinfunction "P_1") (pintype "passive"))
    )
    (net (code "353") (name "unconnected-(PAD243-P-Pad1)") (class "Default")
      (node (ref "PAD243") (pin "1") (pinfunction "P_1") (pintype "passive"))
    )
    (net (code "354") (name "unconnected-(PAD244-P-Pad1)") (class "Default")
      (node (ref "PAD244") (pin "1") (pinfunction "P_1") (pintype "passive"))
    )
    (net (code "355") (name "unconnected-(PAD245-P-Pad1)") (class "Default")
      (node (ref "PAD245") (pin "1") (pinfunction "P_1") (pintype "passive"))
    )
    (net (code "356") (name "unconnected-(PAD246-P-Pad1)") (class "Default")
      (node (ref "PAD246") (pin "1") (pinfunction "P_1") (pintype "passive"))
    )
    (net (code "357") (name "unconnected-(PAD247-P-Pad1)") (class "Default")
      (node (ref "PAD247") (pin "1") (pinfunction "P_1") (pintype "passive"))
    )
    (net (code "358") (name "unconnected-(PAD248-P-Pad1)") (class "Default")
      (node (ref "PAD248") (pin "1") (pinfunction "P_1") (pintype "passive"))
    )
    (net (code "359") (name "unconnected-(PAD249-P-Pad1)") (class "Default")
      (node (ref "PAD249") (pin "1") (pinfunction "P_1") (pintype "passive"))
    )
    (net (code "360") (name "unconnected-(PAD250-P-Pad1)") (class "Default")
      (node (ref "PAD250") (pin "1") (pinfunction "P_1") (pintype "passive"))
    )
    (net (code "361") (name "unconnected-(PAD251-P-Pad1)") (class "Default")
      (node (ref "PAD251") (pin "1") (pinfunction "P_1") (pintype "passive"))
    )
    (net (code "362") (name "unconnected-(PAD252-P-Pad1)") (class "Default")
      (node (ref "PAD252") (pin "1") (pinfunction "P_1") (pintype "passive"))
    )
    (net (code "363") (name "unconnected-(PAD253-P-Pad1)") (class "Default")
      (node (ref "PAD253") (pin "1") (pinfunction "P_1") (pintype "passive"))
    )
    (net (code "364") (name "unconnected-(PAD254-P-Pad1)") (class "Default")
      (node (ref "PAD254") (pin "1") (pinfunction "P_1") (pintype "passive"))
    )
    (net (code "365") (name "unconnected-(PAD255-P-Pad1)") (class "Default")
      (node (ref "PAD255") (pin "1") (pinfunction "P_1") (pintype "passive"))
    )
    (net (code "366") (name "unconnected-(PAD256-P-Pad1)") (class "Default")
      (node (ref "PAD256") (pin "1") (pinfunction "P_1") (pintype "passive"))
    )
    (net (code "367") (name "unconnected-(PAD257-P-Pad1)") (class "Default")
      (node (ref "PAD257") (pin "1") (pinfunction "P_1") (pintype "passive"))
    )
    (net (code "368") (name "unconnected-(PAD258-P-Pad1)") (class "Default")
      (node (ref "PAD258") (pin "1") (pinfunction "P_1") (pintype "passive"))
    )
    (net (code "369") (name "unconnected-(PAD259-P-Pad1)") (class "Default")
      (node (ref "PAD259") (pin "1") (pinfunction "P_1") (pintype "passive"))
    )
    (net (code "370") (name "unconnected-(PAD260-P-Pad1)") (class "Default")
      (node (ref "PAD260") (pin "1") (pinfunction "P_1") (pintype "passive"))
    )
    (net (code "371") (name "unconnected-(PAD261-P-Pad1)") (class "Default")
      (node (ref "PAD261") (pin "1") (pinfunction "P_1") (pintype "passive"))
    )
    (net (code "372") (name "unconnected-(PAD262-P-Pad1)") (class "Default")
      (node (ref "PAD262") (pin "1") (pinfunction "P_1") (pintype "passive"))
    )
    (net (code "373") (name "unconnected-(PAD263-P-Pad1)") (class "Default")
      (node (ref "PAD263") (pin "1") (pinfunction "P_1") (pintype "passive"))
    )
    (net (code "374") (name "unconnected-(PAD264-P-Pad1)") (class "Default")
      (node (ref "PAD264") (pin "1") (pinfunction "P_1") (pintype "passive"))
    )
    (net (code "375") (name "unconnected-(PAD265-P-Pad1)") (class "Default")
      (node (ref "PAD265") (pin "1") (pinfunction "P_1") (pintype "passive"))
    )
    (net (code "376") (name "unconnected-(PAD266-P-Pad1)") (class "Default")
      (node (ref "PAD266") (pin "1") (pinfunction "P_1") (pintype "passive"))
    )
    (net (code "377") (name "unconnected-(PAD267-P-Pad1)") (class "Default")
      (node (ref "PAD267") (pin "1") (pinfunction "P_1") (pintype "passive"))
    )
    (net (code "378") (name "unconnected-(PAD268-P-Pad1)") (class "Default")
      (node (ref "PAD268") (pin "1") (pinfunction "P_1") (pintype "passive"))
    )
    (net (code "379") (name "unconnected-(PAD269-P-Pad1)") (class "Default")
      (node (ref "PAD269") (pin "1") (pinfunction "P_1") (pintype "passive"))
    )
    (net (code "380") (name "unconnected-(PAD270-P-Pad1)") (class "Default")
      (node (ref "PAD270") (pin "1") (pinfunction "P_1") (pintype "passive"))
    )
    (net (code "381") (name "unconnected-(PAD271-P-Pad1)") (class "Default")
      (node (ref "PAD271") (pin "1") (pinfunction "P_1") (pintype "passive"))
    )
    (net (code "382") (name "unconnected-(PAD272-P-Pad1)") (class "Default")
      (node (ref "PAD272") (pin "1") (pinfunction "P_1") (pintype "passive"))
    )
    (net (code "383") (name "unconnected-(PAD273-P-Pad1)") (class "Default")
      (node (ref "PAD273") (pin "1") (pinfunction "P_1") (pintype "passive"))
    )
    (net (code "384") (name "unconnected-(PAD274-P-Pad1)") (class "Default")
      (node (ref "PAD274") (pin "1") (pinfunction "P_1") (pintype "passive"))
    )
    (net (code "385") (name "unconnected-(PAD275-P-Pad1)") (class "Default")
      (node (ref "PAD275") (pin "1") (pinfunction "P_1") (pintype "passive"))
    )
    (net (code "386") (name "unconnected-(PAD276-P-Pad1)") (class "Default")
      (node (ref "PAD276") (pin "1") (pinfunction "P_1") (pintype "passive"))
    )
    (net (code "387") (name "unconnected-(PAD277-P-Pad1)") (class "Default")
      (node (ref "PAD277") (pin "1") (pinfunction "P_1") (pintype "passive"))
    )
    (net (code "388") (name "unconnected-(PAD278-P-Pad1)") (class "Default")
      (node (ref "PAD278") (pin "1") (pinfunction "P_1") (pintype "passive"))
    )
    (net (code "389") (name "unconnected-(PAD279-P-Pad1)") (class "Default")
      (node (ref "PAD279") (pin "1") (pinfunction "P_1") (pintype "passive"))
    )
    (net (code "390") (name "unconnected-(PAD280-P-Pad1)") (class "Default")
      (node (ref "PAD280") (pin "1") (pinfunction "P_1") (pintype "passive"))
    )
    (net (code "391") (name "unconnected-(PAD281-P-Pad1)") (class "Default")
      (node (ref "PAD281") (pin "1") (pinfunction "P_1") (pintype "passive"))
    )
    (net (code "392") (name "unconnected-(PAD282-P-Pad1)") (class "Default")
      (node (ref "PAD282") (pin "1") (pinfunction "P_1") (pintype "passive"))
    )
    (net (code "393") (name "unconnected-(PAD283-P-Pad1)") (class "Default")
      (node (ref "PAD283") (pin "1") (pinfunction "P_1") (pintype "passive"))
    )
    (net (code "394") (name "unconnected-(PAD284-P-Pad1)") (class "Default")
      (node (ref "PAD284") (pin "1") (pinfunction "P_1") (pintype "passive"))
    )
    (net (code "395") (name "unconnected-(PAD285-P-Pad1)") (class "Default")
      (node (ref "PAD285") (pin "1") (pinfunction "P_1") (pintype "passive"))
    )
    (net (code "396") (name "unconnected-(PAD286-P-Pad1)") (class "Default")
      (node (ref "PAD286") (pin "1") (pinfunction "P_1") (pintype "passive"))
    )
    (net (code "397") (name "unconnected-(PAD287-P-Pad1)") (class "Default")
      (node (ref "PAD287") (pin "1") (pinfunction "P_1") (pintype "passive"))
    )
    (net (code "398") (name "unconnected-(PAD288-P-Pad1)") (class "Default")
      (node (ref "PAD288") (pin "1") (pinfunction "P_1") (pintype "passive"))
    )
    (net (code "399") (name "unconnected-(PAD289-P-Pad1)") (class "Default")
      (node (ref "PAD289") (pin "1") (pinfunction "P_1") (pintype "passive"))
    )
    (net (code "400") (name "unconnected-(PAD290-P-Pad1)") (class "Default")
      (node (ref "PAD290") (pin "1") (pinfunction "P_1") (pintype "passive"))
    )
    (net (code "401") (name "unconnected-(PAD291-P-Pad1)") (class "Default")
      (node (ref "PAD291") (pin "1") (pinfunction "P_1") (pintype "passive"))
    )
    (net (code "402") (name "unconnected-(PAD292-P-Pad1)") (class "Default")
      (node (ref "PAD292") (pin "1") (pinfunction "P_1") (pintype "passive"))
    )
    (net (code "403") (name "unconnected-(PAD293-P-Pad1)") (class "Default")
      (node (ref "PAD293") (pin "1") (pinfunction "P_1") (pintype "passive"))
    )
    (net (code "404") (name "unconnected-(PAD294-P-Pad1)") (class "Default")
      (node (ref "PAD294") (pin "1") (pinfunction "P_1") (pintype "passive"))
    )
    (net (code "405") (name "unconnected-(PAD295-P-Pad1)") (class "Default")
      (node (ref "PAD295") (pin "1") (pinfunction "P_1") (pintype "passive"))
    )
    (net (code "406") (name "unconnected-(PAD296-P-Pad1)") (class "Default")
      (node (ref "PAD296") (pin "1") (pinfunction "P_1") (pintype "passive"))
    )
    (net (code "407") (name "unconnected-(PAD297-P-Pad1)") (class "Default")
      (node (ref "PAD297") (pin "1") (pinfunction "P_1") (pintype "passive"))
    )
    (net (code "408") (name "unconnected-(PAD298-P-Pad1)") (class "Default")
      (node (ref "PAD298") (pin "1") (pinfunction "P_1") (pintype "passive"))
    )
    (net (code "409") (name "unconnected-(PAD299-P-Pad1)") (class "Default")
      (node (ref "PAD299") (pin "1") (pinfunction "P_1") (pintype "passive"))
    )
    (net (code "410") (name "unconnected-(PAD300-P-Pad1)") (class "Default")
      (node (ref "PAD300") (pin "1") (pinfunction "P_1") (pintype "passive"))
    )
    (net (code "411") (name "unconnected-(PAD301-P-Pad1)") (class "Default")
      (node (ref "PAD301") (pin "1") (pinfunction "P_1") (pintype "passive"))
    )
    (net (code "412") (name "unconnected-(PAD302-P-Pad1)") (class "Default")
      (node (ref "PAD302") (pin "1") (pinfunction "P_1") (pintype "passive"))
    )
    (net (code "413") (name "unconnected-(PAD303-P-Pad1)") (class "Default")
      (node (ref "PAD303") (pin "1") (pinfunction "P_1") (pintype "passive"))
    )
    (net (code "414") (name "unconnected-(PAD304-P-Pad1)") (class "Default")
      (node (ref "PAD304") (pin "1") (pinfunction "P_1") (pintype "passive"))
    )
    (net (code "415") (name "unconnected-(PAD305-P-Pad1)") (class "Default")
      (node (ref "PAD305") (pin "1") (pinfunction "P_1") (pintype "passive"))
    )
    (net (code "416") (name "unconnected-(PAD306-P-Pad1)") (class "Default")
      (node (ref "PAD306") (pin "1") (pinfunction "P_1") (pintype "passive"))
    )
    (net (code "417") (name "unconnected-(PAD307-P-Pad1)") (class "Default")
      (node (ref "PAD307") (pin "1") (pinfunction "P_1") (pintype "passive"))
    )
    (net (code "418") (name "unconnected-(PAD308-P-Pad1)") (class "Default")
      (node (ref "PAD308") (pin "1") (pinfunction "P_1") (pintype "passive"))
    )
    (net (code "419") (name "unconnected-(PAD309-P-Pad1)") (class "Default")
      (node (ref "PAD309") (pin "1") (pinfunction "P_1") (pintype "passive"))
    )
    (net (code "420") (name "unconnected-(PAD310-P-Pad1)") (class "Default")
      (node (ref "PAD310") (pin "1") (pinfunction "P_1") (pintype "passive"))
    )
    (net (code "421") (name "unconnected-(PAD311-P-Pad1)") (class "Default")
      (node (ref "PAD311") (pin "1") (pinfunction "P_1") (pintype "passive"))
    )
    (net (code "422") (name "unconnected-(PAD312-P-Pad1)") (class "Default")
      (node (ref "PAD312") (pin "1") (pinfunction "P_1") (pintype "passive"))
    )
    (net (code "423") (name "unconnected-(PAD313-P-Pad1)") (class "Default")
      (node (ref "PAD313") (pin "1") (pinfunction "P_1") (pintype "passive"))
    )
    (net (code "424") (name "unconnected-(PAD314-P-Pad1)") (class "Default")
      (node (ref "PAD314") (pin "1") (pinfunction "P_1") (pintype "passive"))
    )
    (net (code "425") (name "unconnected-(PAD315-P-Pad1)") (class "Default")
      (node (ref "PAD315") (pin "1") (pinfunction "P_1") (pintype "passive"))
    )
    (net (code "426") (name "unconnected-(PAD316-P-Pad1)") (class "Default")
      (node (ref "PAD316") (pin "1") (pinfunction "P_1") (pintype "passive"))
    )
    (net (code "427") (name "unconnected-(PAD317-P-Pad1)") (class "Default")
      (node (ref "PAD317") (pin "1") (pinfunction "P_1") (pintype "passive"))
    )
    (net (code "428") (name "unconnected-(PAD318-P-Pad1)") (class "Default")
      (node (ref "PAD318") (pin "1") (pinfunction "P_1") (pintype "passive"))
    )
    (net (code "429") (name "unconnected-(PAD319-P-Pad1)") (class "Default")
      (node (ref "PAD319") (pin "1") (pinfunction "P_1") (pintype "passive"))
    )
    (net (code "430") (name "unconnected-(PAD320-P-Pad1)") (class "Default")
      (node (ref "PAD320") (pin "1") (pinfunction "P_1") (pintype "passive"))
    )
    (net (code "431") (name "unconnected-(PAD321-P-Pad1)") (class "Default")
      (node (ref "PAD321") (pin "1") (pinfunction "P_1") (pintype "passive"))
    )
    (net (code "432") (name "unconnected-(PAD322-P-Pad1)") (class "Default")
      (node (ref "PAD322") (pin "1") (pinfunction "P_1") (pintype "passive"))
    )
    (net (code "433") (name "unconnected-(PAD323-P-Pad1)") (class "Default")
      (node (ref "PAD323") (pin "1") (pinfunction "P_1") (pintype "passive"))
    )
    (net (code "434") (name "unconnected-(PAD324-P-Pad1)") (class "Default")
      (node (ref "PAD324") (pin "1") (pinfunction "P_1") (pintype "passive"))
    )
    (net (code "435") (name "unconnected-(PAD325-P-Pad1)") (class "Default")
      (node (ref "PAD325") (pin "1") (pinfunction "P_1") (pintype "passive"))
    )
    (net (code "436") (name "unconnected-(PAD326-P-Pad1)") (class "Default")
      (node (ref "PAD326") (pin "1") (pinfunction "P_1") (pintype "passive"))
    )
    (net (code "437") (name "unconnected-(PAD327-P-Pad1)") (class "Default")
      (node (ref "PAD327") (pin "1") (pinfunction "P_1") (pintype "passive"))
    )
    (net (code "438") (name "unconnected-(PAD328-P-Pad1)") (class "Default")
      (node (ref "PAD328") (pin "1") (pinfunction "P_1") (pintype "passive"))
    )
    (net (code "439") (name "unconnected-(PAD329-P-Pad1)") (class "Default")
      (node (ref "PAD329") (pin "1") (pinfunction "P_1") (pintype "passive"))
    )
    (net (code "440") (name "unconnected-(PAD330-P-Pad1)") (class "Default")
      (node (ref "PAD330") (pin "1") (pinfunction "P_1") (pintype "passive"))
    )
    (net (code "441") (name "unconnected-(PAD331-P-Pad1)") (class "Default")
      (node (ref "PAD331") (pin "1") (pinfunction "P_1") (pintype "passive"))
    )
    (net (code "442") (name "unconnected-(PAD332-P-Pad1)") (class "Default")
      (node (ref "PAD332") (pin "1") (pinfunction "P_1") (pintype "passive"))
    )
    (net (code "443") (name "unconnected-(PAD333-P-Pad1)") (class "Default")
      (node (ref "PAD333") (pin "1") (pinfunction "P_1") (pintype "passive"))
    )
    (net (code "444") (name "unconnected-(PAD334-P-Pad1)") (class "Default")
      (node (ref "PAD334") (pin "1") (pinfunction "P_1") (pintype "passive"))
    )
    (net (code "445") (name "unconnected-(PAD335-P-Pad1)") (class "Default")
      (node (ref "PAD335") (pin "1") (pinfunction "P_1") (pintype "passive"))
    )
    (net (code "446") (name "unconnected-(PAD336-P-Pad1)") (class "Default")
      (node (ref "PAD336") (pin "1") (pinfunction "P_1") (pintype "passive"))
    )
    (net (code "447") (name "unconnected-(PAD337-P-Pad1)") (class "Default")
      (node (ref "PAD337") (pin "1") (pinfunction "P_1") (pintype "passive"))
    )
    (net (code "448") (name "unconnected-(PAD338-P-Pad1)") (class "Default")
      (node (ref "PAD338") (pin "1") (pinfunction "P_1") (pintype "passive"))
    )
    (net (code "449") (name "unconnected-(PAD339-P-Pad1)") (class "Default")
      (node (ref "PAD339") (pin "1") (pinfunction "P_1") (pintype "passive"))
    )
    (net (code "450") (name "unconnected-(PAD340-P-Pad1)") (class "Default")
      (node (ref "PAD340") (pin "1") (pinfunction "P_1") (pintype "passive"))
    )
    (net (code "451") (name "unconnected-(PAD341-P-Pad1)") (class "Default")
      (node (ref "PAD341") (pin "1") (pinfunction "P_1") (pintype "passive"))
    )
    (net (code "452") (name "unconnected-(PAD342-P-Pad1)") (class "Default")
      (node (ref "PAD342") (pin "1") (pinfunction "P_1") (pintype "passive"))
    )
    (net (code "453") (name "unconnected-(PAD343-P-Pad1)") (class "Default")
      (node (ref "PAD343") (pin "1") (pinfunction "P_1") (pintype "passive"))
    )
    (net (code "454") (name "unconnected-(PAD344-P-Pad1)") (class "Default")
      (node (ref "PAD344") (pin "1") (pinfunction "P_1") (pintype "passive"))
    )
    (net (code "455") (name "unconnected-(PAD345-P-Pad1)") (class "Default")
      (node (ref "PAD345") (pin "1") (pinfunction "P_1") (pintype "passive"))
    )
    (net (code "456") (name "unconnected-(PAD346-P-Pad1)") (class "Default")
      (node (ref "PAD346") (pin "1") (pinfunction "P_1") (pintype "passive"))
    )
    (net (code "457") (name "unconnected-(PAD347-P-Pad1)") (class "Default")
      (node (ref "PAD347") (pin "1") (pinfunction "P_1") (pintype "passive"))
    )
    (net (code "458") (name "unconnected-(PAD348-P-Pad1)") (class "Default")
      (node (ref "PAD348") (pin "1") (pinfunction "P_1") (pintype "passive"))
    )
    (net (code "459") (name "unconnected-(PAD349-P-Pad1)") (class "Default")
      (node (ref "PAD349") (pin "1") (pinfunction "P_1") (pintype "passive"))
    )
    (net (code "460") (name "unconnected-(PAD350-P-Pad1)") (class "Default")
      (node (ref "PAD350") (pin "1") (pinfunction "P_1") (pintype "passive"))
    )
    (net (code "461") (name "unconnected-(PAD351-P-Pad1)") (class "Default")
      (node (ref "PAD351") (pin "1") (pinfunction "P_1") (pintype "passive"))
    )
    (net (code "462") (name "unconnected-(PAD352-P-Pad1)") (class "Default")
      (node (ref "PAD352") (pin "1") (pinfunction "P_1") (pintype "passive"))
    )
    (net (code "463") (name "unconnected-(PAD353-P-Pad1)") (class "Default")
      (node (ref "PAD353") (pin "1") (pinfunction "P_1") (pintype "passive"))
    )
    (net (code "464") (name "unconnected-(PAD354-P-Pad1)") (class "Default")
      (node (ref "PAD354") (pin "1") (pinfunction "P_1") (pintype "passive"))
    )
    (net (code "465") (name "unconnected-(PAD355-P-Pad1)") (class "Default")
      (node (ref "PAD355") (pin "1") (pinfunction "P_1") (pintype "passive"))
    )
    (net (code "466") (name "unconnected-(PAD356-P-Pad1)") (class "Default")
      (node (ref "PAD356") (pin "1") (pinfunction "P_1") (pintype "passive"))
    )
    (net (code "467") (name "unconnected-(PAD357-P-Pad1)") (class "Default")
      (node (ref "PAD357") (pin "1") (pinfunction "P_1") (pintype "passive"))
    )
    (net (code "468") (name "unconnected-(PAD358-P-Pad1)") (class "Default")
      (node (ref "PAD358") (pin "1") (pinfunction "P_1") (pintype "passive"))
    )
    (net (code "469") (name "unconnected-(PAD359-P-Pad1)") (class "Default")
      (node (ref "PAD359") (pin "1") (pinfunction "P_1") (pintype "passive"))
    )
    (net (code "470") (name "unconnected-(PAD360-P-Pad1)") (class "Default")
      (node (ref "PAD360") (pin "1") (pinfunction "P_1") (pintype "passive"))
    )
    (net (code "471") (name "unconnected-(PAD361-P-Pad1)") (class "Default")
      (node (ref "PAD361") (pin "1") (pinfunction "P_1") (pintype "passive"))
    )
    (net (code "472") (name "unconnected-(PAD362-P-Pad1)") (class "Default")
      (node (ref "PAD362") (pin "1") (pinfunction "P_1") (pintype "passive"))
    )
    (net (code "473") (name "unconnected-(PAD363-P-Pad1)") (class "Default")
      (node (ref "PAD363") (pin "1") (pinfunction "P_1") (pintype "passive"))
    )
    (net (code "474") (name "unconnected-(PAD364-P-Pad1)") (class "Default")
      (node (ref "PAD364") (pin "1") (pinfunction "P_1") (pintype "passive"))
    )
    (net (code "475") (name "unconnected-(PAD365-P-Pad1)") (class "Default")
      (node (ref "PAD365") (pin "1") (pinfunction "P_1") (pintype "passive"))
    )
    (net (code "476") (name "unconnected-(PAD366-P-Pad1)") (class "Default")
      (node (ref "PAD366") (pin "1") (pinfunction "P_1") (pintype "passive"))
    )
    (net (code "477") (name "unconnected-(PAD367-P-Pad1)") (class "Default")
      (node (ref "PAD367") (pin "1") (pinfunction "P_1") (pintype "passive"))
    )
    (net (code "478") (name "unconnected-(PAD368-P-Pad1)") (class "Default")
      (node (ref "PAD368") (pin "1") (pinfunction "P_1") (pintype "passive"))
    )
    (net (code "479") (name "unconnected-(PAD369-P-Pad1)") (class "Default")
      (node (ref "PAD369") (pin "1") (pinfunction "P_1") (pintype "passive"))
    )
    (net (code "480") (name "unconnected-(PAD370-P-Pad1)") (class "Default")
      (node (ref "PAD370") (pin "1") (pinfunction "P_1") (pintype "passive"))
    )
    (net (code "481") (name "unconnected-(PAD371-P-Pad1)") (class "Default")
      (node (ref "PAD371") (pin "1") (pinfunction "P_1") (pintype "passive"))
    )
    (net (code "482") (name "unconnected-(PAD372-P-Pad1)") (class "Default")
      (node (ref "PAD372") (pin "1") (pinfunction "P_1") (pintype "passive"))
    )
    (net (code "483") (name "unconnected-(PAD373-P-Pad1)") (class "Default")
      (node (ref "PAD373") (pin "1") (pinfunction "P_1") (pintype "passive"))
    )
    (net (code "484") (name "unconnected-(PAD374-P-Pad1)") (class "Default")
      (node (ref "PAD374") (pin "1") (pinfunction "P_1") (pintype "passive"))
    )
    (net (code "485") (name "unconnected-(PAD375-P-Pad1)") (class "Default")
      (node (ref "PAD375") (pin "1") (pinfunction "P_1") (pintype "passive"))
    )
    (net (code "486") (name "unconnected-(PAD376-P-Pad1)") (class "Default")
      (node (ref "PAD376") (pin "1") (pinfunction "P_1") (pintype "passive"))
    )
    (net (code "487") (name "unconnected-(PAD377-P-Pad1)") (class "Default")
      (node (ref "PAD377") (pin "1") (pinfunction "P_1") (pintype "passive"))
    )
    (net (code "488") (name "unconnected-(PAD378-P-Pad1)") (class "Default")
      (node (ref "PAD378") (pin "1") (pinfunction "P_1") (pintype "passive"))
    )
    (net (code "489") (name "unconnected-(PAD379-P-Pad1)") (class "Default")
      (node (ref "PAD379") (pin "1") (pinfunction "P_1") (pintype "passive"))
    )
    (net (code "490") (name "unconnected-(PAD380-P-Pad1)") (class "Default")
      (node (ref "PAD380") (pin "1") (pinfunction "P_1") (pintype "passive"))
    )
    (net (code "491") (name "unconnected-(PAD381-P-Pad1)") (class "Default")
      (node (ref "PAD381") (pin "1") (pinfunction "P_1") (pintype "passive"))
    )
    (net (code "492") (name "unconnected-(PAD382-P-Pad1)") (class "Default")
      (node (ref "PAD382") (pin "1") (pinfunction "P_1") (pintype "passive"))
    )
    (net (code "493") (name "unconnected-(PAD383-P-Pad1)") (class "Default")
      (node (ref "PAD383") (pin "1") (pinfunction "P_1") (pintype "passive"))
    )
    (net (code "494") (name "unconnected-(PAD384-P-Pad1)") (class "Default")
      (node (ref "PAD384") (pin "1") (pinfunction "P_1") (pintype "passive"))
    )
    (net (code "495") (name "unconnected-(PAD385-P-Pad1)") (class "Default")
      (node (ref "PAD385") (pin "1") (pinfunction "P_1") (pintype "passive"))
    )
    (net (code "496") (name "unconnected-(PAD386-P-Pad1)") (class "Default")
      (node (ref "PAD386") (pin "1") (pinfunction "P_1") (pintype "passive"))
    )
    (net (code "497") (name "unconnected-(PAD387-P-Pad1)") (class "Default")
      (node (ref "PAD387") (pin "1") (pinfunction "P_1") (pintype "passive"))
    )
    (net (code "498") (name "unconnected-(PAD388-P-Pad1)") (class "Default")
      (node (ref "PAD388") (pin "1") (pinfunction "P_1") (pintype "passive"))
    )
    (net (code "499") (name "unconnected-(PAD389-P-Pad1)") (class "Default")
      (node (ref "PAD389") (pin "1") (pinfunction "P_1") (pintype "passive"))
    )
    (net (code "500") (name "unconnected-(PAD390-P-Pad1)") (class "Default")
      (node (ref "PAD390") (pin "1") (pinfunction "P_1") (pintype "passive"))
    )
    (net (code "501") (name "unconnected-(PAD391-P-Pad1)") (class "Default")
      (node (ref "PAD391") (pin "1") (pinfunction "P_1") (pintype "passive"))
    )
    (net (code "502") (name "unconnected-(PAD392-P-Pad1)") (class "Default")
      (node (ref "PAD392") (pin "1") (pinfunction "P_1") (pintype "passive"))
    )
    (net (code "503") (name "unconnected-(PAD393-P-Pad1)") (class "Default")
      (node (ref "PAD393") (pin "1") (pinfunction "P_1") (pintype "passive"))
    )
    (net (code "504") (name "unconnected-(PAD394-P-Pad1)") (class "Default")
      (node (ref "PAD394") (pin "1") (pinfunction "P_1") (pintype "passive"))
    )
    (net (code "505") (name "unconnected-(PAD395-P-Pad1)") (class "Default")
      (node (ref "PAD395") (pin "1") (pinfunction "P_1") (pintype "passive"))
    )
    (net (code "506") (name "unconnected-(PAD396-P-Pad1)") (class "Default")
      (node (ref "PAD396") (pin "1") (pinfunction "P_1") (pintype "passive"))
    )
    (net (code "507") (name "unconnected-(PAD397-P-Pad1)") (class "Default")
      (node (ref "PAD397") (pin "1") (pinfunction "P_1") (pintype "passive"))
    )
    (net (code "508") (name "unconnected-(PAD398-P-Pad1)") (class "Default")
      (node (ref "PAD398") (pin "1") (pinfunction "P_1") (pintype "passive"))
    )
    (net (code "509") (name "unconnected-(PAD399-P-Pad1)") (class "Default")
      (node (ref "PAD399") (pin "1") (pinfunction "P_1") (pintype "passive"))
    )
    (net (code "510") (name "unconnected-(PAD400-P-Pad1)") (class "Default")
      (node (ref "PAD400") (pin "1") (pinfunction "P_1") (pintype "passive"))
    )
    (net (code "511") (name "unconnected-(PAD401-P-Pad1)") (class "Default")
      (node (ref "PAD401") (pin "1") (pinfunction "P_1") (pintype "passive"))
    )
    (net (code "512") (name "unconnected-(PAD402-P-Pad1)") (class "Default")
      (node (ref "PAD402") (pin "1") (pinfunction "P_1") (pintype "passive"))
    )
    (net (code "513") (name "unconnected-(PAD403-P-Pad1)") (class "Default")
      (node (ref "PAD403") (pin "1") (pinfunction "P_1") (pintype "passive"))
    )
    (net (code "514") (name "unconnected-(PAD404-P-Pad1)") (class "Default")
      (node (ref "PAD404") (pin "1") (pinfunction "P_1") (pintype "passive"))
    )
    (net (code "515") (name "unconnected-(PAD405-P-Pad1)") (class "Default")
      (node (ref "PAD405") (pin "1") (pinfunction "P_1") (pintype "passive"))
    )
    (net (code "516") (name "unconnected-(PAD406-P-Pad1)") (class "Default")
      (node (ref "PAD406") (pin "1") (pinfunction "P_1") (pintype "passive"))
    )
    (net (code "517") (name "unconnected-(PAD407-P-Pad1)") (class "Default")
      (node (ref "PAD407") (pin "1") (pinfunction "P_1") (pintype "passive"))
    )
    (net (code "518") (name "unconnected-(PAD408-P-Pad1)") (class "Default")
      (node (ref "PAD408") (pin "1") (pinfunction "P_1") (pintype "passive"))
    )
    (net (code "519") (name "unconnected-(PAD409-P-Pad1)") (class "Default")
      (node (ref "PAD409") (pin "1") (pinfunction "P_1") (pintype "passive"))
    )
    (net (code "520") (name "unconnected-(PAD410-P-Pad1)") (class "Default")
      (node (ref "PAD410") (pin "1") (pinfunction "P_1") (pintype "passive"))
    )
    (net (code "521") (name "unconnected-(PAD411-P-Pad1)") (class "Default")
      (node (ref "PAD411") (pin "1") (pinfunction "P_1") (pintype "passive"))
    )
    (net (code "522") (name "unconnected-(PAD412-P-Pad1)") (class "Default")
      (node (ref "PAD412") (pin "1") (pinfunction "P_1") (pintype "passive"))
    )
    (net (code "523") (name "unconnected-(PAD413-P-Pad1)") (class "Default")
      (node (ref "PAD413") (pin "1") (pinfunction "P_1") (pintype "passive"))
    )
    (net (code "524") (name "unconnected-(PAD414-P-Pad1)") (class "Default")
      (node (ref "PAD414") (pin "1") (pinfunction "P_1") (pintype "passive"))
    )
    (net (code "525") (name "unconnected-(PAD415-P-Pad1)") (class "Default")
      (node (ref "PAD415") (pin "1") (pinfunction "P_1") (pintype "passive"))
    )
    (net (code "526") (name "unconnected-(PAD416-P-Pad1)") (class "Default")
      (node (ref "PAD416") (pin "1") (pinfunction "P_1") (pintype "passive"))
    )
    (net (code "527") (name "unconnected-(PAD417-P-Pad1)") (class "Default")
      (node (ref "PAD417") (pin "1") (pinfunction "P_1") (pintype "passive"))
    )
    (net (code "528") (name "unconnected-(PAD418-P-Pad1)") (class "Default")
      (node (ref "PAD418") (pin "1") (pinfunction "P_1") (pintype "passive"))
    )
    (net (code "529") (name "unconnected-(PAD419-P-Pad1)") (class "Default")
      (node (ref "PAD419") (pin "1") (pinfunction "P_1") (pintype "passive"))
    )
    (net (code "530") (name "unconnected-(PAD420-P-Pad1)") (class "Default")
      (node (ref "PAD420") (pin "1") (pinfunction "P_1") (pintype "passive"))
    )
    (net (code "531") (name "unconnected-(PAD421-P-Pad1)") (class "Default")
      (node (ref "PAD421") (pin "1") (pinfunction "P_1") (pintype "passive"))
    )
    (net (code "532") (name "unconnected-(PAD422-P-Pad1)") (class "Default")
      (node (ref "PAD422") (pin "1") (pinfunction "P_1") (pintype "passive"))
    )
    (net (code "533") (name "unconnected-(PAD423-P-Pad1)") (class "Default")
      (node (ref "PAD423") (pin "1") (pinfunction "P_1") (pintype "passive"))
    )
    (net (code "534") (name "unconnected-(PAD424-P-Pad1)") (class "Default")
      (node (ref "PAD424") (pin "1") (pinfunction "P_1") (pintype "passive"))
    )
    (net (code "535") (name "unconnected-(PAD425-P-Pad1)") (class "Default")
      (node (ref "PAD425") (pin "1") (pinfunction "P_1") (pintype "passive"))
    )
    (net (code "536") (name "unconnected-(PAD426-P-Pad1)") (class "Default")
      (node (ref "PAD426") (pin "1") (pinfunction "P_1") (pintype "passive"))
    )
    (net (code "537") (name "unconnected-(PAD427-P-Pad1)") (class "Default")
      (node (ref "PAD427") (pin "1") (pinfunction "P_1") (pintype "passive"))
    )
    (net (code "538") (name "unconnected-(PAD428-P-Pad1)") (class "Default")
      (node (ref "PAD428") (pin "1") (pinfunction "P_1") (pintype "passive"))
    )
    (net (code "539") (name "unconnected-(PAD429-P-Pad1)") (class "Default")
      (node (ref "PAD429") (pin "1") (pinfunction "P_1") (pintype "passive"))
    )
    (net (code "540") (name "unconnected-(PAD430-P-Pad1)") (class "Default")
      (node (ref "PAD430") (pin "1") (pinfunction "P_1") (pintype "passive"))
    )
    (net (code "541") (name "unconnected-(PAD431-P-Pad1)") (class "Default")
      (node (ref "PAD431") (pin "1") (pinfunction "P_1") (pintype "passive"))
    )
    (net (code "542") (name "unconnected-(PAD432-P-Pad1)") (class "Default")
      (node (ref "PAD432") (pin "1") (pinfunction "P_1") (pintype "passive"))
    )
    (net (code "543") (name "unconnected-(PAD433-P-Pad1)") (class "Default")
      (node (ref "PAD433") (pin "1") (pinfunction "P_1") (pintype "passive"))
    )
    (net (code "544") (name "unconnected-(PAD434-P-Pad1)") (class "Default")
      (node (ref "PAD434") (pin "1") (pinfunction "P_1") (pintype "passive"))
    )
    (net (code "545") (name "unconnected-(PAD435-P-Pad1)") (class "Default")
      (node (ref "PAD435") (pin "1") (pinfunction "P_1") (pintype "passive"))
    )
    (net (code "546") (name "unconnected-(PAD436-P-Pad1)") (class "Default")
      (node (ref "PAD436") (pin "1") (pinfunction "P_1") (pintype "passive"))
    )
    (net (code "547") (name "unconnected-(PAD437-P-Pad1)") (class "Default")
      (node (ref "PAD437") (pin "1") (pinfunction "P_1") (pintype "passive"))
    )
    (net (code "548") (name "unconnected-(PAD438-P-Pad1)") (class "Default")
      (node (ref "PAD438") (pin "1") (pinfunction "P_1") (pintype "passive"))
    )
    (net (code "549") (name "unconnected-(PAD439-P-Pad1)") (class "Default")
      (node (ref "PAD439") (pin "1") (pinfunction "P_1") (pintype "passive"))
    )
    (net (code "550") (name "unconnected-(PAD440-P-Pad1)") (class "Default")
      (node (ref "PAD440") (pin "1") (pinfunction "P_1") (pintype "passive"))
    )
    (net (code "551") (name "unconnected-(PAD441-P-Pad1)") (class "Default")
      (node (ref "PAD441") (pin "1") (pinfunction "P_1") (pintype "passive"))
    )
    (net (code "552") (name "unconnected-(PAD442-P-Pad1)") (class "Default")
      (node (ref "PAD442") (pin "1") (pinfunction "P_1") (pintype "passive"))
    )
    (net (code "553") (name "unconnected-(PAD443-P-Pad1)") (class "Default")
      (node (ref "PAD443") (pin "1") (pinfunction "P_1") (pintype "passive"))
    )
    (net (code "554") (name "unconnected-(PAD444-P-Pad1)") (class "Default")
      (node (ref "PAD444") (pin "1") (pinfunction "P_1") (pintype "passive"))
    )
    (net (code "555") (name "unconnected-(PAD445-P-Pad1)") (class "Default")
      (node (ref "PAD445") (pin "1") (pinfunction "P_1") (pintype "passive"))
    )
    (net (code "556") (name "unconnected-(PAD446-P-Pad1)") (class "Default")
      (node (ref "PAD446") (pin "1") (pinfunction "P_1") (pintype "passive"))
    )
    (net (code "557") (name "unconnected-(PAD447-P-Pad1)") (class "Default")
      (node (ref "PAD447") (pin "1") (pinfunction "P_1") (pintype "passive"))
    )
    (net (code "558") (name "unconnected-(PAD448-P-Pad1)") (class "Default")
      (node (ref "PAD448") (pin "1") (pinfunction "P_1") (pintype "passive"))
    )
    (net (code "559") (name "unconnected-(PAD449-P-Pad1)") (class "Default")
      (node (ref "PAD449") (pin "1") (pinfunction "P_1") (pintype "passive"))
    )
    (net (code "560") (name "unconnected-(PAD450-P-Pad1)") (class "Default")
      (node (ref "PAD450") (pin "1") (pinfunction "P_1") (pintype "passive"))
    )
    (net (code "561") (name "unconnected-(PAD451-P-Pad1)") (class "Default")
      (node (ref "PAD451") (pin "1") (pinfunction "P_1") (pintype "passive"))
    )
    (net (code "562") (name "unconnected-(PAD452-P-Pad1)") (class "Default")
      (node (ref "PAD452") (pin "1") (pinfunction "P_1") (pintype "passive"))
    )
    (net (code "563") (name "unconnected-(PAD453-P-Pad1)") (class "Default")
      (node (ref "PAD453") (pin "1") (pinfunction "P_1") (pintype "passive"))
    )
    (net (code "564") (name "unconnected-(PAD454-P-Pad1)") (class "Default")
      (node (ref "PAD454") (pin "1") (pinfunction "P_1") (pintype "passive"))
    )
    (net (code "565") (name "unconnected-(PAD455-P-Pad1)") (class "Default")
      (node (ref "PAD455") (pin "1") (pinfunction "P_1") (pintype "passive"))
    )
    (net (code "566") (name "unconnected-(PAD456-P-Pad1)") (class "Default")
      (node (ref "PAD456") (pin "1") (pinfunction "P_1") (pintype "passive"))
    )
    (net (code "567") (name "unconnected-(PAD457-P-Pad1)") (class "Default")
      (node (ref "PAD457") (pin "1") (pinfunction "P_1") (pintype "passive"))
    )
    (net (code "568") (name "unconnected-(PAD458-P-Pad1)") (class "Default")
      (node (ref "PAD458") (pin "1") (pinfunction "P_1") (pintype "passive"))
    )
    (net (code "569") (name "unconnected-(PAD459-P-Pad1)") (class "Default")
      (node (ref "PAD459") (pin "1") (pinfunction "P_1") (pintype "passive"))
    )
    (net (code "570") (name "unconnected-(PAD460-P-Pad1)") (class "Default")
      (node (ref "PAD460") (pin "1") (pinfunction "P_1") (pintype "passive"))
    )
    (net (code "571") (name "unconnected-(PAD461-P-Pad1)") (class "Default")
      (node (ref "PAD461") (pin "1") (pinfunction "P_1") (pintype "passive"))
    )
    (net (code "572") (name "unconnected-(PAD462-P-Pad1)") (class "Default")
      (node (ref "PAD462") (pin "1") (pinfunction "P_1") (pintype "passive"))
    )
    (net (code "573") (name "unconnected-(PAD463-P-Pad1)") (class "Default")
      (node (ref "PAD463") (pin "1") (pinfunction "P_1") (pintype "passive"))
    )
    (net (code "574") (name "unconnected-(PAD464-P-Pad1)") (class "Default")
      (node (ref "PAD464") (pin "1") (pinfunction "P_1") (pintype "passive"))
    )
    (net (code "575") (name "unconnected-(PAD465-P-Pad1)") (class "Default")
      (node (ref "PAD465") (pin "1") (pinfunction "P_1") (pintype "passive"))
    )
    (net (code "576") (name "unconnected-(PAD466-P-Pad1)") (class "Default")
      (node (ref "PAD466") (pin "1") (pinfunction "P_1") (pintype "passive"))
    )
    (net (code "577") (name "unconnected-(PAD467-P-Pad1)") (class "Default")
      (node (ref "PAD467") (pin "1") (pinfunction "P_1") (pintype "passive"))
    )
    (net (code "578") (name "unconnected-(PAD468-P-Pad1)") (class "Default")
      (node (ref "PAD468") (pin "1") (pinfunction "P_1") (pintype "passive"))
    )
    (net (code "579") (name "unconnected-(PAD469-P-Pad1)") (class "Default")
      (node (ref "PAD469") (pin "1") (pinfunction "P_1") (pintype "passive"))
    )
    (net (code "580") (name "unconnected-(PAD470-P-Pad1)") (class "Default")
      (node (ref "PAD470") (pin "1") (pinfunction "P_1") (pintype "passive"))
    )
    (net (code "581") (name "unconnected-(PAD471-P-Pad1)") (class "Default")
      (node (ref "PAD471") (pin "1") (pinfunction "P_1") (pintype "passive"))
    )
    (net (code "582") (name "unconnected-(PAD472-P-Pad1)") (class "Default")
      (node (ref "PAD472") (pin "1") (pinfunction "P_1") (pintype "passive"))
    )
    (net (code "583") (name "unconnected-(PAD473-P-Pad1)") (class "Default")
      (node (ref "PAD473") (pin "1") (pinfunction "P_1") (pintype "passive"))
    )
    (net (code "584") (name "unconnected-(PAD474-P-Pad1)") (class "Default")
      (node (ref "PAD474") (pin "1") (pinfunction "P_1") (pintype "passive"))
    )
    (net (code "585") (name "unconnected-(PAD475-P-Pad1)") (class "Default")
      (node (ref "PAD475") (pin "1") (pinfunction "P_1") (pintype "passive"))
    )
    (net (code "586") (name "unconnected-(PAD476-P-Pad1)") (class "Default")
      (node (ref "PAD476") (pin "1") (pinfunction "P_1") (pintype "passive"))
    )
    (net (code "587") (name "unconnected-(PAD477-P-Pad1)") (class "Default")
      (node (ref "PAD477") (pin "1") (pinfunction "P_1") (pintype "passive"))
    )
    (net (code "588") (name "unconnected-(PAD478-P-Pad1)") (class "Default")
      (node (ref "PAD478") (pin "1") (pinfunction "P_1") (pintype "passive"))
    )
    (net (code "589") (name "unconnected-(PAD479-P-Pad1)") (class "Default")
      (node (ref "PAD479") (pin "1") (pinfunction "P_1") (pintype "passive"))
    )
    (net (code "590") (name "unconnected-(PAD480-P-Pad1)") (class "Default")
      (node (ref "PAD480") (pin "1") (pinfunction "P_1") (pintype "passive"))
    )
    (net (code "591") (name "unconnected-(PAD481-P-Pad1)") (class "Default")
      (node (ref "PAD481") (pin "1") (pinfunction "P_1") (pintype "passive"))
    )
    (net (code "592") (name "unconnected-(PAD482-P-Pad1)") (class "Default")
      (node (ref "PAD482") (pin "1") (pinfunction "P_1") (pintype "passive"))
    )
    (net (code "593") (name "unconnected-(PAD483-P-Pad1)") (class "Default")
      (node (ref "PAD483") (pin "1") (pinfunction "P_1") (pintype "passive"))
    )
    (net (code "594") (name "unconnected-(PAD484-P-Pad1)") (class "Default")
      (node (ref "PAD484") (pin "1") (pinfunction "P_1") (pintype "passive"))
    )
    (net (code "595") (name "unconnected-(PAD485-P-Pad1)") (class "Default")
      (node (ref "PAD485") (pin "1") (pinfunction "P_1") (pintype "passive"))
    )
    (net (code "596") (name "unconnected-(PAD486-P-Pad1)") (class "Default")
      (node (ref "PAD486") (pin "1") (pinfunction "P_1") (pintype "passive"))
    )
    (net (code "597") (name "unconnected-(PAD487-P-Pad1)") (class "Default")
      (node (ref "PAD487") (pin "1") (pinfunction "P_1") (pintype "passive"))
    )
    (net (code "598") (name "unconnected-(PAD488-P-Pad1)") (class "Default")
      (node (ref "PAD488") (pin "1") (pinfunction "P_1") (pintype "passive"))
    )
    (net (code "599") (name "unconnected-(PAD489-P-Pad1)") (class "Default")
      (node (ref "PAD489") (pin "1") (pinfunction "P_1") (pintype "passive"))
    )
    (net (code "600") (name "unconnected-(PAD490-P-Pad1)") (class "Default")
      (node (ref "PAD490") (pin "1") (pinfunction "P_1") (pintype "passive"))
    )
    (net (code "601") (name "unconnected-(PAD491-P-Pad1)") (class "Default")
      (node (ref "PAD491") (pin "1") (pinfunction "P_1") (pintype "passive"))
    )
    (net (code "602") (name "unconnected-(PAD492-P-Pad1)") (class "Default")
      (node (ref "PAD492") (pin "1") (pinfunction "P_1") (pintype "passive"))
    )
    (net (code "603") (name "unconnected-(PAD493-P-Pad1)") (class "Default")
      (node (ref "PAD493") (pin "1") (pinfunction "P_1") (pintype "passive"))
    )
    (net (code "604") (name "unconnected-(PAD494-P-Pad1)") (class "Default")
      (node (ref "PAD494") (pin "1") (pinfunction "P_1") (pintype "passive"))
    )
    (net (code "605") (name "unconnected-(PAD495-P-Pad1)") (class "Default")
      (node (ref "PAD495") (pin "1") (pinfunction "P_1") (pintype "passive"))
    )
    (net (code "606") (name "unconnected-(PAD496-P-Pad1)") (class "Default")
      (node (ref "PAD496") (pin "1") (pinfunction "P_1") (pintype "passive"))
    )
    (net (code "607") (name "unconnected-(PAD497-P-Pad1)") (class "Default")
      (node (ref "PAD497") (pin "1") (pinfunction "P_1") (pintype "passive"))
    )
    (net (code "608") (name "unconnected-(PAD498-P-Pad1)") (class "Default")
      (node (ref "PAD498") (pin "1") (pinfunction "P_1") (pintype "passive"))
    )
    (net (code "609") (name "unconnected-(PAD499-P-Pad1)") (class "Default")
      (node (ref "PAD499") (pin "1") (pinfunction "P_1") (pintype "passive"))
    )
    (net (code "610") (name "unconnected-(PAD500-P-Pad1)") (class "Default")
      (node (ref "PAD500") (pin "1") (pinfunction "P_1") (pintype "passive"))
    )
    (net (code "611") (name "unconnected-(PAD501-P-Pad1)") (class "Default")
      (node (ref "PAD501") (pin "1") (pinfunction "P_1") (pintype "passive"))
    )
    (net (code "612") (name "unconnected-(PAD502-P-Pad1)") (class "Default")
      (node (ref "PAD502") (pin "1") (pinfunction "P_1") (pintype "passive"))
    )
    (net (code "613") (name "unconnected-(PAD503-P-Pad1)") (class "Default")
      (node (ref "PAD503") (pin "1") (pinfunction "P_1") (pintype "passive"))
    )
    (net (code "614") (name "unconnected-(PAD504-P-Pad1)") (class "Default")
      (node (ref "PAD504") (pin "1") (pinfunction "P_1") (pintype "passive"))
    )
    (net (code "615") (name "unconnected-(PAD505-P-Pad1)") (class "Default")
      (node (ref "PAD505") (pin "1") (pinfunction "P_1") (pintype "passive"))
    )
    (net (code "616") (name "unconnected-(PAD506-P-Pad1)") (class "Default")
      (node (ref "PAD506") (pin "1") (pinfunction "P_1") (pintype "passive"))
    )
    (net (code "617") (name "unconnected-(PAD507-P-Pad1)") (class "Default")
      (node (ref "PAD507") (pin "1") (pinfunction "P_1") (pintype "passive"))
    )
    (net (code "618") (name "unconnected-(PAD508-P-Pad1)") (class "Default")
      (node (ref "PAD508") (pin "1") (pinfunction "P_1") (pintype "passive"))
    )
    (net (code "619") (name "unconnected-(PAD509-P-Pad1)") (class "Default")
      (node (ref "PAD509") (pin "1") (pinfunction "P_1") (pintype "passive"))
    )
    (net (code "620") (name "unconnected-(PAD510-P-Pad1)") (class "Default")
      (node (ref "PAD510") (pin "1") (pinfunction "P_1") (pintype "passive"))
    )
    (net (code "621") (name "unconnected-(PAD511-P-Pad1)") (class "Default")
      (node (ref "PAD511") (pin "1") (pinfunction "P_1") (pintype "passive"))
    )
    (net (code "622") (name "unconnected-(PAD512-P-Pad1)") (class "Default")
      (node (ref "PAD512") (pin "1") (pinfunction "P_1") (pintype "passive"))
    )
    (net (code "623") (name "unconnected-(PAD513-P-Pad1)") (class "Default")
      (node (ref "PAD513") (pin "1") (pinfunction "P_1") (pintype "passive"))
    )
    (net (code "624") (name "unconnected-(PAD514-P-Pad1)") (class "Default")
      (node (ref "PAD514") (pin "1") (pinfunction "P_1") (pintype "passive"))
    )
    (net (code "625") (name "unconnected-(PAD515-P-Pad1)") (class "Default")
      (node (ref "PAD515") (pin "1") (pinfunction "P_1") (pintype "passive"))
    )
    (net (code "626") (name "unconnected-(PAD516-P-Pad1)") (class "Default")
      (node (ref "PAD516") (pin "1") (pinfunction "P_1") (pintype "passive"))
    )
    (net (code "627") (name "unconnected-(PAD517-P-Pad1)") (class "Default")
      (node (ref "PAD517") (pin "1") (pinfunction "P_1") (pintype "passive"))
    )
    (net (code "628") (name "unconnected-(PAD518-P-Pad1)") (class "Default")
      (node (ref "PAD518") (pin "1") (pinfunction "P_1") (pintype "passive"))
    )
    (net (code "629") (name "unconnected-(PAD519-P-Pad1)") (class "Default")
      (node (ref "PAD519") (pin "1") (pinfunction "P_1") (pintype "passive"))
    )
    (net (code "630") (name "unconnected-(PAD520-P-Pad1)") (class "Default")
      (node (ref "PAD520") (pin "1") (pinfunction "P_1") (pintype "passive"))
    )
    (net (code "631") (name "unconnected-(PAD521-P-Pad1)") (class "Default")
      (node (ref "PAD521") (pin "1") (pinfunction "P_1") (pintype "passive"))
    )
    (net (code "632") (name "unconnected-(PAD522-P-Pad1)") (class "Default")
      (node (ref "PAD522") (pin "1") (pinfunction "P_1") (pintype "passive"))
    )
    (net (code "633") (name "unconnected-(PAD523-P-Pad1)") (class "Default")
      (node (ref "PAD523") (pin "1") (pinfunction "P_1") (pintype "passive"))
    )
    (net (code "634") (name "unconnected-(PAD524-P-Pad1)") (class "Default")
      (node (ref "PAD524") (pin "1") (pinfunction "P_1") (pintype "passive"))
    )
    (net (code "635") (name "unconnected-(PAD525-P-Pad1)") (class "Default")
      (node (ref "PAD525") (pin "1") (pinfunction "P_1") (pintype "passive"))
    )
    (net (code "636") (name "unconnected-(PAD526-P-Pad1)") (class "Default")
      (node (ref "PAD526") (pin "1") (pinfunction "P_1") (pintype "passive"))
    )
    (net (code "637") (name "unconnected-(PAD527-P-Pad1)") (class "Default")
      (node (ref "PAD527") (pin "1") (pinfunction "P_1") (pintype "passive"))
    )
    (net (code "638") (name "unconnected-(PAD528-P-Pad1)") (class "Default")
      (node (ref "PAD528") (pin "1") (pinfunction "P_1") (pintype "passive"))
    )
    (net (code "639") (name "unconnected-(PAD529-P-Pad1)") (class "Default")
      (node (ref "PAD529") (pin "1") (pinfunction "P_1") (pintype "passive"))
    )
    (net (code "640") (name "unconnected-(PAD530-P-Pad1)") (class "Default")
      (node (ref "PAD530") (pin "1") (pinfunction "P_1") (pintype "passive"))
    )
    (net (code "641") (name "unconnected-(PAD531-P-Pad1)") (class "Default")
      (node (ref "PAD531") (pin "1") (pinfunction "P_1") (pintype "passive"))
    )
    (net (code "642") (name "unconnected-(PAD532-P-Pad1)") (class "Default")
      (node (ref "PAD532") (pin "1") (pinfunction "P_1") (pintype "passive"))
    )
    (net (code "643") (name "unconnected-(PAD533-P-Pad1)") (class "Default")
      (node (ref "PAD533") (pin "1") (pinfunction "P_1") (pintype "passive"))
    )
    (net (code "644") (name "unconnected-(PAD534-P-Pad1)") (class "Default")
      (node (ref "PAD534") (pin "1") (pinfunction "P_1") (pintype "passive"))
    )
    (net (code "645") (name "unconnected-(PAD535-P-Pad1)") (class "Default")
      (node (ref "PAD535") (pin "1") (pinfunction "P_1") (pintype "passive"))
    )
    (net (code "646") (name "unconnected-(PAD536-P-Pad1)") (class "Default")
      (node (ref "PAD536") (pin "1") (pinfunction "P_1") (pintype "passive"))
    )
    (net (code "647") (name "unconnected-(PAD537-P-Pad1)") (class "Default")
      (node (ref "PAD537") (pin "1") (pinfunction "P_1") (pintype "passive"))
    )
    (net (code "648") (name "unconnected-(PAD538-P-Pad1)") (class "Default")
      (node (ref "PAD538") (pin "1") (pinfunction "P_1") (pintype "passive"))
    )
    (net (code "649") (name "unconnected-(PAD539-P-Pad1)") (class "Default")
      (node (ref "PAD539") (pin "1") (pinfunction "P_1") (pintype "passive"))
    )
    (net (code "650") (name "unconnected-(PAD540-P-Pad1)") (class "Default")
      (node (ref "PAD540") (pin "1") (pinfunction "P_1") (pintype "passive"))
    )
    (net (code "651") (name "unconnected-(PAD541-P-Pad1)") (class "Default")
      (node (ref "PAD541") (pin "1") (pinfunction "P_1") (pintype "passive"))
    )
    (net (code "652") (name "unconnected-(PAD542-P-Pad1)") (class "Default")
      (node (ref "PAD542") (pin "1") (pinfunction "P_1") (pintype "passive"))
    )
    (net (code "653") (name "unconnected-(PAD543-P-Pad1)") (class "Default")
      (node (ref "PAD543") (pin "1") (pinfunction "P_1") (pintype "passive"))
    )
    (net (code "654") (name "unconnected-(PAD544-P-Pad1)") (class "Default")
      (node (ref "PAD544") (pin "1") (pinfunction "P_1") (pintype "passive"))
    )
    (net (code "655") (name "unconnected-(PAD545-P-Pad1)") (class "Default")
      (node (ref "PAD545") (pin "1") (pinfunction "P_1") (pintype "passive"))
    )
    (net (code "656") (name "unconnected-(PAD546-P-Pad1)") (class "Default")
      (node (ref "PAD546") (pin "1") (pinfunction "P_1") (pintype "passive"))
    )
    (net (code "657") (name "unconnected-(PAD547-P-Pad1)") (class "Default")
      (node (ref "PAD547") (pin "1") (pinfunction "P_1") (pintype "passive"))
    )
    (net (code "658") (name "unconnected-(PAD548-P-Pad1)") (class "Default")
      (node (ref "PAD548") (pin "1") (pinfunction "P_1") (pintype "passive"))
    )
    (net (code "659") (name "unconnected-(PAD549-P-Pad1)") (class "Default")
      (node (ref "PAD549") (pin "1") (pinfunction "P_1") (pintype "passive"))
    )
    (net (code "660") (name "unconnected-(PAD550-P-Pad1)") (class "Default")
      (node (ref "PAD550") (pin "1") (pinfunction "P_1") (pintype "passive"))
    )
    (net (code "661") (name "unconnected-(PAD551-P-Pad1)") (class "Default")
      (node (ref "PAD551") (pin "1") (pinfunction "P_1") (pintype "passive"))
    )
    (net (code "662") (name "unconnected-(PAD552-P-Pad1)") (class "Default")
      (node (ref "PAD552") (pin "1") (pinfunction "P_1") (pintype "passive"))
    )
    (net (code "663") (name "unconnected-(PAD553-P-Pad1)") (class "Default")
      (node (ref "PAD553") (pin "1") (pinfunction "P_1") (pintype "passive"))
    )
    (net (code "664") (name "unconnected-(PAD554-P-Pad1)") (class "Default")
      (node (ref "PAD554") (pin "1") (pinfunction "P_1") (pintype "passive"))
    )
    (net (code "665") (name "unconnected-(PAD555-P-Pad1)") (class "Default")
      (node (ref "PAD555") (pin "1") (pinfunction "P_1") (pintype "passive"))
    )
    (net (code "666") (name "unconnected-(PAD556-P-Pad1)") (class "Default")
      (node (ref "PAD556") (pin "1") (pinfunction "P_1") (pintype "passive"))
    )
    (net (code "667") (name "unconnected-(PAD557-P-Pad1)") (class "Default")
      (node (ref "PAD557") (pin "1") (pinfunction "P_1") (pintype "passive"))
    )
    (net (code "668") (name "unconnected-(PAD558-P-Pad1)") (class "Default")
      (node (ref "PAD558") (pin "1") (pinfunction "P_1") (pintype "passive"))
    )
    (net (code "669") (name "unconnected-(PAD559-P-Pad1)") (class "Default")
      (node (ref "PAD559") (pin "1") (pinfunction "P_1") (pintype "passive"))
    )
    (net (code "670") (name "unconnected-(PAD560-P-Pad1)") (class "Default")
      (node (ref "PAD560") (pin "1") (pinfunction "P_1") (pintype "passive"))
    )
    (net (code "671") (name "unconnected-(PAD561-P-Pad1)") (class "Default")
      (node (ref "PAD561") (pin "1") (pinfunction "P_1") (pintype "passive"))
    )
    (net (code "672") (name "unconnected-(PAD562-P-Pad1)") (class "Default")
      (node (ref "PAD562") (pin "1") (pinfunction "P_1") (pintype "passive"))
    )
    (net (code "673") (name "unconnected-(PAD563-P-Pad1)") (class "Default")
      (node (ref "PAD563") (pin "1") (pinfunction "P_1") (pintype "passive"))
    )
    (net (code "674") (name "unconnected-(PAD564-P-Pad1)") (class "Default")
      (node (ref "PAD564") (pin "1") (pinfunction "P_1") (pintype "passive"))
    )
    (net (code "675") (name "unconnected-(PAD565-P-Pad1)") (class "Default")
      (node (ref "PAD565") (pin "1") (pinfunction "P_1") (pintype "passive"))
    )
    (net (code "676") (name "unconnected-(PAD566-P-Pad1)") (class "Default")
      (node (ref "PAD566") (pin "1") (pinfunction "P_1") (pintype "passive"))
    )
    (net (code "677") (name "unconnected-(PAD567-P-Pad1)") (class "Default")
      (node (ref "PAD567") (pin "1") (pinfunction "P_1") (pintype "passive"))
    )
    (net (code "678") (name "unconnected-(PAD568-P-Pad1)") (class "Default")
      (node (ref "PAD568") (pin "1") (pinfunction "P_1") (pintype "passive"))
    )
    (net (code "679") (name "unconnected-(PAD569-P-Pad1)") (class "Default")
      (node (ref "PAD569") (pin "1") (pinfunction "P_1") (pintype "passive"))
    )
    (net (code "680") (name "unconnected-(PAD570-P-Pad1)") (class "Default")
      (node (ref "PAD570") (pin "1") (pinfunction "P_1") (pintype "passive"))
    )
    (net (code "681") (name "unconnected-(PAD571-P-Pad1)") (class "Default")
      (node (ref "PAD571") (pin "1") (pinfunction "P_1") (pintype "passive"))
    )
    (net (code "682") (name "unconnected-(PAD574-P-Pad1)") (class "Default")
      (node (ref "PAD574") (pin "1") (pinfunction "P_1") (pintype "passive"))
    )
    (net (code "683") (name "unconnected-(PAD575-P-Pad1)") (class "Default")
      (node (ref "PAD575") (pin "1") (pinfunction "P_1") (pintype "passive"))
    )
    (net (code "684") (name "unconnected-(PAD576-P-Pad1)") (class "Default")
      (node (ref "PAD576") (pin "1") (pinfunction "P_1") (pintype "passive"))
    )
    (net (code "685") (name "unconnected-(PAD577-P-Pad1)") (class "Default")
      (node (ref "PAD577") (pin "1") (pinfunction "P_1") (pintype "passive"))
    )
    (net (code "686") (name "unconnected-(PAD578-P-Pad1)") (class "Default")
      (node (ref "PAD578") (pin "1") (pinfunction "P_1") (pintype "passive"))
    )
    (net (code "687") (name "unconnected-(PAD579-P-Pad1)") (class "Default")
      (node (ref "PAD579") (pin "1") (pinfunction "P_1") (pintype "passive"))
    )
    (net (code "688") (name "unconnected-(PAD582-P-Pad1)") (class "Default")
      (node (ref "PAD582") (pin "1") (pinfunction "P_1") (pintype "passive"))
    )
    (net (code "689") (name "unconnected-(PAD583-P-Pad1)") (class "Default")
      (node (ref "PAD583") (pin "1") (pinfunction "P_1") (pintype "passive"))
    )
    (net (code "690") (name "unconnected-(PAD584-P-Pad1)") (class "Default")
      (node (ref "PAD584") (pin "1") (pinfunction "P_1") (pintype "passive"))
    )
    (net (code "691") (name "unconnected-(PAD585-P-Pad1)") (class "Default")
      (node (ref "PAD585") (pin "1") (pinfunction "P_1") (pintype "passive"))
    )
    (net (code "692") (name "unconnected-(PAD586-P-Pad1)") (class "Default")
      (node (ref "PAD586") (pin "1") (pinfunction "P_1") (pintype "passive"))
    )
    (net (code "693") (name "unconnected-(PAD587-P-Pad1)") (class "Default")
      (node (ref "PAD587") (pin "1") (pinfunction "P_1") (pintype "passive"))
    )
    (net (code "694") (name "unconnected-(PAD590-P-Pad1)") (class "Default")
      (node (ref "PAD590") (pin "1") (pinfunction "P_1") (pintype "passive"))
    )
    (net (code "695") (name "unconnected-(PAD591-P-Pad1)") (class "Default")
      (node (ref "PAD591") (pin "1") (pinfunction "P_1") (pintype "passive"))
    )
    (net (code "696") (name "unconnected-(PAD592-P-Pad1)") (class "Default")
      (node (ref "PAD592") (pin "1") (pinfunction "P_1") (pintype "passive"))
    )
    (net (code "697") (name "unconnected-(PAD593-P-Pad1)") (class "Default")
      (node (ref "PAD593") (pin "1") (pinfunction "P_1") (pintype "passive"))
    )
    (net (code "698") (name "unconnected-(PAD594-P-Pad1)") (class "Default")
      (node (ref "PAD594") (pin "1") (pinfunction "P_1") (pintype "passive"))
    )
    (net (code "699") (name "unconnected-(PAD595-P-Pad1)") (class "Default")
      (node (ref "PAD595") (pin "1") (pinfunction "P_1") (pintype "passive"))
    )
    (net (code "700") (name "unconnected-(PAD597-P-Pad1)") (class "Default")
      (node (ref "PAD597") (pin "1") (pinfunction "P_1") (pintype "passive"))
    )
    (net (code "701") (name "unconnected-(PAD598-P-Pad1)") (class "Default")
      (node (ref "PAD598") (pin "1") (pinfunction "P_1") (pintype "passive"))
    )
    (net (code "702") (name "unconnected-(PAD599-P-Pad1)") (class "Default")
      (node (ref "PAD599") (pin "1") (pinfunction "P_1") (pintype "passive"))
    )
    (net (code "703") (name "unconnected-(PAD600-P-Pad1)") (class "Default")
      (node (ref "PAD600") (pin "1") (pinfunction "P_1") (pintype "passive"))
    )
    (net (code "704") (name "unconnected-(PAD601-P-Pad1)") (class "Default")
      (node (ref "PAD601") (pin "1") (pinfunction "P_1") (pintype "passive"))
    )
    (net (code "705") (name "unconnected-(PAD602-P-Pad1)") (class "Default")
      (node (ref "PAD602") (pin "1") (pinfunction "P_1") (pintype "passive"))
    )
    (net (code "706") (name "unconnected-(PAD603-P-Pad1)") (class "Default")
      (node (ref "PAD603") (pin "1") (pinfunction "P_1") (pintype "passive"))
    )
    (net (code "707") (name "unconnected-(PAD605-P-Pad1)") (class "Default")
      (node (ref "PAD605") (pin "1") (pinfunction "P_1") (pintype "passive"))
    )
    (net (code "708") (name "unconnected-(PAD606-P-Pad1)") (class "Default")
      (node (ref "PAD606") (pin "1") (pinfunction "P_1") (pintype "passive"))
    )
    (net (code "709") (name "unconnected-(PAD607-P-Pad1)") (class "Default")
      (node (ref "PAD607") (pin "1") (pinfunction "P_1") (pintype "passive"))
    )
    (net (code "710") (name "unconnected-(PAD608-P-Pad1)") (class "Default")
      (node (ref "PAD608") (pin "1") (pinfunction "P_1") (pintype "passive"))
    )
    (net (code "711") (name "unconnected-(PAD609-P-Pad1)") (class "Default")
      (node (ref "PAD609") (pin "1") (pinfunction "P_1") (pintype "passive"))
    )
    (net (code "712") (name "unconnected-(PAD610-P-Pad1)") (class "Default")
      (node (ref "PAD610") (pin "1") (pinfunction "P_1") (pintype "passive"))
    )
    (net (code "713") (name "unconnected-(PAD611-P-Pad1)") (class "Default")
      (node (ref "PAD611") (pin "1") (pinfunction "P_1") (pintype "passive"))
    )
    (net (code "714") (name "unconnected-(PAD613-P-Pad1)") (class "Default")
      (node (ref "PAD613") (pin "1") (pinfunction "P_1") (pintype "passive"))
    )
    (net (code "715") (name "unconnected-(PAD614-P-Pad1)") (class "Default")
      (node (ref "PAD614") (pin "1") (pinfunction "P_1") (pintype "passive"))
    )
    (net (code "716") (name "unconnected-(PAD615-P-Pad1)") (class "Default")
      (node (ref "PAD615") (pin "1") (pinfunction "P_1") (pintype "passive"))
    )
    (net (code "717") (name "unconnected-(PAD616-P-Pad1)") (class "Default")
      (node (ref "PAD616") (pin "1") (pinfunction "P_1") (pintype "passive"))
    )
    (net (code "718") (name "unconnected-(PAD617-P-Pad1)") (class "Default")
      (node (ref "PAD617") (pin "1") (pinfunction "P_1") (pintype "passive"))
    )
    (net (code "719") (name "unconnected-(PAD618-P-Pad1)") (class "Default")
      (node (ref "PAD618") (pin "1") (pinfunction "P_1") (pintype "passive"))
    )
    (net (code "720") (name "unconnected-(PAD619-P-Pad1)") (class "Default")
      (node (ref "PAD619") (pin "1") (pinfunction "P_1") (pintype "passive"))
    )
    (net (code "721") (name "unconnected-(PAD620-P-Pad1)") (class "Default")
      (node (ref "PAD620") (pin "1") (pinfunction "P_1") (pintype "passive"))
    )
    (net (code "722") (name "unconnected-(PAD621-P-Pad1)") (class "Default")
      (node (ref "PAD621") (pin "1") (pinfunction "P_1") (pintype "passive"))
    )
    (net (code "723") (name "unconnected-(PAD622-P-Pad1)") (class "Default")
      (node (ref "PAD622") (pin "1") (pinfunction "P_1") (pintype "passive"))
    )
    (net (code "724") (name "unconnected-(PAD623-P-Pad1)") (class "Default")
      (node (ref "PAD623") (pin "1") (pinfunction "P_1") (pintype "passive"))
    )
    (net (code "725") (name "unconnected-(PAD624-P-Pad1)") (class "Default")
      (node (ref "PAD624") (pin "1") (pinfunction "P_1") (pintype "passive"))
    )
    (net (code "726") (name "unconnected-(PAD625-P-Pad1)") (class "Default")
      (node (ref "PAD625") (pin "1") (pinfunction "P_1") (pintype "passive"))
    )
    (net (code "727") (name "unconnected-(PAD626-P-Pad1)") (class "Default")
      (node (ref "PAD626") (pin "1") (pinfunction "P_1") (pintype "passive"))
    )
    (net (code "728") (name "unconnected-(PAD627-P-Pad1)") (class "Default")
      (node (ref "PAD627") (pin "1") (pinfunction "P_1") (pintype "passive"))
    )
    (net (code "729") (name "unconnected-(PAD628-P-Pad1)") (class "Default")
      (node (ref "PAD628") (pin "1") (pinfunction "P_1") (pintype "passive"))
    )
    (net (code "730") (name "unconnected-(PAD629-P-Pad1)") (class "Default")
      (node (ref "PAD629") (pin "1") (pinfunction "P_1") (pintype "passive"))
    )
    (net (code "731") (name "unconnected-(PAD630-P-Pad1)") (class "Default")
      (node (ref "PAD630") (pin "1") (pinfunction "P_1") (pintype "passive"))
    )
    (net (code "732") (name "unconnected-(PAD631-P-Pad1)") (class "Default")
      (node (ref "PAD631") (pin "1") (pinfunction "P_1") (pintype "passive"))
    )
    (net (code "733") (name "unconnected-(PAD632-P-Pad1)") (class "Default")
      (node (ref "PAD632") (pin "1") (pinfunction "P_1") (pintype "passive"))
    )
    (net (code "734") (name "unconnected-(PAD633-P-Pad1)") (class "Default")
      (node (ref "PAD633") (pin "1") (pinfunction "P_1") (pintype "passive"))
    )
    (net (code "735") (name "unconnected-(PAD634-P-Pad1)") (class "Default")
      (node (ref "PAD634") (pin "1") (pinfunction "P_1") (pintype "passive"))
    )
    (net (code "736") (name "unconnected-(PAD635-P-Pad1)") (class "Default")
      (node (ref "PAD635") (pin "1") (pinfunction "P_1") (pintype "passive"))
    )
    (net (code "737") (name "unconnected-(PAD636-P-Pad1)") (class "Default")
      (node (ref "PAD636") (pin "1") (pinfunction "P_1") (pintype "passive"))
    )
    (net (code "738") (name "unconnected-(PAD637-P-Pad1)") (class "Default")
      (node (ref "PAD637") (pin "1") (pinfunction "P_1") (pintype "passive"))
    )
    (net (code "739") (name "unconnected-(QG1-E{slash}D-Pad1)") (class "Default")
      (node (ref "QG1") (pin "1") (pinfunction "E/D_1") (pintype "input"))
    )
  )
)
